# Sheet1.net
KiCad netlist of a schematic drawn in Altium Designer
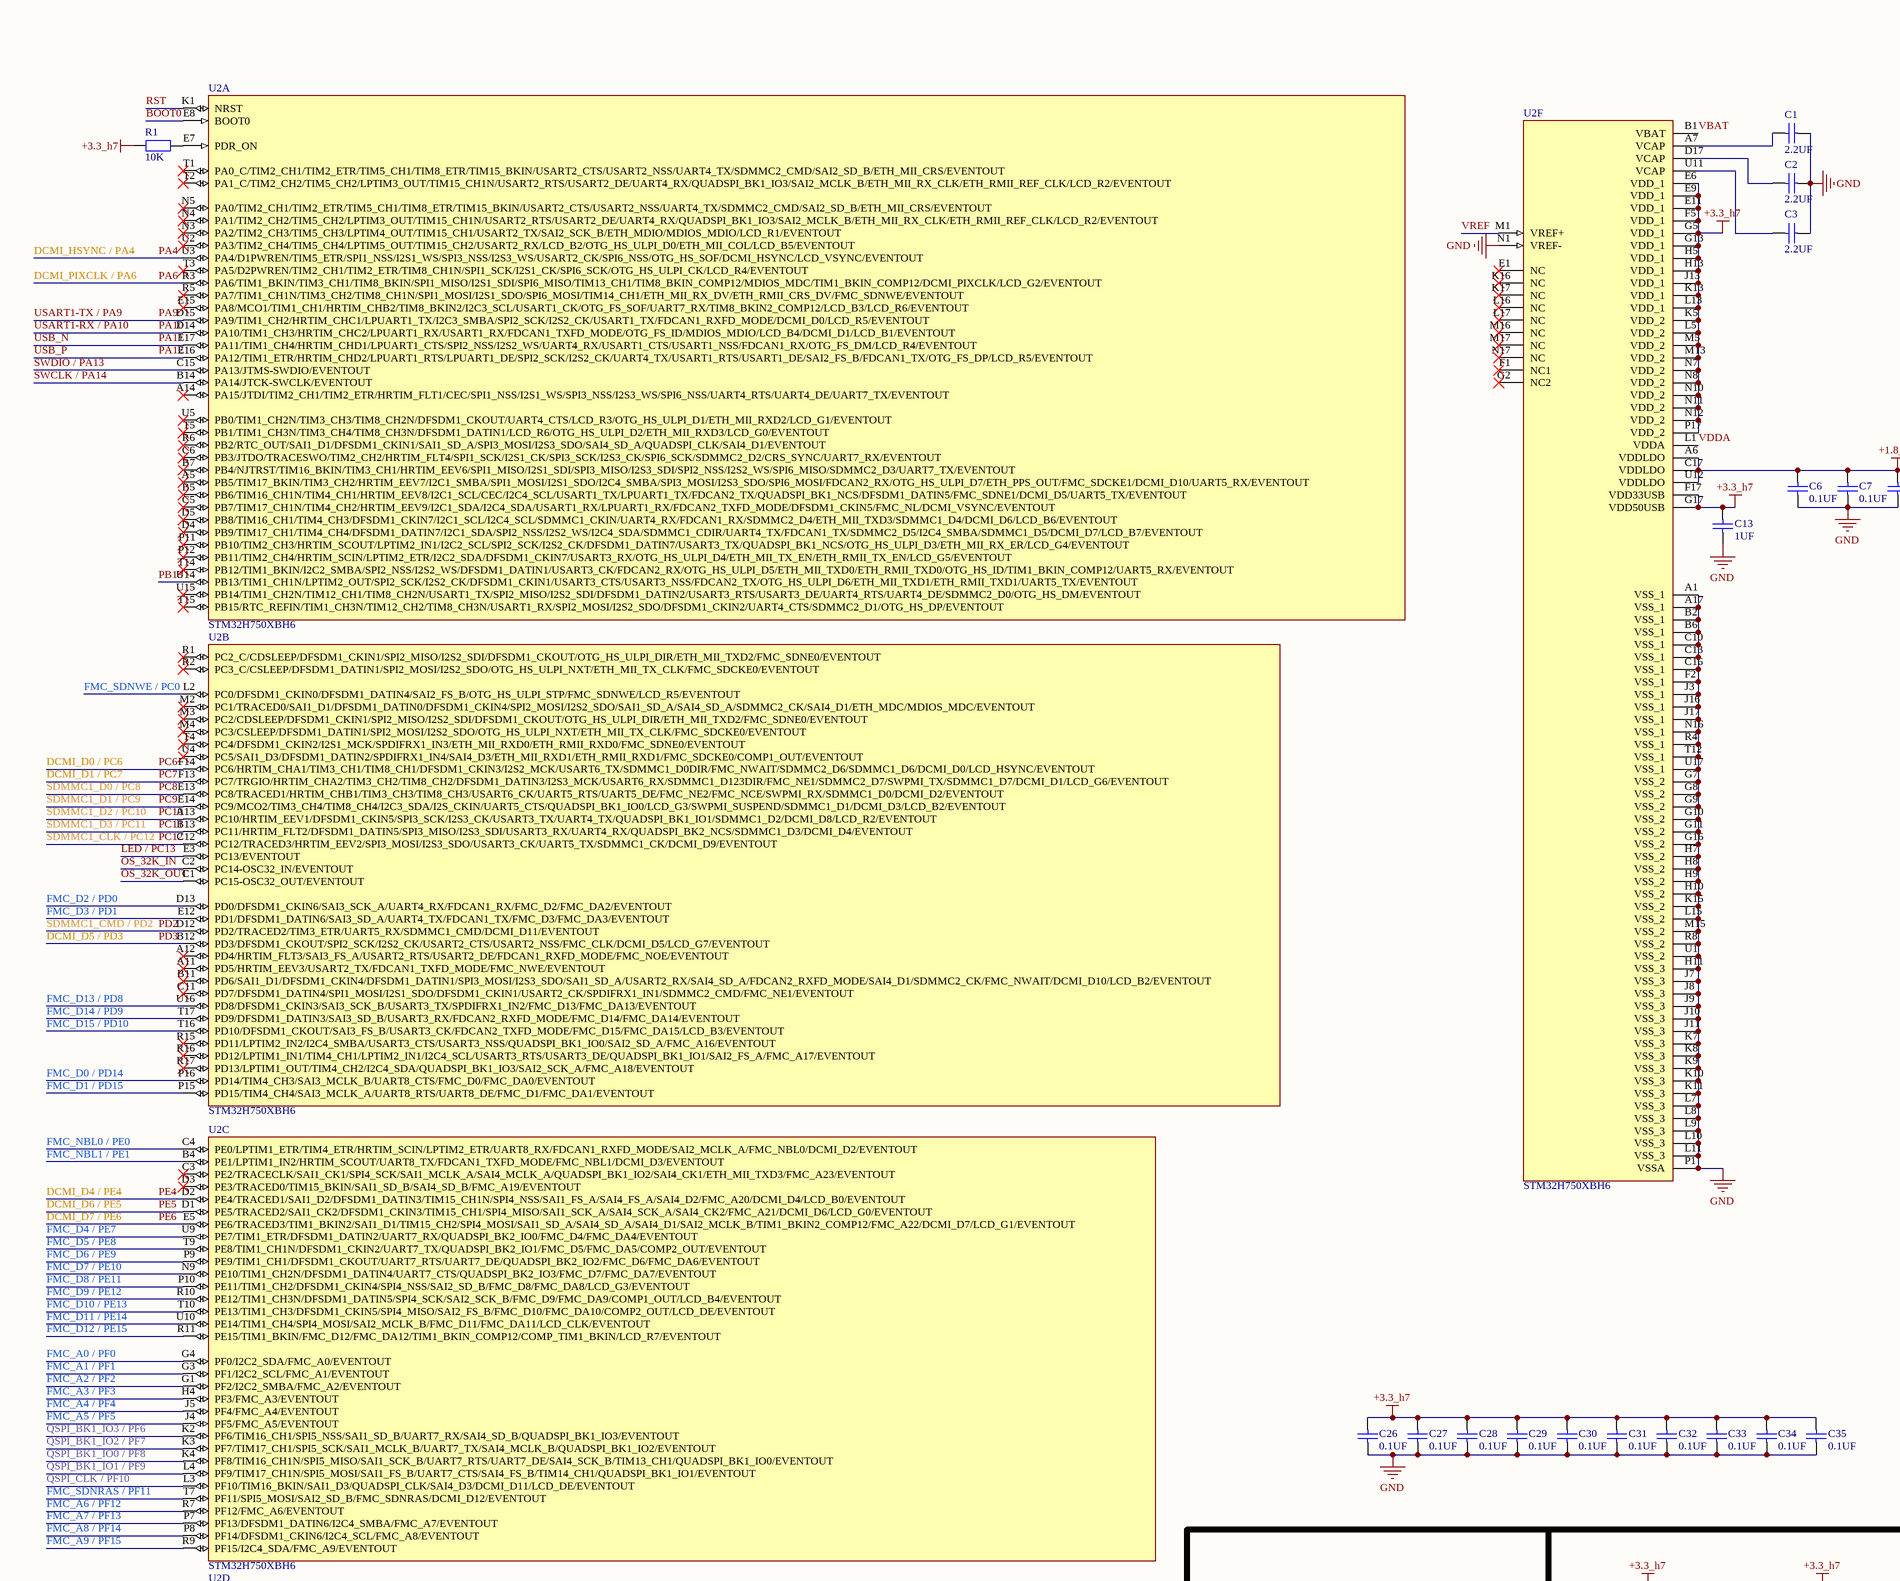
[diagram p0: Sheet1.SchDoc, top left]
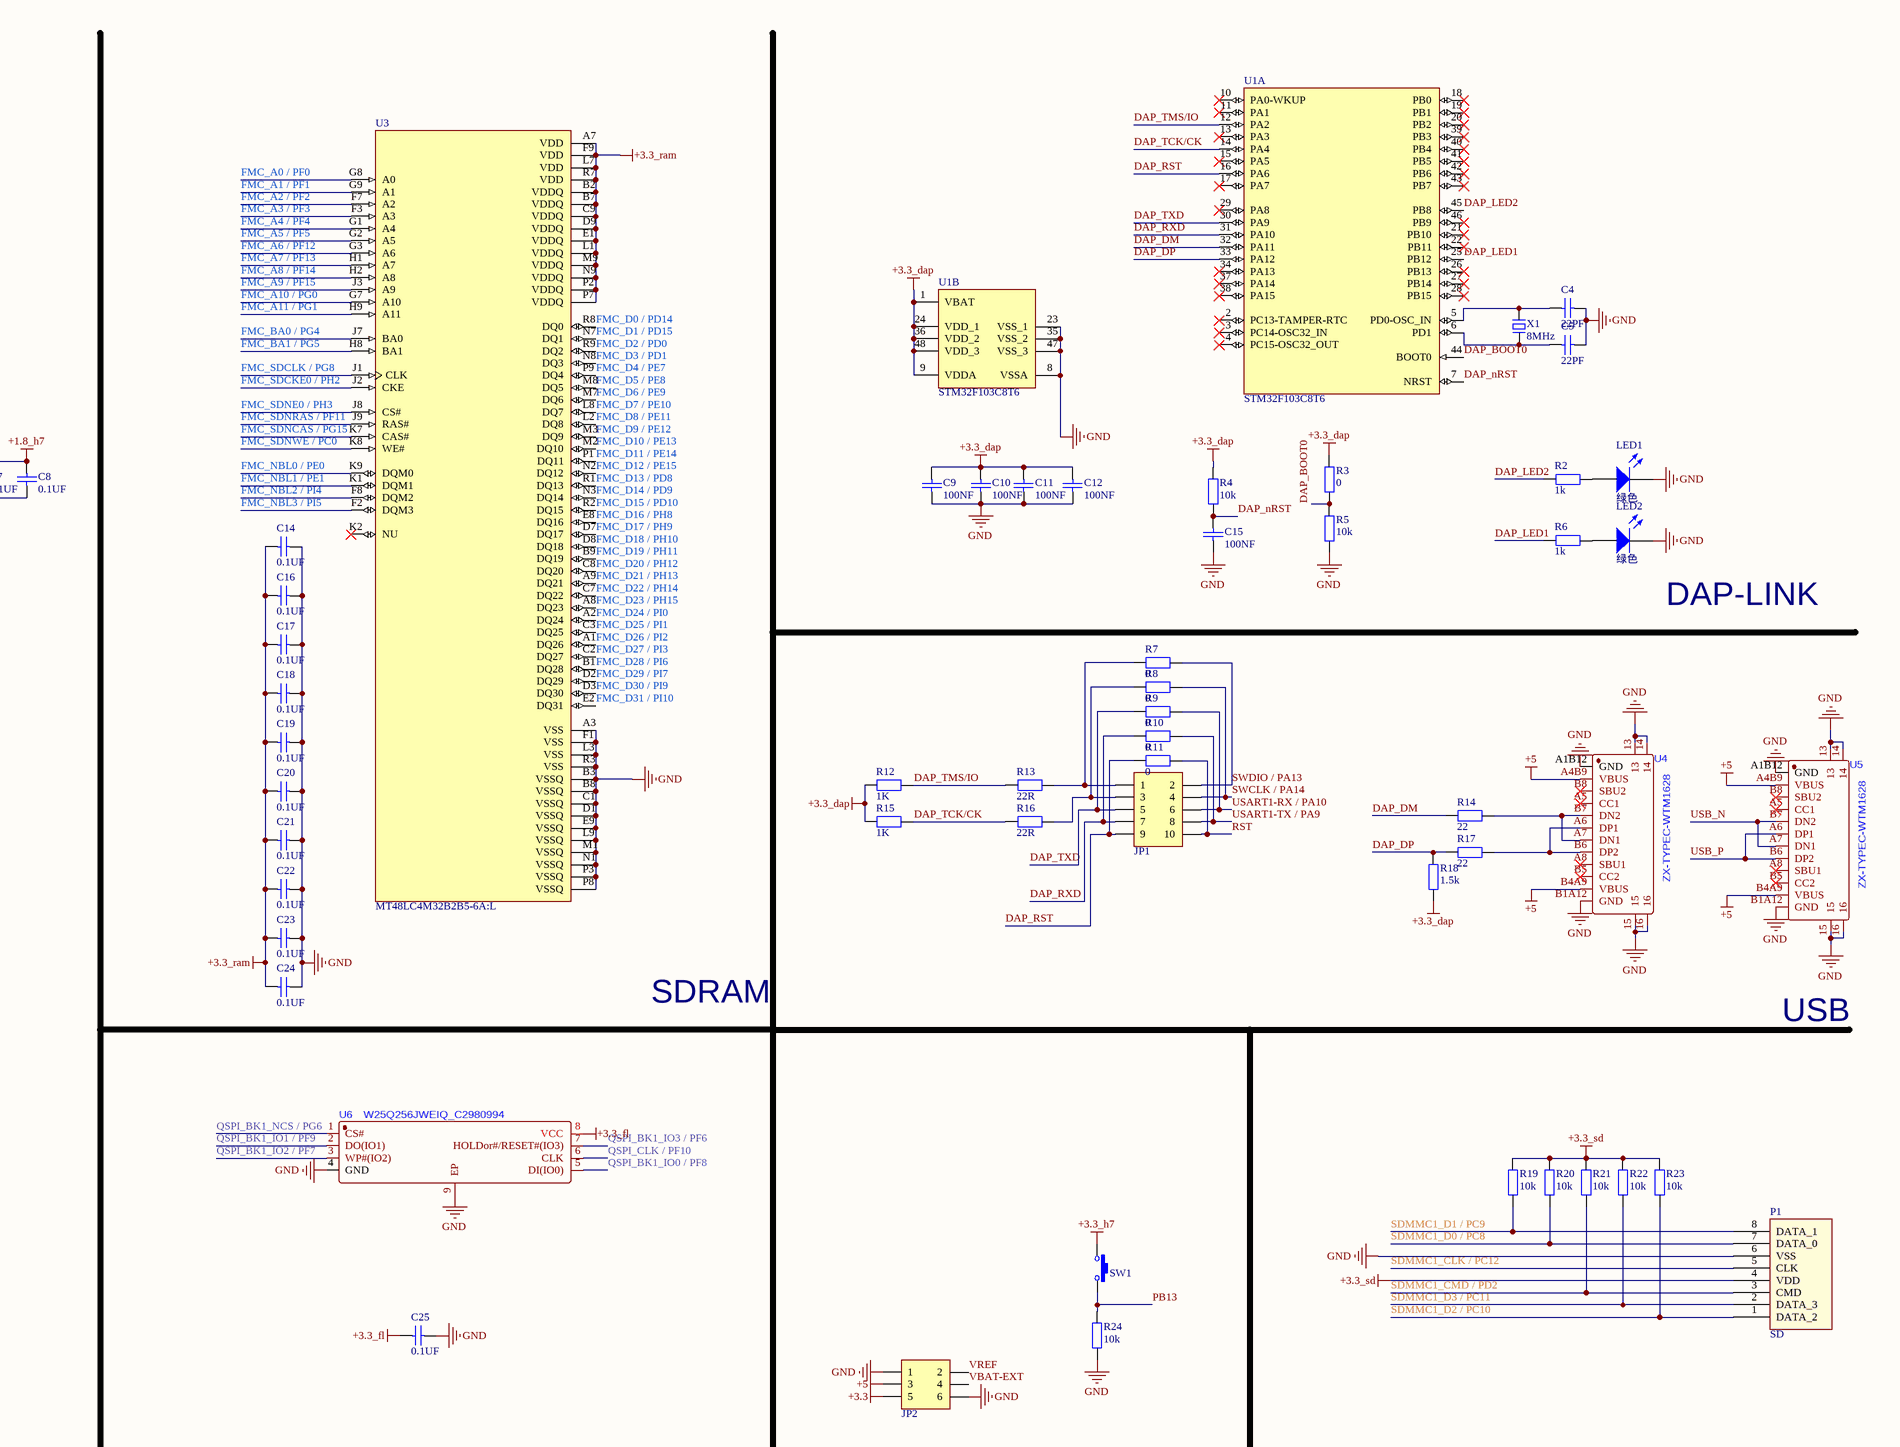
[diagram p1: Sheet1.SchDoc, top right]
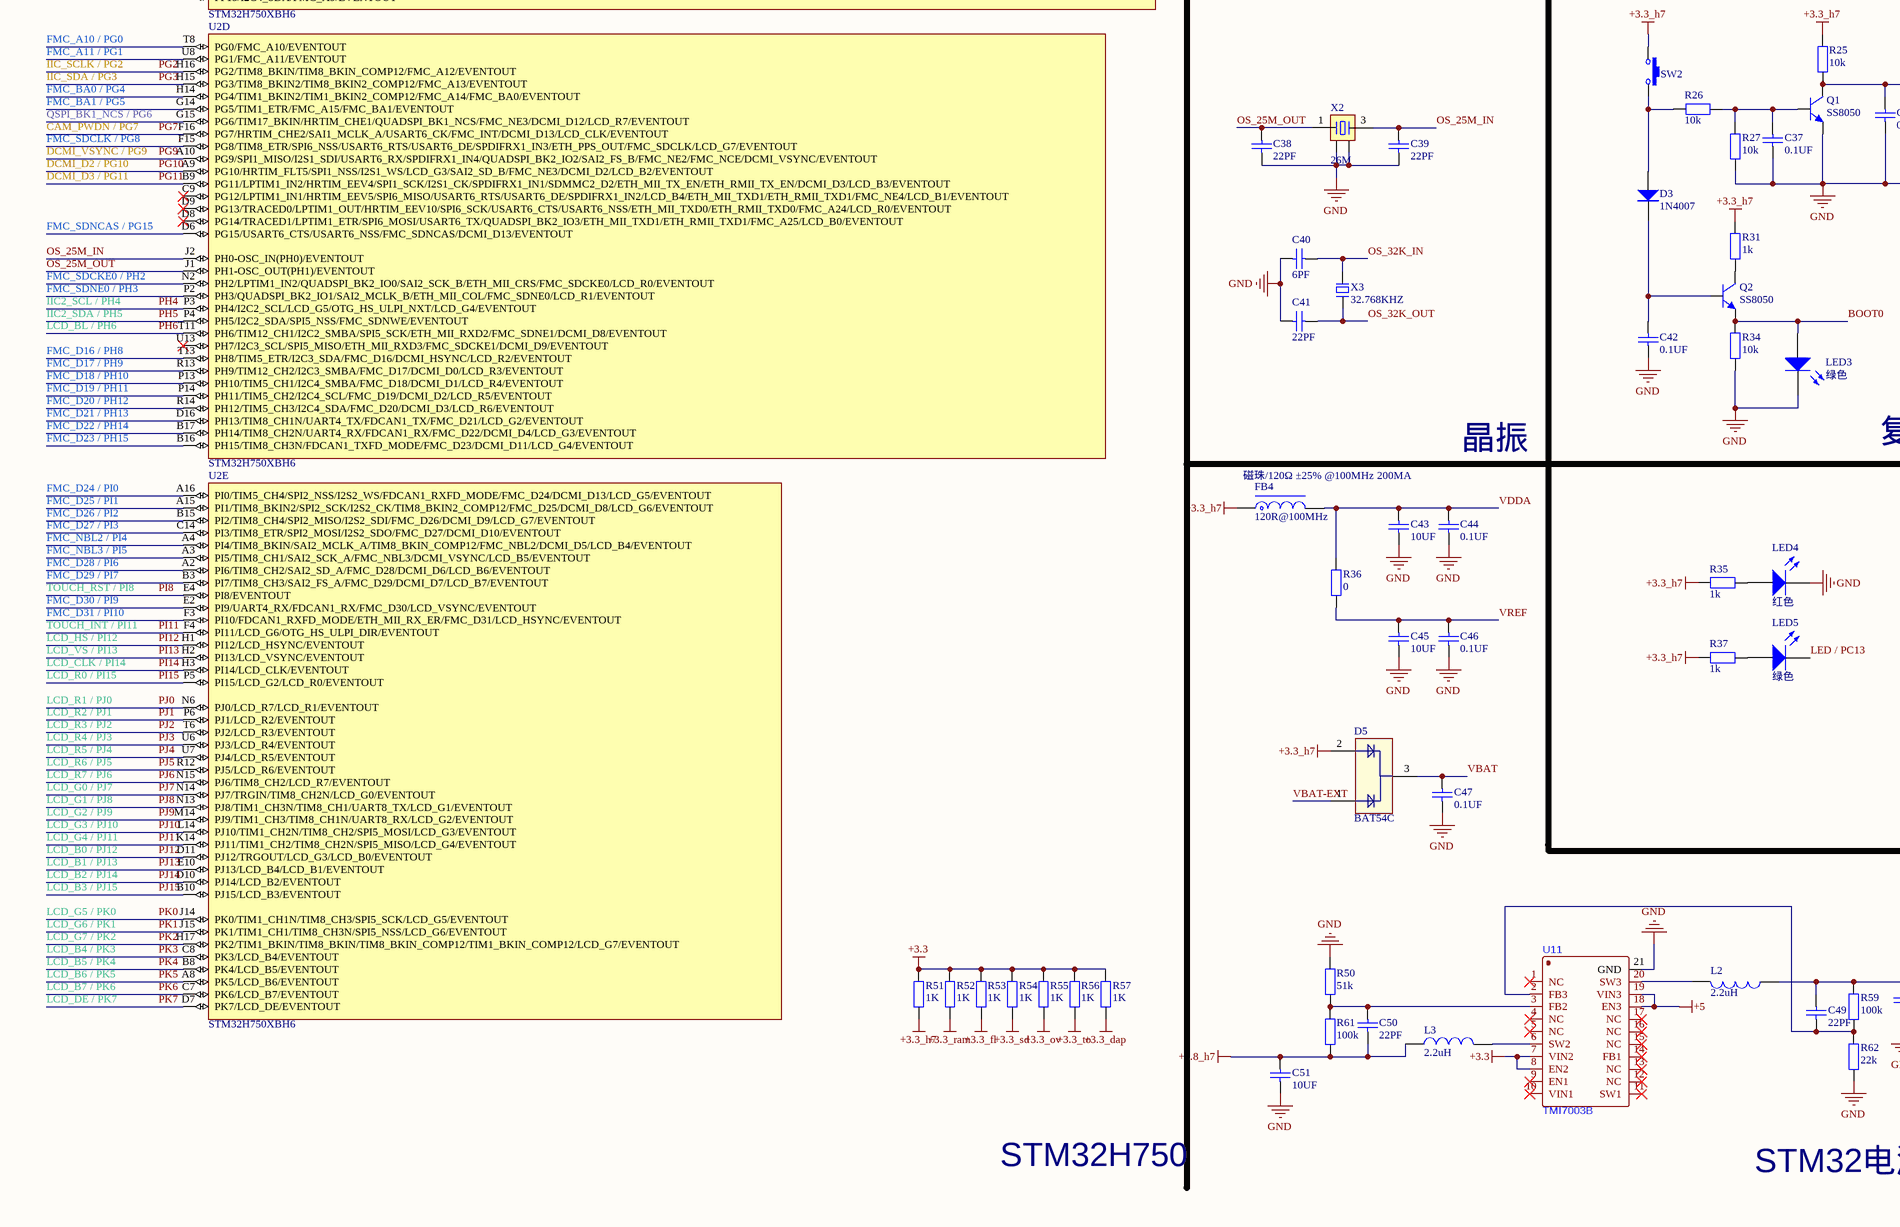
[diagram p2: Sheet1.SchDoc, bottom left]
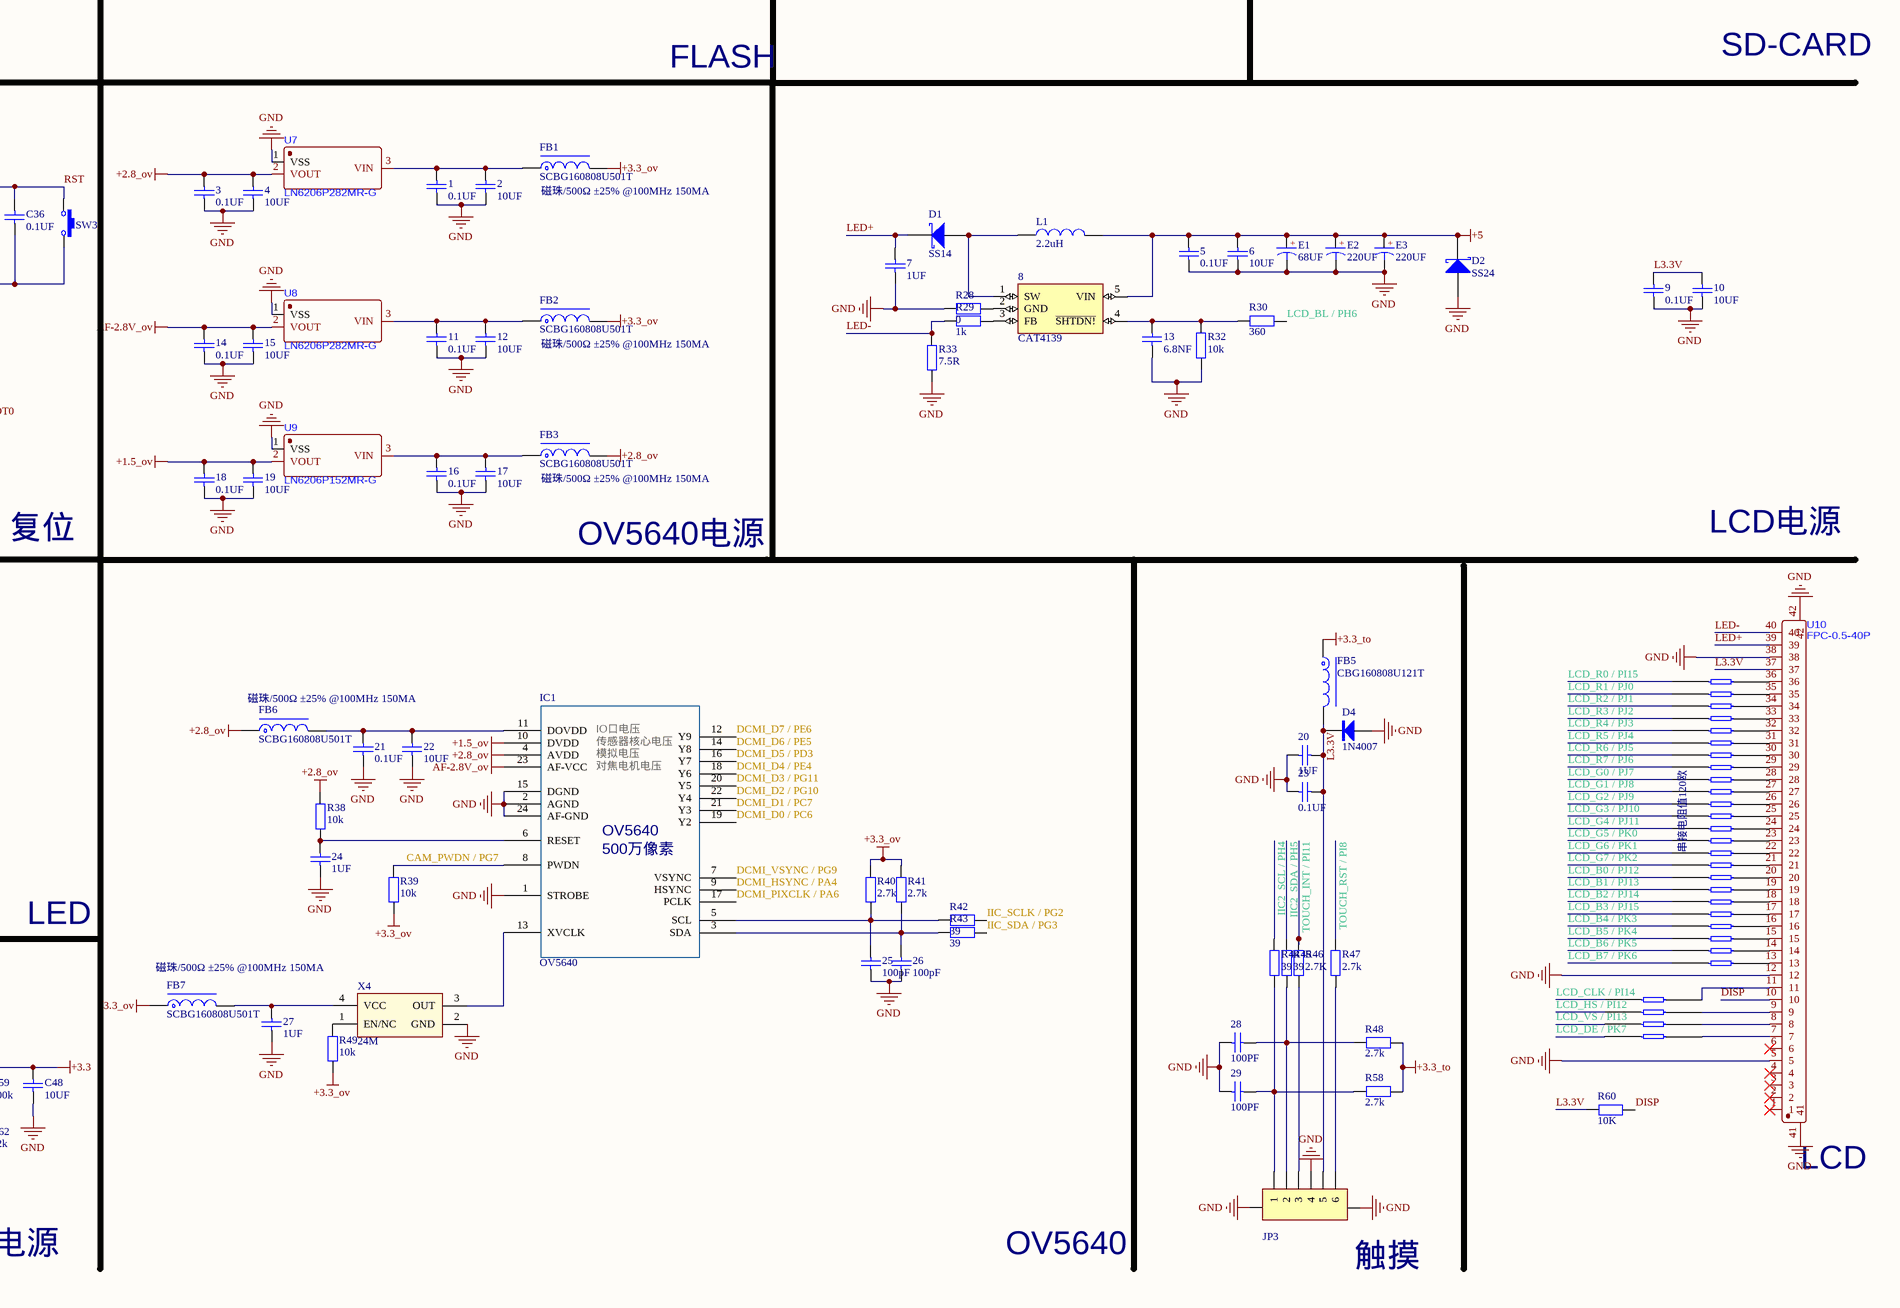
[diagram p3: Sheet1.SchDoc, bottom right]

(export (version "E")
  (design (tool "Eeschema 10.0.6"))
  (components
    (comp (ref "1")
      (value "0.1UF")
      (footprint "PCB1:C0603_L")
      (description "贴片电容/MLCC电容")
      (libsource (lib "屏幕一体板v3") (part "C"))
    )
    (comp (ref "2")
      (value "10UF")
      (footprint "PCB1:C0603_L")
      (description "贴片电容/MLCC电容")
      (libsource (lib "屏幕一体板v3") (part "C"))
    )
    (comp (ref "3")
      (value "0.1UF")
      (footprint "PCB1:C0603_L")
      (description "贴片电容/MLCC电容")
      (libsource (lib "屏幕一体板v3") (part "C"))
    )
    (comp (ref "4")
      (value "10UF")
      (footprint "PCB1:C0603_L")
      (description "贴片电容/MLCC电容")
      (libsource (lib "屏幕一体板v3") (part "C"))
    )
    (comp (ref "5")
      (value "0.1UF")
      (footprint "PCB1:C0603_L")
      (description "贴片电容/MLCC电容")
      (libsource (lib "屏幕一体板v3") (part "C"))
    )
    (comp (ref "6")
      (value "10UF")
      (footprint "PCB1:C0603_L")
      (description "贴片电容/MLCC电容")
      (libsource (lib "屏幕一体板v3") (part "C"))
    )
    (comp (ref "7")
      (value "1UF")
      (footprint "PCB1:C0603_L")
      (description "贴片电容/MLCC电容")
      (libsource (lib "屏幕一体板v3") (part "C"))
    )
    (comp (ref "8")
      (value "CAT4139")
      (footprint "PCB1:SOT-23(OT)5_LEAD")
      (libsource (lib "屏幕一体板v3") (part "CAT4139"))
    )
    (comp (ref "9")
      (value "0.1UF")
      (footprint "PCB1:C0603_L")
      (description "贴片电容/MLCC电容")
      (libsource (lib "屏幕一体板v3") (part "C"))
    )
    (comp (ref "10")
      (value "10UF")
      (footprint "PCB1:C0603_L")
      (description "贴片电容/MLCC电容")
      (libsource (lib "屏幕一体板v3") (part "C"))
    )
    (comp (ref "11")
      (value "0.1UF")
      (footprint "PCB1:C0603_L")
      (description "贴片电容/MLCC电容")
      (libsource (lib "屏幕一体板v3") (part "C"))
    )
    (comp (ref "12")
      (value "10UF")
      (footprint "PCB1:C0603_L")
      (description "贴片电容/MLCC电容")
      (libsource (lib "屏幕一体板v3") (part "C"))
    )
    (comp (ref "13")
      (value "6.8NF")
      (footprint "PCB1:C0603_L")
      (description "贴片电容/MLCC电容")
      (libsource (lib "屏幕一体板v3") (part "C"))
    )
    (comp (ref "14")
      (value "0.1UF")
      (footprint "PCB1:C0603_L")
      (description "贴片电容/MLCC电容")
      (libsource (lib "屏幕一体板v3") (part "C"))
    )
    (comp (ref "15")
      (value "10UF")
      (footprint "PCB1:C0603_L")
      (description "贴片电容/MLCC电容")
      (libsource (lib "屏幕一体板v3") (part "C"))
    )
    (comp (ref "16")
      (value "0.1UF")
      (footprint "PCB1:C0603_L")
      (description "贴片电容/MLCC电容")
      (libsource (lib "屏幕一体板v3") (part "C"))
    )
    (comp (ref "17")
      (value "10UF")
      (footprint "PCB1:C0603_L")
      (description "贴片电容/MLCC电容")
      (libsource (lib "屏幕一体板v3") (part "C"))
    )
    (comp (ref "18")
      (value "0.1UF")
      (footprint "PCB1:C0603_L")
      (description "贴片电容/MLCC电容")
      (libsource (lib "屏幕一体板v3") (part "C"))
    )
    (comp (ref "19")
      (value "10UF")
      (footprint "PCB1:C0603_L")
      (description "贴片电容/MLCC电容")
      (libsource (lib "屏幕一体板v3") (part "C"))
    )
    (comp (ref "20")
      (value "1UF")
      (footprint "PCB1:C0603_L")
      (description "贴片电容/MLCC电容")
      (libsource (lib "屏幕一体板v3") (part "C"))
    )
    (comp (ref "21")
      (value "0.1UF")
      (footprint "PCB1:C0603_L")
      (description "贴片电容/MLCC电容")
      (libsource (lib "屏幕一体板v3") (part "C"))
    )
    (comp (ref "22")
      (value "10UF")
      (footprint "PCB1:C0603_L")
      (description "贴片电容/MLCC电容")
      (libsource (lib "屏幕一体板v3") (part "C"))
    )
    (comp (ref "23")
      (value "0.1UF")
      (footprint "PCB1:C0603_L")
      (description "贴片电容/MLCC电容")
      (libsource (lib "屏幕一体板v3") (part "C"))
    )
    (comp (ref "24")
      (value "1UF")
      (footprint "PCB1:C0603_L")
      (description "贴片电容/MLCC电容")
      (libsource (lib "屏幕一体板v3") (part "C"))
    )
    (comp (ref "25")
      (value "100pF")
      (footprint "PCB1:C0603_L")
      (description "贴片电容/MLCC电容")
      (libsource (lib "屏幕一体板v3") (part "C"))
    )
    (comp (ref "26")
      (value "100pF")
      (footprint "PCB1:C0603_L")
      (description "贴片电容/MLCC电容")
      (libsource (lib "屏幕一体板v3") (part "C"))
    )
    (comp (ref "27")
      (value "1UF")
      (footprint "PCB1:C0603_L")
      (description "贴片电容/MLCC电容")
      (libsource (lib "屏幕一体板v3") (part "C"))
    )
    (comp (ref "28")
      (value "100PF")
      (footprint "PCB1:C0603_L")
      (description "贴片电容/MLCC电容")
      (libsource (lib "屏幕一体板v3") (part "C"))
    )
    (comp (ref "29")
      (value "100PF")
      (footprint "PCB1:C0603_L")
      (description "贴片电容/MLCC电容")
      (libsource (lib "屏幕一体板v3") (part "C"))
    )
    (comp (ref "C1")
      (value "2.2UF")
      (footprint "PCB1:C0603_L")
      (description "贴片电容/MLCC电容")
      (libsource (lib "屏幕一体板v3") (part "C"))
    )
    (comp (ref "C2")
      (value "2.2UF")
      (footprint "PCB1:C0603_L")
      (description "贴片电容/MLCC电容")
      (libsource (lib "屏幕一体板v3") (part "C"))
    )
    (comp (ref "C3")
      (value "2.2UF")
      (footprint "PCB1:C0603_L")
      (description "贴片电容/MLCC电容")
      (libsource (lib "屏幕一体板v3") (part "C"))
    )
    (comp (ref "C4")
      (value "22PF")
      (footprint "PCB1:C0603_L")
      (description "贴片电容/MLCC电容")
      (libsource (lib "屏幕一体板v3") (part "C"))
    )
    (comp (ref "C5")
      (value "22PF")
      (footprint "PCB1:C0603_L")
      (description "贴片电容/MLCC电容")
      (libsource (lib "屏幕一体板v3") (part "C"))
    )
    (comp (ref "C6")
      (value "0.1UF")
      (footprint "PCB1:C0603_L")
      (description "贴片电容/MLCC电容")
      (libsource (lib "屏幕一体板v3") (part "C"))
    )
    (comp (ref "C7")
      (value "0.1UF")
      (footprint "PCB1:C0603_L")
      (description "贴片电容/MLCC电容")
      (libsource (lib "屏幕一体板v3") (part "C"))
    )
    (comp (ref "C8")
      (value "0.1UF")
      (footprint "PCB1:C0603_L")
      (description "贴片电容/MLCC电容")
      (libsource (lib "屏幕一体板v3") (part "C"))
    )
    (comp (ref "C9")
      (value "100NF")
      (footprint "PCB1:C0603_L")
      (description "贴片电容/MLCC电容")
      (libsource (lib "屏幕一体板v3") (part "C"))
    )
    (comp (ref "C10")
      (value "100NF")
      (footprint "PCB1:C0603_L")
      (description "贴片电容/MLCC电容")
      (libsource (lib "屏幕一体板v3") (part "C"))
    )
    (comp (ref "C11")
      (value "100NF")
      (footprint "PCB1:C0603_L")
      (description "贴片电容/MLCC电容")
      (libsource (lib "屏幕一体板v3") (part "C"))
    )
    (comp (ref "C12")
      (value "100NF")
      (footprint "PCB1:C0603_L")
      (description "贴片电容/MLCC电容")
      (libsource (lib "屏幕一体板v3") (part "C"))
    )
    (comp (ref "C13")
      (value "1UF")
      (footprint "PCB1:C0603_L")
      (description "贴片电容/MLCC电容")
      (libsource (lib "屏幕一体板v3") (part "C"))
    )
    (comp (ref "C14")
      (value "0.1UF")
      (footprint "PCB1:C0402_M")
      (description "贴片电容/MLCC电容")
      (libsource (lib "屏幕一体板v3") (part "C"))
    )
    (comp (ref "C15")
      (value "100NF")
      (footprint "PCB1:C0603_L")
      (description "贴片电容/MLCC电容")
      (libsource (lib "屏幕一体板v3") (part "C"))
    )
    (comp (ref "C16")
      (value "0.1UF")
      (footprint "PCB1:C0402_M")
      (description "贴片电容/MLCC电容")
      (libsource (lib "屏幕一体板v3") (part "C"))
    )
    (comp (ref "C17")
      (value "0.1UF")
      (footprint "PCB1:C0402_M")
      (description "贴片电容/MLCC电容")
      (libsource (lib "屏幕一体板v3") (part "C"))
    )
    (comp (ref "C18")
      (value "0.1UF")
      (footprint "PCB1:C0402_M")
      (description "贴片电容/MLCC电容")
      (libsource (lib "屏幕一体板v3") (part "C"))
    )
    (comp (ref "C19")
      (value "0.1UF")
      (footprint "PCB1:C0402_M")
      (description "贴片电容/MLCC电容")
      (libsource (lib "屏幕一体板v3") (part "C"))
    )
    (comp (ref "C20")
      (value "0.1UF")
      (footprint "PCB1:C0402_M")
      (description "贴片电容/MLCC电容")
      (libsource (lib "屏幕一体板v3") (part "C"))
    )
    (comp (ref "C21")
      (value "0.1UF")
      (footprint "PCB1:C0402_M")
      (description "贴片电容/MLCC电容")
      (libsource (lib "屏幕一体板v3") (part "C"))
    )
    (comp (ref "C22")
      (value "0.1UF")
      (footprint "PCB1:C0402_M")
      (description "贴片电容/MLCC电容")
      (libsource (lib "屏幕一体板v3") (part "C"))
    )
    (comp (ref "C23")
      (value "0.1UF")
      (footprint "PCB1:C0402_M")
      (description "贴片电容/MLCC电容")
      (libsource (lib "屏幕一体板v3") (part "C"))
    )
    (comp (ref "C24")
      (value "0.1UF")
      (footprint "PCB1:C0402_M")
      (description "贴片电容/MLCC电容")
      (libsource (lib "屏幕一体板v3") (part "C"))
    )
    (comp (ref "C25")
      (value "0.1UF")
      (footprint "PCB1:C0603_L")
      (description "贴片电容/MLCC电容")
      (libsource (lib "屏幕一体板v3") (part "C"))
    )
    (comp (ref "C26")
      (value "0.1UF")
      (footprint "PCB1:C0402_M")
      (description "贴片电容/MLCC电容")
      (libsource (lib "屏幕一体板v3") (part "C"))
    )
    (comp (ref "C27")
      (value "0.1UF")
      (footprint "PCB1:C0402_M")
      (description "贴片电容/MLCC电容")
      (libsource (lib "屏幕一体板v3") (part "C"))
    )
    (comp (ref "C28")
      (value "0.1UF")
      (footprint "PCB1:C0603_L")
      (description "贴片电容/MLCC电容")
      (libsource (lib "屏幕一体板v3") (part "C"))
    )
    (comp (ref "C29")
      (value "0.1UF")
      (footprint "PCB1:C0402_M")
      (description "贴片电容/MLCC电容")
      (libsource (lib "屏幕一体板v3") (part "C"))
    )
    (comp (ref "C30")
      (value "0.1UF")
      (footprint "PCB1:C0402_M")
      (description "贴片电容/MLCC电容")
      (libsource (lib "屏幕一体板v3") (part "C"))
    )
    (comp (ref "C31")
      (value "0.1UF")
      (footprint "PCB1:C0402_M")
      (description "贴片电容/MLCC电容")
      (libsource (lib "屏幕一体板v3") (part "C"))
    )
    (comp (ref "C32")
      (value "0.1UF")
      (footprint "PCB1:C0402_M")
      (description "贴片电容/MLCC电容")
      (libsource (lib "屏幕一体板v3") (part "C"))
    )
    (comp (ref "C33")
      (value "0.1UF")
      (footprint "PCB1:C0402_M")
      (description "贴片电容/MLCC电容")
      (libsource (lib "屏幕一体板v3") (part "C"))
    )
    (comp (ref "C34")
      (value "0.1UF")
      (footprint "PCB1:C0402_M")
      (description "贴片电容/MLCC电容")
      (libsource (lib "屏幕一体板v3") (part "C"))
    )
    (comp (ref "C35")
      (value "0.1UF")
      (footprint "PCB1:C0402_M")
      (description "贴片电容/MLCC电容")
      (libsource (lib "屏幕一体板v3") (part "C"))
    )
    (comp (ref "C36")
      (value "0.1UF")
      (footprint "PCB1:C0603_L")
      (description "贴片电容/MLCC电容")
      (libsource (lib "屏幕一体板v3") (part "C"))
    )
    (comp (ref "C37")
      (value "0.1UF")
      (footprint "PCB1:C0603_L")
      (description "贴片电容/MLCC电容")
      (libsource (lib "屏幕一体板v3") (part "C"))
    )
    (comp (ref "C38")
      (value "22PF")
      (footprint "PCB1:C0603_L")
      (description "贴片电容/MLCC电容")
      (libsource (lib "屏幕一体板v3") (part "C"))
    )
    (comp (ref "C39")
      (value "22PF")
      (footprint "PCB1:C0603_L")
      (description "贴片电容/MLCC电容")
      (libsource (lib "屏幕一体板v3") (part "C"))
    )
    (comp (ref "C40")
      (value "6PF")
      (footprint "PCB1:C0603_L")
      (description "贴片电容/MLCC电容")
      (libsource (lib "屏幕一体板v3") (part "C"))
    )
    (comp (ref "C41")
      (value "22PF")
      (footprint "PCB1:C0603_L")
      (description "贴片电容/MLCC电容")
      (libsource (lib "屏幕一体板v3") (part "C"))
    )
    (comp (ref "C42")
      (value "0.1UF")
      (footprint "PCB1:C0603_L")
      (description "贴片电容/MLCC电容")
      (libsource (lib "屏幕一体板v3") (part "C"))
    )
    (comp (ref "C43")
      (value "10UF")
      (footprint "PCB1:C0603_L")
      (description "贴片电容/MLCC电容")
      (libsource (lib "屏幕一体板v3") (part "C"))
    )
    (comp (ref "C44")
      (value "0.1UF")
      (footprint "PCB1:C0603_L")
      (description "贴片电容/MLCC电容")
      (libsource (lib "屏幕一体板v3") (part "C"))
    )
    (comp (ref "C45")
      (value "10UF")
      (footprint "PCB1:C0603_L")
      (description "贴片电容/MLCC电容")
      (libsource (lib "屏幕一体板v3") (part "C"))
    )
    (comp (ref "C46")
      (value "0.1UF")
      (footprint "PCB1:C0603_L")
      (description "贴片电容/MLCC电容")
      (libsource (lib "屏幕一体板v3") (part "C"))
    )
    (comp (ref "C47")
      (value "0.1UF")
      (footprint "PCB1:C0603_L")
      (description "贴片电容/MLCC电容")
      (libsource (lib "屏幕一体板v3") (part "C"))
    )
    (comp (ref "C48")
      (value "10UF")
      (footprint "PCB1:C0603_L")
      (description "贴片电容/MLCC电容")
      (libsource (lib "屏幕一体板v3") (part "C"))
    )
    (comp (ref "C49")
      (value "22PF")
      (footprint "PCB1:C0603_L")
      (description "贴片电容/MLCC电容")
      (libsource (lib "屏幕一体板v3") (part "C"))
    )
    (comp (ref "C50")
      (value "22PF")
      (footprint "PCB1:C0603_L")
      (description "贴片电容/MLCC电容")
      (libsource (lib "屏幕一体板v3") (part "C"))
    )
    (comp (ref "C51")
      (value "10UF")
      (footprint "PCB1:C0603_L")
      (description "贴片电容/MLCC电容")
      (libsource (lib "屏幕一体板v3") (part "C"))
    )
    (comp (ref "D1")
      (value "SS14")
      (footprint "PCB1:SMA")
      (description "肖特基二极管")
      (libsource (lib "屏幕一体板v3") (part "SS14"))
    )
    (comp (ref "D2")
      (value "SS24")
      (footprint "PCB1:SMA")
      (description "肖特基二极管")
      (libsource (lib "屏幕一体板v3") (part "SS14"))
    )
    (comp (ref "D3")
      (value "1N4007")
      (footprint "PCB1:SMA")
      (description "整流二极管")
      (libsource (lib "屏幕一体板v3") (part "1N4007"))
    )
    (comp (ref "D4")
      (value "1N4007")
      (footprint "PCB1:SMA")
      (description "整流二极管")
      (libsource (lib "屏幕一体板v3") (part "1N4007"))
    )
    (comp (ref "D5")
      (value "BAT54C")
      (footprint "PCB1:SOT23-3N")
      (description "两路肖特基二极管")
      (libsource (lib "屏幕一体板v3") (part "BAT54C"))
    )
    (comp (ref "E1")
      (value "68UF")
      (footprint "PCB1:CE A(3*5.4)")
      (description "贴片电解电容")
      (libsource (lib "屏幕一体板v3") (part "CE_SMD"))
    )
    (comp (ref "E2")
      (value "220UF")
      (footprint "PCB1:CE A(3*5.4)")
      (description "贴片电解电容")
      (libsource (lib "屏幕一体板v3") (part "CE_SMD"))
    )
    (comp (ref "E3")
      (value "220UF")
      (footprint "PCB1:CE A(3*5.4)")
      (description "贴片电解电容")
      (libsource (lib "屏幕一体板v3") (part "CE_SMD"))
    )
    (comp (ref "FB1")
      (value "SCBG160808U501T")
      (footprint "PCB1:FB0603")
      (description "贴片磁珠")
      (libsource (lib "屏幕一体板v3") (part "FB"))
    )
    (comp (ref "FB2")
      (value "SCBG160808U501T")
      (footprint "PCB1:FB0603")
      (description "贴片磁珠")
      (libsource (lib "屏幕一体板v3") (part "FB"))
    )
    (comp (ref "FB3")
      (value "SCBG160808U501T")
      (footprint "PCB1:FB0603")
      (description "贴片磁珠")
      (libsource (lib "屏幕一体板v3") (part "FB"))
    )
    (comp (ref "FB4")
      (value "120R@100MHz")
      (footprint "PCB1:FB0603")
      (description "贴片磁珠")
      (libsource (lib "屏幕一体板v3") (part "FB"))
    )
    (comp (ref "FB5")
      (value "CBG160808U121T")
      (footprint "PCB1:FB0805")
      (description "贴片磁珠")
      (libsource (lib "") (part "FB_1"))
    )
    (comp (ref "FB6")
      (value "SCBG160808U501T")
      (footprint "PCB1:FB0603")
      (description "贴片磁珠")
      (libsource (lib "屏幕一体板v3") (part "FB"))
    )
    (comp (ref "FB7")
      (value "SCBG160808U501T")
      (footprint "PCB1:FB0603")
      (description "贴片磁珠")
      (libsource (lib "屏幕一体板v3") (part "FB"))
    )
    (comp (ref "IC1") (value "OV5640") (footprint "PCB1:OV2640") (libsource (lib "屏幕一体板v3") (part "OV5640")))
    (comp (ref "JP1")
      (value "Header 5X2")
      (footprint "PCB1:HDR2.54-M-LS-2x5P")
      (description "5*2P接插件")
      (libsource (lib "屏幕一体板v3") (part "Header 5X2"))
    )
    (comp (ref "JP2")
      (value "Header3X2")
      (footprint "PCB1:HDR2.54-M-LS-2x3P")
      (description "3*2P接插件")
      (libsource (lib "屏幕一体板v3") (part "Header 3X2"))
    )
    (comp (ref "JP3")
      (value "CON-6P")
      (footprint "PCB1:FPC0.5-WT-6P")
      (description "6P连接器")
      (libsource (lib "屏幕一体板v3") (part "Header 6"))
    )
    (comp (ref "L1")
      (value "2.2uH")
      (footprint "PCB1:L0805")
      (description "贴片小功率电感")
      (libsource (lib "屏幕一体板v3") (part "L"))
    )
    (comp (ref "L2")
      (value "2.2uH")
      (footprint "PCB1:L0805")
      (description "贴片小功率电感")
      (libsource (lib "屏幕一体板v3") (part "L"))
    )
    (comp (ref "L3")
      (value "2.2uH")
      (footprint "PCB1:L0805")
      (description "贴片小功率电感")
      (libsource (lib "屏幕一体板v3") (part "L"))
    )
    (comp (ref "LED1")
      (value "绿色")
      (footprint "PCB1:LED0805_G")
      (description "贴片LED")
      (libsource (lib "屏幕一体板v3") (part "LED"))
    )
    (comp (ref "LED2")
      (value "绿色")
      (footprint "PCB1:LED0805_G")
      (description "贴片LED")
      (libsource (lib "屏幕一体板v3") (part "LED"))
    )
    (comp (ref "LED3")
      (value "绿色")
      (footprint "PCB1:LED0805_G")
      (description "贴片LED")
      (libsource (lib "屏幕一体板v3") (part "LED"))
    )
    (comp (ref "LED4")
      (value "红色")
      (footprint "PCB1:LED0603_R")
      (description "贴片LED")
      (libsource (lib "屏幕一体板v3") (part "LED"))
    )
    (comp (ref "LED5")
      (value "绿色")
      (footprint "PCB1:LED0805_G")
      (description "贴片LED")
      (libsource (lib "屏幕一体板v3") (part "LED"))
    )
    (comp (ref "P1")
      (value "SD")
      (footprint "PCB1:MICRO SD")
      (description "自弹式TF卡座")
      (libsource (lib "屏幕一体板v3") (part "Micro SD_SD"))
    )
    (comp (ref "Q1")
      (value "SS8050")
      (footprint "PCB1:SOT23-3N")
      (description "高频放大-NPN型")
      (libsource (lib "屏幕一体板v3") (part "8050-SMD"))
    )
    (comp (ref "Q2")
      (value "SS8050")
      (footprint "PCB1:SOT23-3N")
      (description "高频放大-NPN型")
      (libsource (lib "屏幕一体板v3") (part "8050-SMD"))
    )
    (comp (ref "R1")
      (value "10K")
      (footprint "PCB1:R0603_L")
      (description "贴片电阻")
      (libsource (lib "屏幕一体板v3") (part "R"))
    )
    (comp (ref "R2")
      (value "1k")
      (footprint "PCB1:R0603_L")
      (description "贴片电阻")
      (libsource (lib "屏幕一体板v3") (part "R"))
    )
    (comp (ref "R3")
      (value "0")
      (footprint "PCB1:R0603_L")
      (description "贴片电阻")
      (libsource (lib "屏幕一体板v3") (part "R"))
    )
    (comp (ref "R4")
      (value "10k")
      (footprint "PCB1:R0603_L")
      (description "贴片电阻")
      (libsource (lib "屏幕一体板v3") (part "R"))
    )
    (comp (ref "R5")
      (value "10k")
      (footprint "PCB1:R0603_L")
      (description "贴片电阻")
      (libsource (lib "屏幕一体板v3") (part "R"))
    )
    (comp (ref "R6")
      (value "1k")
      (footprint "PCB1:R0603_L")
      (description "贴片电阻")
      (libsource (lib "屏幕一体板v3") (part "R"))
    )
    (comp (ref "R7")
      (value "0")
      (footprint "PCB1:R0603_L")
      (description "贴片电阻")
      (libsource (lib "屏幕一体板v3") (part "R"))
    )
    (comp (ref "R8")
      (value "0")
      (footprint "PCB1:R0603_L")
      (description "贴片电阻")
      (libsource (lib "屏幕一体板v3") (part "R"))
    )
    (comp (ref "R9")
      (value "0")
      (footprint "PCB1:R0603_L")
      (description "贴片电阻")
      (libsource (lib "屏幕一体板v3") (part "R"))
    )
    (comp (ref "R10")
      (value "0")
      (footprint "PCB1:R0603_L")
      (description "贴片电阻")
      (libsource (lib "屏幕一体板v3") (part "R"))
    )
    (comp (ref "R11")
      (value "0")
      (footprint "PCB1:R0603_L")
      (description "贴片电阻")
      (libsource (lib "屏幕一体板v3") (part "R"))
    )
    (comp (ref "R12")
      (value "1K")
      (footprint "PCB1:R0805_L")
      (description "贴片电阻")
      (libsource (lib "屏幕一体板v3") (part "R"))
    )
    (comp (ref "R13")
      (value "22R")
      (footprint "PCB1:R0805_L")
      (description "贴片电阻")
      (libsource (lib "屏幕一体板v3") (part "R"))
    )
    (comp (ref "R14")
      (value "22")
      (footprint "PCB1:R0603_L")
      (description "贴片电阻")
      (libsource (lib "屏幕一体板v3") (part "R"))
    )
    (comp (ref "R15")
      (value "1K")
      (footprint "PCB1:R0805_L")
      (description "贴片电阻")
      (libsource (lib "屏幕一体板v3") (part "R"))
    )
    (comp (ref "R16")
      (value "22R")
      (footprint "PCB1:R0805_L")
      (description "贴片电阻")
      (libsource (lib "屏幕一体板v3") (part "R"))
    )
    (comp (ref "R17")
      (value "22")
      (footprint "PCB1:R0603_L")
      (description "贴片电阻")
      (libsource (lib "屏幕一体板v3") (part "R"))
    )
    (comp (ref "R18")
      (value "1.5k")
      (footprint "PCB1:R0603_L")
      (description "贴片电阻")
      (libsource (lib "屏幕一体板v3") (part "R"))
    )
    (comp (ref "R19")
      (value "10k")
      (footprint "PCB1:R0603_L")
      (description "贴片电阻")
      (libsource (lib "屏幕一体板v3") (part "R"))
    )
    (comp (ref "R20")
      (value "10k")
      (footprint "PCB1:R0603_L")
      (description "贴片电阻")
      (libsource (lib "屏幕一体板v3") (part "R"))
    )
    (comp (ref "R21")
      (value "10k")
      (footprint "PCB1:R0603_L")
      (description "贴片电阻")
      (libsource (lib "屏幕一体板v3") (part "R"))
    )
    (comp (ref "R22")
      (value "10k")
      (footprint "PCB1:R0603_L")
      (description "贴片电阻")
      (libsource (lib "屏幕一体板v3") (part "R"))
    )
    (comp (ref "R23")
      (value "10k")
      (footprint "PCB1:R0603_L")
      (description "贴片电阻")
      (libsource (lib "屏幕一体板v3") (part "R"))
    )
    (comp (ref "R24")
      (value "10k")
      (footprint "PCB1:R0603_L")
      (description "贴片电阻")
      (libsource (lib "屏幕一体板v3") (part "R"))
    )
    (comp (ref "R25")
      (value "10k")
      (footprint "PCB1:R0603_L")
      (description "贴片电阻")
      (libsource (lib "屏幕一体板v3") (part "R"))
    )
    (comp (ref "R26")
      (value "10k")
      (footprint "PCB1:R0603_L")
      (description "贴片电阻")
      (libsource (lib "屏幕一体板v3") (part "R"))
    )
    (comp (ref "R27")
      (value "10k")
      (footprint "PCB1:R0603_L")
      (description "贴片电阻")
      (libsource (lib "屏幕一体板v3") (part "R"))
    )
    (comp (ref "R28")
      (value "0")
      (footprint "PCB1:R0603_L")
      (description "贴片电阻")
      (libsource (lib "屏幕一体板v3") (part "R"))
    )
    (comp (ref "R29")
      (value "1k")
      (footprint "PCB1:R0603_L")
      (description "贴片电阻")
      (libsource (lib "屏幕一体板v3") (part "R"))
    )
    (comp (ref "R30")
      (value "360")
      (footprint "PCB1:R0603_L")
      (description "贴片电阻")
      (libsource (lib "屏幕一体板v3") (part "R"))
    )
    (comp (ref "R31")
      (value "1k")
      (footprint "PCB1:R0603_L")
      (description "贴片电阻")
      (libsource (lib "屏幕一体板v3") (part "R"))
    )
    (comp (ref "R32")
      (value "10k")
      (footprint "PCB1:R0603_L")
      (description "贴片电阻")
      (libsource (lib "屏幕一体板v3") (part "R"))
    )
    (comp (ref "R33")
      (value "7.5R")
      (footprint "PCB1:R0603_L")
      (description "贴片电阻")
      (libsource (lib "屏幕一体板v3") (part "R"))
    )
    (comp (ref "R34")
      (value "10k")
      (footprint "PCB1:R0603_L")
      (description "贴片电阻")
      (libsource (lib "屏幕一体板v3") (part "R"))
    )
    (comp (ref "R35")
      (value "1k")
      (footprint "PCB1:R0603_L")
      (description "贴片电阻")
      (libsource (lib "屏幕一体板v3") (part "R"))
    )
    (comp (ref "R36")
      (value "0")
      (footprint "PCB1:R0603_L")
      (description "贴片电阻")
      (libsource (lib "屏幕一体板v3") (part "R"))
    )
    (comp (ref "R37")
      (value "1k")
      (footprint "PCB1:R0603_L")
      (description "贴片电阻")
      (libsource (lib "屏幕一体板v3") (part "R"))
    )
    (comp (ref "R38")
      (value "10k")
      (footprint "PCB1:R0603_L")
      (description "贴片电阻")
      (libsource (lib "屏幕一体板v3") (part "R"))
    )
    (comp (ref "R39")
      (value "10k")
      (footprint "PCB1:R0603_L")
      (description "贴片电阻")
      (libsource (lib "屏幕一体板v3") (part "R"))
    )
    (comp (ref "R40")
      (value "2.7k")
      (footprint "PCB1:R0603_L")
      (description "贴片电阻")
      (libsource (lib "屏幕一体板v3") (part "R"))
    )
    (comp (ref "R41")
      (value "2.7k")
      (footprint "PCB1:R0603_L")
      (description "贴片电阻")
      (libsource (lib "屏幕一体板v3") (part "R"))
    )
    (comp (ref "R42")
      (value "39")
      (footprint "PCB1:R0603_L")
      (description "贴片电阻")
      (libsource (lib "屏幕一体板v3") (part "R"))
    )
    (comp (ref "R43")
      (value "39")
      (footprint "PCB1:R0603_L")
      (description "贴片电阻")
      (libsource (lib "屏幕一体板v3") (part "R"))
    )
    (comp (ref "R44")
      (value "39")
      (footprint "PCB1:R0603_L")
      (description "贴片电阻")
      (libsource (lib "屏幕一体板v3") (part "R"))
    )
    (comp (ref "R45")
      (value "39")
      (footprint "PCB1:R0603_L")
      (description "贴片电阻")
      (libsource (lib "屏幕一体板v3") (part "R"))
    )
    (comp (ref "R46")
      (value "2.7K")
      (footprint "PCB1:R0603_L")
      (description "贴片电阻")
      (libsource (lib "屏幕一体板v3") (part "R"))
    )
    (comp (ref "R47")
      (value "2.7k")
      (footprint "PCB1:R0603_L")
      (description "贴片电阻")
      (libsource (lib "屏幕一体板v3") (part "R"))
    )
    (comp (ref "R48")
      (value "2.7k")
      (footprint "PCB1:R0603_L")
      (description "贴片电阻")
      (libsource (lib "屏幕一体板v3") (part "R"))
    )
    (comp (ref "R49")
      (value "10k")
      (footprint "PCB1:R0603_L")
      (description "贴片电阻")
      (libsource (lib "屏幕一体板v3") (part "R"))
    )
    (comp (ref "R50")
      (value "51k")
      (footprint "PCB1:R0603_L")
      (description "贴片电阻")
      (libsource (lib "屏幕一体板v3") (part "R"))
    )
    (comp (ref "R51")
      (value "1K")
      (footprint "PCB1:R0805_L")
      (description "贴片电阻")
      (libsource (lib "屏幕一体板v3") (part "R"))
    )
    (comp (ref "R52")
      (value "1K")
      (footprint "PCB1:R0805_L")
      (description "贴片电阻")
      (libsource (lib "屏幕一体板v3") (part "R"))
    )
    (comp (ref "R53")
      (value "1K")
      (footprint "PCB1:R0805_L")
      (description "贴片电阻")
      (libsource (lib "屏幕一体板v3") (part "R"))
    )
    (comp (ref "R54")
      (value "1K")
      (footprint "PCB1:R0805_L")
      (description "贴片电阻")
      (libsource (lib "屏幕一体板v3") (part "R"))
    )
    (comp (ref "R55")
      (value "1K")
      (footprint "PCB1:R0805_L")
      (description "贴片电阻")
      (libsource (lib "屏幕一体板v3") (part "R"))
    )
    (comp (ref "R56")
      (value "1K")
      (footprint "PCB1:R0805_L")
      (description "贴片电阻")
      (libsource (lib "屏幕一体板v3") (part "R"))
    )
    (comp (ref "R57")
      (value "1K")
      (footprint "PCB1:R0805_L")
      (description "贴片电阻")
      (libsource (lib "屏幕一体板v3") (part "R"))
    )
    (comp (ref "R58")
      (value "2.7k")
      (footprint "PCB1:R0603_L")
      (description "贴片电阻")
      (libsource (lib "屏幕一体板v3") (part "R"))
    )
    (comp (ref "R59")
      (value "100k")
      (footprint "PCB1:R0603_L")
      (description "贴片电阻")
      (libsource (lib "屏幕一体板v3") (part "R"))
    )
    (comp (ref "R60")
      (value "10K")
      (footprint "PCB1:R0603_L")
      (description "贴片电阻")
      (libsource (lib "屏幕一体板v3") (part "R"))
    )
    (comp (ref "R61")
      (value "100k")
      (footprint "PCB1:R0603_L")
      (description "贴片电阻")
      (libsource (lib "屏幕一体板v3") (part "R"))
    )
    (comp (ref "R62")
      (value "22k")
      (footprint "PCB1:R0603_L")
      (description "贴片电阻")
      (libsource (lib "屏幕一体板v3") (part "R"))
    )
    (comp (ref "RP1") (value "120R排阻") (footprint "PCB1:0603_4P") (libsource (lib "屏幕一体板v3") (part "RES_4P")))
    (comp (ref "RP2") (value "120R排阻") (footprint "PCB1:0603_4P") (libsource (lib "屏幕一体板v3") (part "RES_4P")))
    (comp (ref "RP3") (value "120R排阻") (footprint "PCB1:0603_4P") (libsource (lib "屏幕一体板v3") (part "RES_4P")))
    (comp (ref "RP4") (value "120R排阻") (footprint "PCB1:0603_4P") (libsource (lib "屏幕一体板v3") (part "RES_4P")))
    (comp (ref "RP5") (value "120R排阻") (footprint "PCB1:0603_4P") (libsource (lib "屏幕一体板v3") (part "RES_4P")))
    (comp (ref "RP6") (value "120R排阻") (footprint "PCB1:0603_4P") (libsource (lib "屏幕一体板v3") (part "RES_4P")))
    (comp (ref "RP7") (value "120R排阻") (footprint "PCB1:0603_4P") (libsource (lib "屏幕一体板v3") (part "RES_4P")))
    (comp (ref "SW1")
      (value "3x6x5")
      (footprint "PCB1:SW SMD-3*6*2.5")
      (description "3x6轻触开关")
      (libsource (lib "屏幕一体板v3") (part "SW 3x6"))
    )
    (comp (ref "SW2")
      (value "3x6x5")
      (footprint "PCB1:SW SMD-3*6*2.5")
      (description "3x6轻触开关")
      (libsource (lib "屏幕一体板v3") (part "SW 3x6"))
    )
    (comp (ref "SW3")
      (value "3x6x5")
      (footprint "PCB1:SW SMD-3*6*2.5")
      (description "3x6轻触开关")
      (libsource (lib "屏幕一体板v3") (part "SW 3x6"))
    )
    (comp (ref "U1")
      (value "STM32F103C8T6")
      (footprint "PCB1:LQFP48_N")
      (libsource (lib "屏幕一体板v3") (part "STM32F103C8T6"))
    )
    (comp (ref "U2")
      (value "STM32H750XBH6")
      (footprint "PCB1:IC_STM32H750XBH6")
      (libsource (lib "屏幕一体板v3") (part "STM32H750XBH6"))
    )
    (comp (ref "U3")
      (value "MT48LC4M32B2B5-6A:L")
      (footprint "PCB1:BGA90C80P9X15_800X1300X100N")
      (description "SDRAM Memory IC 128Mb _4M x 32_ Parallel 167MHz 5.4ns 90-VFBGA _8x13_")
      (libsource (lib "屏幕一体板v3") (part "MT48LC4M32B2B5-6A{colon}L"))
    )
    (comp (ref "U4")
      (value "ZX-TYPEC-WTM1628")
      (footprint "PCB1:USB-C-SMD_ZX-TYPEC-WTM1628")
      (libsource (lib "屏幕一体板v3") (part "ZX-TYPEC-WTM1628"))
    )
    (comp (ref "U5")
      (value "ZX-TYPEC-WTM1628")
      (footprint "PCB1:USB-C-SMD_ZX-TYPEC-WTM1628")
      (libsource (lib "屏幕一体板v3") (part "ZX-TYPEC-WTM1628"))
    )
    (comp (ref "U6")
      (value "W25Q256JWEIQ_C2980994")
      (footprint "PCB1:WSON-8_L8.0-W6.0-P1.27-TL-EP-1")
      (libsource (lib "屏幕一体板v3") (part "W25Q256JWEIQ_C2980994"))
    )
    (comp (ref "U7")
      (value "LN6206P282MR-G")
      (footprint "PCB1:SOT-23-3_L2.9-W1.3-P1.90-LS2.4-BR")
      (libsource (lib "屏幕一体板v3") (part "LN6206P282MR-G"))
    )
    (comp (ref "U8")
      (value "LN6206P282MR-G")
      (footprint "PCB1:SOT-23-3_L2.9-W1.3-P1.90-LS2.4-BR")
      (libsource (lib "屏幕一体板v3") (part "LN6206P282MR-G"))
    )
    (comp (ref "U9")
      (value "LN6206P152MR-G")
      (footprint "PCB1:SOT-23-3_L2.9-W1.3-P1.90-LS2.4-BR")
      (libsource (lib "屏幕一体板v3") (part "LN6206P282MR-G"))
    )
    (comp (ref "U10")
      (value "FPC-0.5-40P")
      (footprint "PCB1:CONN-SMD_FPC-0.5-40P")
      (libsource (lib "屏幕一体板v3") (part "FPC-0.5-40P"))
    )
    (comp (ref "U11")
      (value "TMI7003B")
      (footprint "PCB1:QFN-20_L3.0-W3.0-P0.40-BL-EP1.7")
      (libsource (lib "屏幕一体板v3") (part "TMI7003B"))
    )
    (comp (ref "X1")
      (value "8MHz")
      (footprint "PCB1:XTAL-3215-2P")
      (description "2脚无源晶振(谐振器）")
      (libsource (lib "屏幕一体板v3") (part "XTAL-2P"))
    )
    (comp (ref "X2")
      (value "26M")
      (footprint "PCB1:XTAL-3225-4P")
      (description "4脚无源晶振(谐振器）")
      (libsource (lib "屏幕一体板v3") (part "XTAL-4P"))
    )
    (comp (ref "X3")
      (value "32.768KHZ")
      (footprint "PCB1:XTAL-3215-2P")
      (description "2脚无源晶振(谐振器）")
      (libsource (lib "屏幕一体板v3") (part "XTAL-2P"))
    )
    (comp (ref "X4")
      (value "24M")
      (footprint "PCB1:OSC-3225-4P")
      (description "4脚有源晶振(振荡器)")
      (libsource (lib "屏幕一体板v3") (part "XTAL-ACT-4P"))
    )
  )
  (nets
    (net (code "1") (name "+1.5_ov") (class "Default")
      (node (ref "18") (pin "2") (pinfunction "2_2") (pintype "passive"))
      (node (ref "19") (pin "2") (pinfunction "2_2") (pintype "passive"))
      (node (ref "IC1") (pin "10") (pinfunction "DVDD_10") (pintype "passive"))
      (node (ref "U9") (pin "2") (pinfunction "VOUT_2") (pintype "passive"))
    )
    (net (code "2") (name "+1.8_h7") (class "Default")
      (node (ref "C50") (pin "2") (pinfunction "2_2") (pintype "passive"))
      (node (ref "C51") (pin "1") (pinfunction "1_1") (pintype "passive"))
      (node (ref "C6") (pin "1") (pinfunction "1_1") (pintype "passive"))
      (node (ref "C7") (pin "1") (pinfunction "1_1") (pintype "passive"))
      (node (ref "C8") (pin "1") (pinfunction "1_1") (pintype "passive"))
      (node (ref "L3") (pin "1") (pinfunction "1_1") (pintype "passive"))
      (node (ref "R61") (pin "1") (pinfunction "1_1") (pintype "passive"))
      (node (ref "U2") (pin "A6") (pinfunction "VDDLDO_A6") (pintype "power_in"))
      (node (ref "U2") (pin "C17") (pinfunction "VDDLDO_C17") (pintype "power_in"))
      (node (ref "U2") (pin "U12") (pinfunction "VDDLDO_U12") (pintype "power_in"))
    )
    (net (code "3") (name "+2.8_ov") (class "Default")
      (node (ref "3") (pin "2") (pinfunction "2_2") (pintype "passive"))
      (node (ref "4") (pin "2") (pinfunction "2_2") (pintype "passive"))
      (node (ref "FB3") (pin "2") (pinfunction "2_2") (pintype "passive"))
      (node (ref "FB6") (pin "1") (pinfunction "1_1") (pintype "passive"))
      (node (ref "IC1") (pin "4") (pinfunction "AVDD_4") (pintype "passive"))
      (node (ref "R38") (pin "1") (pinfunction "1_1") (pintype "passive"))
      (node (ref "U7") (pin "2") (pinfunction "VOUT_2") (pintype "passive"))
    )
    (net (code "4") (name "+3.3") (class "Default")
      (node (ref "C48") (pin "2") (pinfunction "2_2") (pintype "passive"))
      (node (ref "C49") (pin "2") (pinfunction "2_2") (pintype "passive"))
      (node (ref "JP2") (pin "5") (pinfunction "5_5") (pintype "passive"))
      (node (ref "L2") (pin "1") (pinfunction "1_1") (pintype "passive"))
      (node (ref "R51") (pin "2") (pinfunction "2_2") (pintype "passive"))
      (node (ref "R52") (pin "2") (pinfunction "2_2") (pintype "passive"))
      (node (ref "R53") (pin "2") (pinfunction "2_2") (pintype "passive"))
      (node (ref "R54") (pin "2") (pinfunction "2_2") (pintype "passive"))
      (node (ref "R55") (pin "2") (pinfunction "2_2") (pintype "passive"))
      (node (ref "R56") (pin "2") (pinfunction "2_2") (pintype "passive"))
      (node (ref "R57") (pin "2") (pinfunction "2_2") (pintype "passive"))
      (node (ref "R59") (pin "1") (pinfunction "1_1") (pintype "passive"))
      (node (ref "U11") (pin "7") (pinfunction "VIN2_7") (pintype "passive"))
      (node (ref "U11") (pin "8") (pinfunction "EN2_8") (pintype "passive"))
    )
    (net (code "5") (name "+3.3_dap") (class "Default")
      (node (ref "C10") (pin "2") (pinfunction "2_2") (pintype "passive"))
      (node (ref "C11") (pin "2") (pinfunction "2_2") (pintype "passive"))
      (node (ref "C12") (pin "2") (pinfunction "2_2") (pintype "passive"))
      (node (ref "C9") (pin "2") (pinfunction "2_2") (pintype "passive"))
      (node (ref "R12") (pin "1") (pinfunction "1_1") (pintype "passive"))
      (node (ref "R15") (pin "1") (pinfunction "1_1") (pintype "passive"))
      (node (ref "R18") (pin "1") (pinfunction "1_1") (pintype "passive"))
      (node (ref "R3") (pin "2") (pinfunction "2_2") (pintype "passive"))
      (node (ref "R4") (pin "2") (pinfunction "2_2") (pintype "passive"))
      (node (ref "R57") (pin "1") (pinfunction "1_1") (pintype "passive"))
      (node (ref "U1") (pin "1") (pinfunction "VBAT_1") (pintype "power_in"))
      (node (ref "U1") (pin "24") (pinfunction "VDD_1_24") (pintype "power_in"))
      (node (ref "U1") (pin "36") (pinfunction "VDD_2_36") (pintype "power_in"))
      (node (ref "U1") (pin "48") (pinfunction "VDD_3_48") (pintype "power_in"))
      (node (ref "U1") (pin "9") (pinfunction "VDDA_9") (pintype "power_in"))
    )
    (net (code "6") (name "+3.3_fl") (class "Default")
      (node (ref "C25") (pin "2") (pinfunction "2_2") (pintype "passive"))
      (node (ref "R53") (pin "1") (pinfunction "1_1") (pintype "passive"))
      (node (ref "U6") (pin "8") (pinfunction "VCC_8") (pintype "passive"))
    )
    (net (code "7") (name "+3.3_h7") (class "Default")
      (node (ref "C13") (pin "2") (pinfunction "2_2") (pintype "passive"))
      (node (ref "C26") (pin "2") (pinfunction "2_2") (pintype "passive"))
      (node (ref "C27") (pin "2") (pinfunction "2_2") (pintype "passive"))
      (node (ref "C28") (pin "2") (pinfunction "2_2") (pintype "passive"))
      (node (ref "C29") (pin "2") (pinfunction "2_2") (pintype "passive"))
      (node (ref "C30") (pin "2") (pinfunction "2_2") (pintype "passive"))
      (node (ref "C31") (pin "2") (pinfunction "2_2") (pintype "passive"))
      (node (ref "C32") (pin "2") (pinfunction "2_2") (pintype "passive"))
      (node (ref "C33") (pin "2") (pinfunction "2_2") (pintype "passive"))
      (node (ref "C34") (pin "2") (pinfunction "2_2") (pintype "passive"))
      (node (ref "C35") (pin "2") (pinfunction "2_2") (pintype "passive"))
      (node (ref "D5") (pin "2") (pinfunction "2_2") (pintype "passive"))
      (node (ref "FB4") (pin "1") (pinfunction "1_1") (pintype "passive"))
      (node (ref "R1") (pin "1") (pinfunction "1_1") (pintype "passive"))
      (node (ref "R25") (pin "2") (pinfunction "2_2") (pintype "passive"))
      (node (ref "R31") (pin "2") (pinfunction "2_2") (pintype "passive"))
      (node (ref "R35") (pin "1") (pinfunction "1_1") (pintype "passive"))
      (node (ref "R37") (pin "1") (pinfunction "1_1") (pintype "passive"))
      (node (ref "R51") (pin "1") (pinfunction "1_1") (pintype "passive"))
      (node (ref "SW1") (pin "1") (pinfunction "1_1") (pintype "passive"))
      (node (ref "SW2") (pin "1") (pinfunction "1_1") (pintype "passive"))
      (node (ref "U2") (pin "E11") (pinfunction "VDD_1_E11") (pintype "power_in"))
      (node (ref "U2") (pin "E6") (pinfunction "VDD_1_E6") (pintype "power_in"))
      (node (ref "U2") (pin "E9") (pinfunction "VDD_1_E9") (pintype "power_in"))
      (node (ref "U2") (pin "F17") (pinfunction "VDD33USB_F17") (pintype "power_in"))
      (node (ref "U2") (pin "F5") (pinfunction "VDD_1_F5") (pintype "power_in"))
      (node (ref "U2") (pin "G13") (pinfunction "VDD_1_G13") (pintype "power_in"))
      (node (ref "U2") (pin "G17") (pinfunction "VDD50USB_G17") (pintype "power_in"))
      (node (ref "U2") (pin "G5") (pinfunction "VDD_1_G5") (pintype "power_in"))
      (node (ref "U2") (pin "H13") (pinfunction "VDD_1_H13") (pintype "power_in"))
      (node (ref "U2") (pin "H5") (pinfunction "VDD_1_H5") (pintype "power_in"))
      (node (ref "U2") (pin "J13") (pinfunction "VDD_1_J13") (pintype "power_in"))
      (node (ref "U2") (pin "K13") (pinfunction "VDD_1_K13") (pintype "power_in"))
      (node (ref "U2") (pin "K5") (pinfunction "VDD_2_K5") (pintype "power_in"))
      (node (ref "U2") (pin "L13") (pinfunction "VDD_1_L13") (pintype "power_in"))
      (node (ref "U2") (pin "L5") (pinfunction "VDD_2_L5") (pintype "power_in"))
      (node (ref "U2") (pin "M13") (pinfunction "VDD_2_M13") (pintype "power_in"))
      (node (ref "U2") (pin "M5") (pinfunction "VDD_2_M5") (pintype "power_in"))
      (node (ref "U2") (pin "N10") (pinfunction "VDD_2_N10") (pintype "power_in"))
      (node (ref "U2") (pin "N11") (pinfunction "VDD_2_N11") (pintype "power_in"))
      (node (ref "U2") (pin "N12") (pinfunction "VDD_2_N12") (pintype "power_in"))
      (node (ref "U2") (pin "N7") (pinfunction "VDD_2_N7") (pintype "power_in"))
      (node (ref "U2") (pin "N8") (pinfunction "VDD_2_N8") (pintype "power_in"))
      (node (ref "U2") (pin "P17") (pinfunction "VDD_2_P17") (pintype "power_in"))
    )
    (net (code "8") (name "+3.3_ov") (class "Default")
      (node (ref "FB1") (pin "2") (pinfunction "2_2") (pintype "passive"))
      (node (ref "FB2") (pin "2") (pinfunction "2_2") (pintype "passive"))
      (node (ref "FB7") (pin "1") (pinfunction "1_1") (pintype "passive"))
      (node (ref "R39") (pin "2") (pinfunction "2_2") (pintype "passive"))
      (node (ref "R40") (pin "2") (pinfunction "2_2") (pintype "passive"))
      (node (ref "R41") (pin "2") (pinfunction "2_2") (pintype "passive"))
      (node (ref "R49") (pin "2") (pinfunction "2_2") (pintype "passive"))
      (node (ref "R55") (pin "1") (pinfunction "1_1") (pintype "passive"))
    )
    (net (code "9") (name "+3.3_ram") (class "Default")
      (node (ref "C14") (pin "2") (pinfunction "2_2") (pintype "passive"))
      (node (ref "C16") (pin "2") (pinfunction "2_2") (pintype "passive"))
      (node (ref "C17") (pin "2") (pinfunction "2_2") (pintype "passive"))
      (node (ref "C18") (pin "2") (pinfunction "2_2") (pintype "passive"))
      (node (ref "C19") (pin "2") (pinfunction "2_2") (pintype "passive"))
      (node (ref "C20") (pin "2") (pinfunction "2_2") (pintype "passive"))
      (node (ref "C21") (pin "2") (pinfunction "2_2") (pintype "passive"))
      (node (ref "C22") (pin "2") (pinfunction "2_2") (pintype "passive"))
      (node (ref "C23") (pin "2") (pinfunction "2_2") (pintype "passive"))
      (node (ref "C24") (pin "2") (pinfunction "2_2") (pintype "passive"))
      (node (ref "R52") (pin "1") (pinfunction "1_1") (pintype "passive"))
      (node (ref "U3") (pin "A7") (pinfunction "VDD_A7") (pintype "power_in"))
      (node (ref "U3") (pin "B2") (pinfunction "VDDQ_B2") (pintype "power_in"))
      (node (ref "U3") (pin "B7") (pinfunction "VDDQ_B7") (pintype "power_in"))
      (node (ref "U3") (pin "C9") (pinfunction "VDDQ_C9") (pintype "power_in"))
      (node (ref "U3") (pin "D9") (pinfunction "VDDQ_D9") (pintype "power_in"))
      (node (ref "U3") (pin "E1") (pinfunction "VDDQ_E1") (pintype "power_in"))
      (node (ref "U3") (pin "F9") (pinfunction "VDD_F9") (pintype "power_in"))
      (node (ref "U3") (pin "L1") (pinfunction "VDDQ_L1") (pintype "power_in"))
      (node (ref "U3") (pin "L7") (pinfunction "VDD_L7") (pintype "power_in"))
      (node (ref "U3") (pin "M9") (pinfunction "VDDQ_M9") (pintype "power_in"))
      (node (ref "U3") (pin "N9") (pinfunction "VDDQ_N9") (pintype "power_in"))
      (node (ref "U3") (pin "P2") (pinfunction "VDDQ_P2") (pintype "power_in"))
      (node (ref "U3") (pin "P7") (pinfunction "VDDQ_P7") (pintype "power_in"))
      (node (ref "U3") (pin "R7") (pinfunction "VDD_R7") (pintype "power_in"))
    )
    (net (code "10") (name "+3.3_sd") (class "Default")
      (node (ref "P1") (pin "4") (pinfunction "VDD_4") (pintype "passive"))
      (node (ref "R19") (pin "1") (pinfunction "1_1") (pintype "passive"))
      (node (ref "R20") (pin "1") (pinfunction "1_1") (pintype "passive"))
      (node (ref "R21") (pin "1") (pinfunction "1_1") (pintype "passive"))
      (node (ref "R22") (pin "1") (pinfunction "1_1") (pintype "passive"))
      (node (ref "R23") (pin "1") (pinfunction "1_1") (pintype "passive"))
      (node (ref "R54") (pin "1") (pinfunction "1_1") (pintype "passive"))
    )
    (net (code "11") (name "+3.3_to") (class "Default")
      (node (ref "FB5") (pin "1") (pinfunction "1_1") (pintype "passive"))
      (node (ref "R48") (pin "2") (pinfunction "2_2") (pintype "passive"))
      (node (ref "R56") (pin "1") (pinfunction "1_1") (pintype "passive"))
      (node (ref "R58") (pin "2") (pinfunction "2_2") (pintype "passive"))
    )
    (net (code "12") (name "+5") (class "Default")
      (node (ref "5") (pin "2") (pinfunction "2_2") (pintype "passive"))
      (node (ref "6") (pin "2") (pinfunction "2_2") (pintype "passive"))
      (node (ref "8") (pin "5") (pinfunction "VIN_5") (pintype "bidirectional"))
      (node (ref "D2") (pin "2") (pinfunction "K_2") (pintype "passive"))
      (node (ref "E1") (pin "1") (pinfunction "1_1") (pintype "passive"))
      (node (ref "E2") (pin "1") (pinfunction "1_1") (pintype "passive"))
      (node (ref "E3") (pin "1") (pinfunction "1_1") (pintype "passive"))
      (node (ref "JP2") (pin "3") (pinfunction "3_3") (pintype "passive"))
      (node (ref "L1") (pin "2") (pinfunction "2_2") (pintype "passive"))
      (node (ref "U11") (pin "18") (pinfunction "EN3_18") (pintype "passive"))
      (node (ref "U11") (pin "19") (pinfunction "VIN3_19") (pintype "passive"))
      (node (ref "U4") (pin "A4B9") (pinfunction "VBUS_A4B9") (pintype "passive"))
      (node (ref "U4") (pin "B4A9") (pinfunction "VBUS_B4A9") (pintype "passive"))
      (node (ref "U5") (pin "A4B9") (pinfunction "VBUS_A4B9") (pintype "passive"))
      (node (ref "U5") (pin "B4A9") (pinfunction "VBUS_B4A9") (pintype "passive"))
    )
    (net (code "13") (name "/BOOT0") (class "Default")
      (node (ref "LED3") (pin "1") (pinfunction "A_1") (pintype "passive"))
      (node (ref "Q2") (pin "2") (pinfunction "E_2") (pintype "passive"))
      (node (ref "R34") (pin "2") (pinfunction "2_2") (pintype "passive"))
      (node (ref "U2") (pin "E8") (pinfunction "BOOT0_E8") (pintype "input"))
    )
    (net (code "14") (name "/CAM_PWDN {slash} PG7") (class "Default")
      (node (ref "IC1") (pin "8") (pinfunction "PWDN_8") (pintype "passive"))
      (node (ref "R39") (pin "1") (pinfunction "1_1") (pintype "passive"))
      (node (ref "U2") (pin "F16") (pinfunction "PG7/HRTIM_CHE2/SAI1_MCLK_A/USART6_CK/FMC_INT/DCMI_D13/LCD_CLK/EVENTOUT_F16") (pintype "bidirectional"))
    )
    (net (code "15") (name "/DAP_BOOT0") (class "Default")
      (node (ref "R3") (pin "1") (pinfunction "1_1") (pintype "passive"))
      (node (ref "R5") (pin "2") (pinfunction "2_2") (pintype "passive"))
      (node (ref "U1") (pin "44") (pinfunction "BOOT0_44") (pintype "input"))
    )
    (net (code "16") (name "/DAP_DM") (class "Default")
      (node (ref "R14") (pin "1") (pinfunction "1_1") (pintype "passive"))
      (node (ref "U1") (pin "32") (pinfunction "PA11_32") (pintype "bidirectional"))
    )
    (net (code "17") (name "/DAP_DP") (class "Default")
      (node (ref "R17") (pin "1") (pinfunction "1_1") (pintype "passive"))
      (node (ref "R18") (pin "2") (pinfunction "2_2") (pintype "passive"))
      (node (ref "U1") (pin "33") (pinfunction "PA12_33") (pintype "bidirectional"))
    )
    (net (code "18") (name "/DAP_LED1") (class "Default")
      (node (ref "R6") (pin "1") (pinfunction "1_1") (pintype "passive"))
      (node (ref "U1") (pin "25") (pinfunction "PB12_25") (pintype "bidirectional"))
    )
    (net (code "19") (name "/DAP_LED2") (class "Default")
      (node (ref "R2") (pin "1") (pinfunction "1_1") (pintype "passive"))
      (node (ref "U1") (pin "45") (pinfunction "PB8_45") (pintype "bidirectional"))
    )
    (net (code "20") (name "/DAP_RST") (class "Default")
      (node (ref "JP1") (pin "9") (pinfunction "9_9") (pintype "passive"))
      (node (ref "R11") (pin "1") (pinfunction "1_1") (pintype "passive"))
      (node (ref "U1") (pin "16") (pinfunction "PA6_16") (pintype "bidirectional"))
    )
    (net (code "21") (name "/DAP_RXD") (class "Default")
      (node (ref "JP1") (pin "7") (pinfunction "7_7") (pintype "passive"))
      (node (ref "R10") (pin "1") (pinfunction "1_1") (pintype "passive"))
      (node (ref "U1") (pin "31") (pinfunction "PA10_31") (pintype "bidirectional"))
    )
    (net (code "22") (name "/DAP_TCK{slash}CK") (class "Default")
      (node (ref "R15") (pin "2") (pinfunction "2_2") (pintype "passive"))
      (node (ref "R16") (pin "1") (pinfunction "1_1") (pintype "passive"))
      (node (ref "U1") (pin "14") (pinfunction "PA4_14") (pintype "bidirectional"))
    )
    (net (code "23") (name "/DAP_TMS{slash}IO") (class "Default")
      (node (ref "R12") (pin "2") (pinfunction "2_2") (pintype "passive"))
      (node (ref "R13") (pin "1") (pinfunction "1_1") (pintype "passive"))
      (node (ref "U1") (pin "12") (pinfunction "PA2_12") (pintype "bidirectional"))
    )
    (net (code "24") (name "/DAP_TXD") (class "Default")
      (node (ref "JP1") (pin "5") (pinfunction "5_5") (pintype "passive"))
      (node (ref "R9") (pin "1") (pinfunction "1_1") (pintype "passive"))
      (node (ref "U1") (pin "30") (pinfunction "PA9_30") (pintype "bidirectional"))
    )
    (net (code "25") (name "/DAP_nRST") (class "Default")
      (node (ref "C15") (pin "2") (pinfunction "2_2") (pintype "passive"))
      (node (ref "R4") (pin "1") (pinfunction "1_1") (pintype "passive"))
      (node (ref "U1") (pin "7") (pinfunction "NRST_7") (pintype "bidirectional"))
    )
    (net (code "26") (name "/DCMI_D0 {slash} PC6") (class "Default")
      (node (ref "IC1") (pin "19") (pinfunction "Y2_19") (pintype "passive"))
      (node (ref "U2") (pin "F14") (pinfunction "PC6/HRTIM_CHA1/TIM3_CH1/TIM8_CH1/DFSDM1_CKIN3/I2S2_MCK/USART6_TX/SDMMC1_D0DIR/FMC_NWAIT/SDMMC2_D6/SDMMC1_D6/DCMI_D0/LCD_HSYNC/EVENTOUT_F14") (pintype "bidirectional"))
    )
    (net (code "27") (name "/DCMI_D1 {slash} PC7") (class "Default")
      (node (ref "IC1") (pin "21") (pinfunction "Y3_21") (pintype "passive"))
      (node (ref "U2") (pin "F13") (pinfunction "PC7/TRGIO/HRTIM_CHA2/TIM3_CH2/TIM8_CH2/DFSDM1_DATIN3/I2S3_MCK/USART6_RX/SDMMC1_D123DIR/FMC_NE1/SDMMC2_D7/SWPMI_TX/SDMMC1_D7/DCMI_D1/LCD_G6/EVENTOUT_F13") (pintype "bidirectional"))
    )
    (net (code "28") (name "/DCMI_D2 {slash} PG10") (class "Default")
      (node (ref "IC1") (pin "22") (pinfunction "Y4_22") (pintype "passive"))
      (node (ref "U2") (pin "A9") (pinfunction "PG10/HRTIM_FLT5/SPI1_NSS/I2S1_WS/LCD_G3/SAI2_SD_B/FMC_NE3/DCMI_D2/LCD_B2/EVENTOUT_A9") (pintype "bidirectional"))
    )
    (net (code "29") (name "/DCMI_D3 {slash} PG11") (class "Default")
      (node (ref "IC1") (pin "20") (pinfunction "Y5_20") (pintype "passive"))
      (node (ref "U2") (pin "B9") (pinfunction "PG11/LPTIM1_IN2/HRTIM_EEV4/SPI1_SCK/I2S1_CK/SPDIFRX1_IN1/SDMMC2_D2/ETH_MII_TX_EN/ETH_RMII_TX_EN/DCMI_D3/LCD_B3/EVENTOUT_B9") (pintype "bidirectional"))
    )
    (net (code "30") (name "/DCMI_D4 {slash} PE4") (class "Default")
      (node (ref "IC1") (pin "18") (pinfunction "Y6_18") (pintype "passive"))
      (node (ref "U2") (pin "D2") (pinfunction "PE4/TRACED1/SAI1_D2/DFSDM1_DATIN3/TIM15_CH1N/SPI4_NSS/SAI1_FS_A/SAI4_FS_A/SAI4_D2/FMC_A20/DCMI_D4/LCD_B0/EVENTOUT_D2") (pintype "bidirectional"))
    )
    (net (code "31") (name "/DCMI_D5 {slash} PD3") (class "Default")
      (node (ref "IC1") (pin "16") (pinfunction "Y7_16") (pintype "passive"))
      (node (ref "U2") (pin "B12") (pinfunction "PD3/DFSDM1_CKOUT/SPI2_SCK/I2S2_CK/USART2_CTS/USART2_NSS/FMC_CLK/DCMI_D5/LCD_G7/EVENTOUT_B12") (pintype "bidirectional"))
    )
    (net (code "32") (name "/DCMI_D6 {slash} PE5") (class "Default")
      (node (ref "IC1") (pin "14") (pinfunction "Y8_14") (pintype "passive"))
      (node (ref "U2") (pin "D1") (pinfunction "PE5/TRACED2/SAI1_CK2/DFSDM1_CKIN3/TIM15_CH1/SPI4_MISO/SAI1_SCK_A/SAI4_SCK_A/SAI4_CK2/FMC_A21/DCMI_D6/LCD_G0/EVENTOUT_D1") (pintype "bidirectional"))
    )
    (net (code "33") (name "/DCMI_D7 {slash} PE6") (class "Default")
      (node (ref "IC1") (pin "12") (pinfunction "Y9_12") (pintype "passive"))
      (node (ref "U2") (pin "E5") (pinfunction "PE6/TRACED3/TIM1_BKIN2/SAI1_D1/TIM15_CH2/SPI4_MOSI/SAI1_SD_A/SAI4_SD_A/SAI4_D1/SAI2_MCLK_B/TIM1_BKIN2_COMP12/FMC_A22/DCMI_D7/LCD_G1/EVENTOUT_E5") (pintype "bidirectional"))
    )
    (net (code "34") (name "/DCMI_HSYNC {slash} PA4") (class "Default")
      (node (ref "IC1") (pin "9") (pinfunction "HSYNC_9") (pintype "passive"))
      (node (ref "U2") (pin "U3") (pinfunction "PA4/D1PWREN/TIM5_ETR/SPI1_NSS/I2S1_WS/SPI3_NSS/I2S3_WS/USART2_CK/SPI6_NSS/OTG_HS_SOF/DCMI_HSYNC/LCD_VSYNC/EVENTOUT_U3") (pintype "bidirectional"))
    )
    (net (code "35") (name "/DCMI_PIXCLK {slash} PA6") (class "Default")
      (node (ref "IC1") (pin "17") (pinfunction "PCLK_17") (pintype "passive"))
      (node (ref "U2") (pin "R3") (pinfunction "PA6/TIM1_BKIN/TIM3_CH1/TIM8_BKIN/SPI1_MISO/I2S1_SDI/SPI6_MISO/TIM13_CH1/TIM8_BKIN_COMP12/MDIOS_MDC/TIM1_BKIN_COMP12/DCMI_PIXCLK/LCD_G2/EVENTOUT_R3") (pintype "bidirectional"))
    )
    (net (code "36") (name "/DCMI_VSYNC {slash} PG9") (class "Default")
      (node (ref "IC1") (pin "7") (pinfunction "VSYNC_7") (pintype "passive"))
      (node (ref "U2") (pin "A10") (pinfunction "PG9/SPI1_MISO/I2S1_SDI/USART6_RX/SPDIFRX1_IN4/QUADSPI_BK2_IO2/SAI2_FS_B/FMC_NE2/FMC_NCE/DCMI_VSYNC/EVENTOUT_A10") (pintype "bidirectional"))
    )
    (net (code "37") (name "/DISP") (class "Default")
      (node (ref "R60") (pin "2") (pinfunction "2_2") (pintype "passive"))
      (node (ref "U10") (pin "10") (pinfunction "10_10") (pintype "passive"))
    )
    (net (code "38") (name "/FMC_A0 {slash} PF0") (class "Default")
      (node (ref "U2") (pin "G4") (pinfunction "PF0/I2C2_SDA/FMC_A0/EVENTOUT_G4") (pintype "bidirectional"))
      (node (ref "U3") (pin "G8") (pinfunction "A0_G8") (pintype "input"))
    )
    (net (code "39") (name "/FMC_A1 {slash} PF1") (class "Default")
      (node (ref "U2") (pin "G3") (pinfunction "PF1/I2C2_SCL/FMC_A1/EVENTOUT_G3") (pintype "bidirectional"))
      (node (ref "U3") (pin "G9") (pinfunction "A1_G9") (pintype "input"))
    )
    (net (code "40") (name "/FMC_A2 {slash} PF2") (class "Default")
      (node (ref "U2") (pin "G1") (pinfunction "PF2/I2C2_SMBA/FMC_A2/EVENTOUT_G1") (pintype "bidirectional"))
      (node (ref "U3") (pin "F7") (pinfunction "A2_F7") (pintype "input"))
    )
    (net (code "41") (name "/FMC_A3 {slash} PF3") (class "Default")
      (node (ref "U2") (pin "H4") (pinfunction "PF3/FMC_A3/EVENTOUT_H4") (pintype "bidirectional"))
      (node (ref "U3") (pin "F3") (pinfunction "A3_F3") (pintype "input"))
    )
    (net (code "42") (name "/FMC_A4 {slash} PF4") (class "Default")
      (node (ref "U2") (pin "J5") (pinfunction "PF4/FMC_A4/EVENTOUT_J5") (pintype "bidirectional"))
      (node (ref "U3") (pin "G1") (pinfunction "A4_G1") (pintype "input"))
    )
    (net (code "43") (name "/FMC_A5 {slash} PF5") (class "Default")
      (node (ref "U2") (pin "J4") (pinfunction "PF5/FMC_A5/EVENTOUT_J4") (pintype "bidirectional"))
      (node (ref "U3") (pin "G2") (pinfunction "A5_G2") (pintype "input"))
    )
    (net (code "44") (name "/FMC_A6 {slash} PF12") (class "Default")
      (node (ref "U2") (pin "R7") (pinfunction "PF12/FMC_A6/EVENTOUT_R7") (pintype "bidirectional"))
      (node (ref "U3") (pin "G3") (pinfunction "A6_G3") (pintype "input"))
    )
    (net (code "45") (name "/FMC_A7 {slash} PF13") (class "Default")
      (node (ref "U2") (pin "P7") (pinfunction "PF13/DFSDM1_DATIN6/I2C4_SMBA/FMC_A7/EVENTOUT_P7") (pintype "bidirectional"))
      (node (ref "U3") (pin "H1") (pinfunction "A7_H1") (pintype "input"))
    )
    (net (code "46") (name "/FMC_A8 {slash} PF14") (class "Default")
      (node (ref "U2") (pin "P8") (pinfunction "PF14/DFSDM1_CKIN6/I2C4_SCL/FMC_A8/EVENTOUT_P8") (pintype "bidirectional"))
      (node (ref "U3") (pin "H2") (pinfunction "A8_H2") (pintype "input"))
    )
    (net (code "47") (name "/FMC_A9 {slash} PF15") (class "Default")
      (node (ref "U2") (pin "R9") (pinfunction "PF15/I2C4_SDA/FMC_A9/EVENTOUT_R9") (pintype "bidirectional"))
      (node (ref "U3") (pin "J3") (pinfunction "A9_J3") (pintype "input"))
    )
    (net (code "48") (name "/FMC_A10 {slash} PG0") (class "Default")
      (node (ref "U2") (pin "T8") (pinfunction "PG0/FMC_A10/EVENTOUT_T8") (pintype "bidirectional"))
      (node (ref "U3") (pin "G7") (pinfunction "A10_G7") (pintype "input"))
    )
    (net (code "49") (name "/FMC_A11 {slash} PG1") (class "Default")
      (node (ref "U2") (pin "U8") (pinfunction "PG1/FMC_A11/EVENTOUT_U8") (pintype "bidirectional"))
      (node (ref "U3") (pin "H9") (pinfunction "A11_H9") (pintype "input"))
    )
    (net (code "50") (name "/FMC_BA0 {slash} PG4") (class "Default")
      (node (ref "U2") (pin "H14") (pinfunction "PG4/TIM1_BKIN2/TIM1_BKIN2_COMP12/FMC_A14/FMC_BA0/EVENTOUT_H14") (pintype "bidirectional"))
      (node (ref "U3") (pin "J7") (pinfunction "BA0_J7") (pintype "input"))
    )
    (net (code "51") (name "/FMC_BA1 {slash} PG5") (class "Default")
      (node (ref "U2") (pin "G14") (pinfunction "PG5/TIM1_ETR/FMC_A15/FMC_BA1/EVENTOUT_G14") (pintype "bidirectional"))
      (node (ref "U3") (pin "H8") (pinfunction "BA1_H8") (pintype "input"))
    )
    (net (code "52") (name "/FMC_D0 {slash} PD14") (class "Default")
      (node (ref "U2") (pin "P16") (pinfunction "PD14/TIM4_CH3/SAI3_MCLK_B/UART8_CTS/FMC_D0/FMC_DA0/EVENTOUT_P16") (pintype "bidirectional"))
      (node (ref "U3") (pin "R8") (pinfunction "DQ0_R8") (pintype "bidirectional"))
    )
    (net (code "53") (name "/FMC_D1 {slash} PD15") (class "Default")
      (node (ref "U2") (pin "P15") (pinfunction "PD15/TIM4_CH4/SAI3_MCLK_A/UART8_RTS/UART8_DE/FMC_D1/FMC_DA1/EVENTOUT_P15") (pintype "bidirectional"))
      (node (ref "U3") (pin "N7") (pinfunction "DQ1_N7") (pintype "bidirectional"))
    )
    (net (code "54") (name "/FMC_D2 {slash} PD0") (class "Default")
      (node (ref "U2") (pin "D13") (pinfunction "PD0/DFSDM1_CKIN6/SAI3_SCK_A/UART4_RX/FDCAN1_RX/FMC_D2/FMC_DA2/EVENTOUT_D13") (pintype "bidirectional"))
      (node (ref "U3") (pin "R9") (pinfunction "DQ2_R9") (pintype "bidirectional"))
    )
    (net (code "55") (name "/FMC_D3 {slash} PD1") (class "Default")
      (node (ref "U2") (pin "E12") (pinfunction "PD1/DFSDM1_DATIN6/SAI3_SD_A/UART4_TX/FDCAN1_TX/FMC_D3/FMC_DA3/EVENTOUT_E12") (pintype "bidirectional"))
      (node (ref "U3") (pin "N8") (pinfunction "DQ3_N8") (pintype "bidirectional"))
    )
    (net (code "56") (name "/FMC_D4 {slash} PE7") (class "Default")
      (node (ref "U2") (pin "U9") (pinfunction "PE7/TIM1_ETR/DFSDM1_DATIN2/UART7_RX/QUADSPI_BK2_IO0/FMC_D4/FMC_DA4/EVENTOUT_U9") (pintype "bidirectional"))
      (node (ref "U3") (pin "P9") (pinfunction "DQ4_P9") (pintype "bidirectional"))
    )
    (net (code "57") (name "/FMC_D5 {slash} PE8") (class "Default")
      (node (ref "U2") (pin "T9") (pinfunction "PE8/TIM1_CH1N/DFSDM1_CKIN2/UART7_TX/QUADSPI_BK2_IO1/FMC_D5/FMC_DA5/COMP2_OUT/EVENTOUT_T9") (pintype "bidirectional"))
      (node (ref "U3") (pin "M8") (pinfunction "DQ5_M8") (pintype "bidirectional"))
    )
    (net (code "58") (name "/FMC_D6 {slash} PE9") (class "Default")
      (node (ref "U2") (pin "P9") (pinfunction "PE9/TIM1_CH1/DFSDM1_CKOUT/UART7_RTS/UART7_DE/QUADSPI_BK2_IO2/FMC_D6/FMC_DA6/EVENTOUT_P9") (pintype "bidirectional"))
      (node (ref "U3") (pin "M7") (pinfunction "DQ6_M7") (pintype "bidirectional"))
    )
    (net (code "59") (name "/FMC_D7 {slash} PE10") (class "Default")
      (node (ref "U2") (pin "N9") (pinfunction "PE10/TIM1_CH2N/DFSDM1_DATIN4/UART7_CTS/QUADSPI_BK2_IO3/FMC_D7/FMC_DA7/EVENTOUT_N9") (pintype "bidirectional"))
      (node (ref "U3") (pin "L8") (pinfunction "DQ7_L8") (pintype "bidirectional"))
    )
    (net (code "60") (name "/FMC_D8 {slash} PE11") (class "Default")
      (node (ref "U2") (pin "P10") (pinfunction "PE11/TIM1_CH2/DFSDM1_CKIN4/SPI4_NSS/SAI2_SD_B/FMC_D8/FMC_DA8/LCD_G3/EVENTOUT_P10") (pintype "bidirectional"))
      (node (ref "U3") (pin "L2") (pinfunction "DQ8_L2") (pintype "bidirectional"))
    )
    (net (code "61") (name "/FMC_D9 {slash} PE12") (class "Default")
      (node (ref "U2") (pin "R10") (pinfunction "PE12/TIM1_CH3N/DFSDM1_DATIN5/SPI4_SCK/SAI2_SCK_B/FMC_D9/FMC_DA9/COMP1_OUT/LCD_B4/EVENTOUT_R10") (pintype "bidirectional"))
      (node (ref "U3") (pin "M3") (pinfunction "DQ9_M3") (pintype "bidirectional"))
    )
    (net (code "62") (name "/FMC_D10 {slash} PE13") (class "Default")
      (node (ref "U2") (pin "T10") (pinfunction "PE13/TIM1_CH3/DFSDM1_CKIN5/SPI4_MISO/SAI2_FS_B/FMC_D10/FMC_DA10/COMP2_OUT/LCD_DE/EVENTOUT_T10") (pintype "bidirectional"))
      (node (ref "U3") (pin "M2") (pinfunction "DQ10_M2") (pintype "bidirectional"))
    )
    (net (code "63") (name "/FMC_D11 {slash} PE14") (class "Default")
      (node (ref "U2") (pin "U10") (pinfunction "PE14/TIM1_CH4/SPI4_MOSI/SAI2_MCLK_B/FMC_D11/FMC_DA11/LCD_CLK/EVENTOUT_U10") (pintype "bidirectional"))
      (node (ref "U3") (pin "P1") (pinfunction "DQ11_P1") (pintype "bidirectional"))
    )
    (net (code "64") (name "/FMC_D12 {slash} PE15") (class "Default")
      (node (ref "U2") (pin "R11") (pinfunction "PE15/TIM1_BKIN/FMC_D12/FMC_DA12/TIM1_BKIN_COMP12/COMP_TIM1_BKIN/LCD_R7/EVENTOUT_R11") (pintype "bidirectional"))
      (node (ref "U3") (pin "N2") (pinfunction "DQ12_N2") (pintype "bidirectional"))
    )
    (net (code "65") (name "/FMC_D13 {slash} PD8") (class "Default")
      (node (ref "U2") (pin "U16") (pinfunction "PD8/DFSDM1_CKIN3/SAI3_SCK_B/USART3_TX/SPDIFRX1_IN2/FMC_D13/FMC_DA13/EVENTOUT_U16") (pintype "bidirectional"))
      (node (ref "U3") (pin "R1") (pinfunction "DQ13_R1") (pintype "bidirectional"))
    )
    (net (code "66") (name "/FMC_D14 {slash} PD9") (class "Default")
      (node (ref "U2") (pin "T17") (pinfunction "PD9/DFSDM1_DATIN3/SAI3_SD_B/USART3_RX/FDCAN2_RXFD_MODE/FMC_D14/FMC_DA14/EVENTOUT_T17") (pintype "bidirectional"))
      (node (ref "U3") (pin "N3") (pinfunction "DQ14_N3") (pintype "bidirectional"))
    )
    (net (code "67") (name "/FMC_D15 {slash} PD10") (class "Default")
      (node (ref "U2") (pin "T16") (pinfunction "PD10/DFSDM1_CKOUT/SAI3_FS_B/USART3_CK/FDCAN2_TXFD_MODE/FMC_D15/FMC_DA15/LCD_B3/EVENTOUT_T16") (pintype "bidirectional"))
      (node (ref "U3") (pin "R2") (pinfunction "DQ15_R2") (pintype "bidirectional"))
    )
    (net (code "68") (name "/FMC_D16 {slash} PH8") (class "Default")
      (node (ref "U2") (pin "T13") (pinfunction "PH8/TIM5_ETR/I2C3_SDA/FMC_D16/DCMI_HSYNC/LCD_R2/EVENTOUT_T13") (pintype "bidirectional"))
      (node (ref "U3") (pin "E8") (pinfunction "DQ16_E8") (pintype "bidirectional"))
    )
    (net (code "69") (name "/FMC_D17 {slash} PH9") (class "Default")
      (node (ref "U2") (pin "R13") (pinfunction "PH9/TIM12_CH2/I2C3_SMBA/FMC_D17/DCMI_D0/LCD_R3/EVENTOUT_R13") (pintype "bidirectional"))
      (node (ref "U3") (pin "D7") (pinfunction "DQ17_D7") (pintype "bidirectional"))
    )
    (net (code "70") (name "/FMC_D18 {slash} PH10") (class "Default")
      (node (ref "U2") (pin "P13") (pinfunction "PH10/TIM5_CH1/I2C4_SMBA/FMC_D18/DCMI_D1/LCD_R4/EVENTOUT_P13") (pintype "bidirectional"))
      (node (ref "U3") (pin "D8") (pinfunction "DQ18_D8") (pintype "bidirectional"))
    )
    (net (code "71") (name "/FMC_D19 {slash} PH11") (class "Default")
      (node (ref "U2") (pin "P14") (pinfunction "PH11/TIM5_CH2/I2C4_SCL/FMC_D19/DCMI_D2/LCD_R5/EVENTOUT_P14") (pintype "bidirectional"))
      (node (ref "U3") (pin "B9") (pinfunction "DQ19_B9") (pintype "bidirectional"))
    )
    (net (code "72") (name "/FMC_D20 {slash} PH12") (class "Default")
      (node (ref "U2") (pin "R14") (pinfunction "PH12/TIM5_CH3/I2C4_SDA/FMC_D20/DCMI_D3/LCD_R6/EVENTOUT_R14") (pintype "bidirectional"))
      (node (ref "U3") (pin "C8") (pinfunction "DQ20_C8") (pintype "bidirectional"))
    )
    (net (code "73") (name "/FMC_D21 {slash} PH13") (class "Default")
      (node (ref "U2") (pin "D16") (pinfunction "PH13/TIM8_CH1N/UART4_TX/FDCAN1_TX/FMC_D21/LCD_G2/EVENTOUT_D16") (pintype "bidirectional"))
      (node (ref "U3") (pin "A9") (pinfunction "DQ21_A9") (pintype "bidirectional"))
    )
    (net (code "74") (name "/FMC_D22 {slash} PH14") (class "Default")
      (node (ref "U2") (pin "B17") (pinfunction "PH14/TIM8_CH2N/UART4_RX/FDCAN1_RX/FMC_D22/DCMI_D4/LCD_G3/EVENTOUT_B17") (pintype "bidirectional"))
      (node (ref "U3") (pin "C7") (pinfunction "DQ22_C7") (pintype "bidirectional"))
    )
    (net (code "75") (name "/FMC_D23 {slash} PH15") (class "Default")
      (node (ref "U2") (pin "B16") (pinfunction "PH15/TIM8_CH3N/FDCAN1_TXFD_MODE/FMC_D23/DCMI_D11/LCD_G4/EVENTOUT_B16") (pintype "bidirectional"))
      (node (ref "U3") (pin "A8") (pinfunction "DQ23_A8") (pintype "bidirectional"))
    )
    (net (code "76") (name "/FMC_D24 {slash} PI0") (class "Default")
      (node (ref "U2") (pin "A16") (pinfunction "PI0/TIM5_CH4/SPI2_NSS/I2S2_WS/FDCAN1_RXFD_MODE/FMC_D24/DCMI_D13/LCD_G5/EVENTOUT_A16") (pintype "bidirectional"))
      (node (ref "U3") (pin "A2") (pinfunction "DQ24_A2") (pintype "bidirectional"))
    )
    (net (code "77") (name "/FMC_D25 {slash} PI1") (class "Default")
      (node (ref "U2") (pin "A15") (pinfunction "PI1/TIM8_BKIN2/SPI2_SCK/I2S2_CK/TIM8_BKIN2_COMP12/FMC_D25/DCMI_D8/LCD_G6/EVENTOUT_A15") (pintype "bidirectional"))
      (node (ref "U3") (pin "C3") (pinfunction "DQ25_C3") (pintype "bidirectional"))
    )
    (net (code "78") (name "/FMC_D26 {slash} PI2") (class "Default")
      (node (ref "U2") (pin "B15") (pinfunction "PI2/TIM8_CH4/SPI2_MISO/I2S2_SDI/FMC_D26/DCMI_D9/LCD_G7/EVENTOUT_B15") (pintype "bidirectional"))
      (node (ref "U3") (pin "A1") (pinfunction "DQ26_A1") (pintype "bidirectional"))
    )
    (net (code "79") (name "/FMC_D27 {slash} PI3") (class "Default")
      (node (ref "U2") (pin "C14") (pinfunction "PI3/TIM8_ETR/SPI2_MOSI/I2S2_SDO/FMC_D27/DCMI_D10/EVENTOUT_C14") (pintype "bidirectional"))
      (node (ref "U3") (pin "C2") (pinfunction "DQ27_C2") (pintype "bidirectional"))
    )
    (net (code "80") (name "/FMC_D28 {slash} PI6") (class "Default")
      (node (ref "U2") (pin "A2") (pinfunction "PI6/TIM8_CH2/SAI2_SD_A/FMC_D28/DCMI_D6/LCD_B6/EVENTOUT_A2") (pintype "bidirectional"))
      (node (ref "U3") (pin "B1") (pinfunction "DQ28_B1") (pintype "bidirectional"))
    )
    (net (code "81") (name "/FMC_D29 {slash} PI7") (class "Default")
      (node (ref "U2") (pin "B3") (pinfunction "PI7/TIM8_CH3/SAI2_FS_A/FMC_D29/DCMI_D7/LCD_B7/EVENTOUT_B3") (pintype "bidirectional"))
      (node (ref "U3") (pin "D2") (pinfunction "DQ29_D2") (pintype "bidirectional"))
    )
    (net (code "82") (name "/FMC_D30 {slash} PI9") (class "Default")
      (node (ref "U2") (pin "E2") (pinfunction "PI9/UART4_RX/FDCAN1_RX/FMC_D30/LCD_VSYNC/EVENTOUT_E2") (pintype "bidirectional"))
      (node (ref "U3") (pin "D3") (pinfunction "DQ30_D3") (pintype "bidirectional"))
    )
    (net (code "83") (name "/FMC_D31 {slash} PI10") (class "Default")
      (node (ref "U2") (pin "F3") (pinfunction "PI10/FDCAN1_RXFD_MODE/ETH_MII_RX_ER/FMC_D31/LCD_HSYNC/EVENTOUT_F3") (pintype "bidirectional"))
      (node (ref "U3") (pin "E2") (pinfunction "DQ31_E2") (pintype "bidirectional"))
    )
    (net (code "84") (name "/FMC_NBL0 {slash} PE0") (class "Default")
      (node (ref "U2") (pin "C4") (pinfunction "PE0/LPTIM1_ETR/TIM4_ETR/HRTIM_SCIN/LPTIM2_ETR/UART8_RX/FDCAN1_RXFD_MODE/SAI2_MCLK_A/FMC_NBL0/DCMI_D2/EVENTOUT_C4") (pintype "bidirectional"))
      (node (ref "U3") (pin "K9") (pinfunction "DQM0_K9") (pintype "bidirectional"))
    )
    (net (code "85") (name "/FMC_NBL1 {slash} PE1") (class "Default")
      (node (ref "U2") (pin "B4") (pinfunction "PE1/LPTIM1_IN2/HRTIM_SCOUT/UART8_TX/FDCAN1_TXFD_MODE/FMC_NBL1/DCMI_D3/EVENTOUT_B4") (pintype "bidirectional"))
      (node (ref "U3") (pin "K1") (pinfunction "DQM1_K1") (pintype "bidirectional"))
    )
    (net (code "86") (name "/FMC_NBL2 {slash} PI4") (class "Default")
      (node (ref "U2") (pin "A4") (pinfunction "PI4/TIM8_BKIN/SAI2_MCLK_A/TIM8_BKIN_COMP12/FMC_NBL2/DCMI_D5/LCD_B4/EVENTOUT_A4") (pintype "bidirectional"))
      (node (ref "U3") (pin "F8") (pinfunction "DQM2_F8") (pintype "bidirectional"))
    )
    (net (code "87") (name "/FMC_NBL3 {slash} PI5") (class "Default")
      (node (ref "U2") (pin "A3") (pinfunction "PI5/TIM8_CH1/SAI2_SCK_A/FMC_NBL3/DCMI_VSYNC/LCD_B5/EVENTOUT_A3") (pintype "bidirectional"))
      (node (ref "U3") (pin "F2") (pinfunction "DQM3_F2") (pintype "bidirectional"))
    )
    (net (code "88") (name "/FMC_SDCKE0 {slash} PH2") (class "Default")
      (node (ref "U2") (pin "N2") (pinfunction "PH2/LPTIM1_IN2/QUADSPI_BK2_IO0/SAI2_SCK_B/ETH_MII_CRS/FMC_SDCKE0/LCD_R0/EVENTOUT_N2") (pintype "bidirectional"))
      (node (ref "U3") (pin "J2") (pinfunction "CKE_J2") (pintype "input"))
    )
    (net (code "89") (name "/FMC_SDCLK {slash} PG8") (class "Default")
      (node (ref "U2") (pin "F15") (pinfunction "PG8/TIM8_ETR/SPI6_NSS/USART6_RTS/USART6_DE/SPDIFRX1_IN3/ETH_PPS_OUT/FMC_SDCLK/LCD_G7/EVENTOUT_F15") (pintype "bidirectional"))
      (node (ref "U3") (pin "J1") (pinfunction "CLK_J1") (pintype "input"))
    )
    (net (code "90") (name "/FMC_SDNCAS {slash} PG15") (class "Default")
      (node (ref "U2") (pin "D6") (pinfunction "PG15/USART6_CTS/USART6_NSS/FMC_SDNCAS/DCMI_D13/EVENTOUT_D6") (pintype "bidirectional"))
      (node (ref "U3") (pin "K7") (pinfunction "CAS#_K7") (pintype "input"))
    )
    (net (code "91") (name "/FMC_SDNE0 {slash} PH3") (class "Default")
      (node (ref "U2") (pin "P2") (pinfunction "PH3/QUADSPI_BK2_IO1/SAI2_MCLK_B/ETH_MII_COL/FMC_SDNE0/LCD_R1/EVENTOUT_P2") (pintype "bidirectional"))
      (node (ref "U3") (pin "J8") (pinfunction "CS#_J8") (pintype "input"))
    )
    (net (code "92") (name "/FMC_SDNRAS {slash} PF11") (class "Default")
      (node (ref "U2") (pin "T7") (pinfunction "PF11/SPI5_MOSI/SAI2_SD_B/FMC_SDNRAS/DCMI_D12/EVENTOUT_T7") (pintype "bidirectional"))
      (node (ref "U3") (pin "J9") (pinfunction "RAS#_J9") (pintype "input"))
    )
    (net (code "93") (name "/FMC_SDNWE {slash} PC0") (class "Default")
      (node (ref "U2") (pin "L2") (pinfunction "PC0/DFSDM1_CKIN0/DFSDM1_DATIN4/SAI2_FS_B/OTG_HS_ULPI_STP/FMC_SDNWE/LCD_R5/EVENTOUT_L2") (pintype "bidirectional"))
      (node (ref "U3") (pin "K8") (pinfunction "WE#_K8") (pintype "input"))
    )
    (net (code "94") (name "/IIC2_SCL {slash} PH4") (class "Default")
      (node (ref "R44") (pin "1") (pinfunction "1_1") (pintype "passive"))
      (node (ref "U2") (pin "P3") (pinfunction "PH4/I2C2_SCL/LCD_G5/OTG_HS_ULPI_NXT/LCD_G4/EVENTOUT_P3") (pintype "bidirectional"))
    )
    (net (code "95") (name "/IIC2_SDA {slash} PH5") (class "Default")
      (node (ref "R45") (pin "1") (pinfunction "1_1") (pintype "passive"))
      (node (ref "U2") (pin "P4") (pinfunction "PH5/I2C2_SDA/SPI5_NSS/FMC_SDNWE/EVENTOUT_P4") (pintype "bidirectional"))
    )
    (net (code "96") (name "/IIC_SCLK {slash} PG2") (class "Default")
      (node (ref "R42") (pin "2") (pinfunction "2_2") (pintype "passive"))
      (node (ref "U2") (pin "H16") (pinfunction "PG2/TIM8_BKIN/TIM8_BKIN_COMP12/FMC_A12/EVENTOUT_H16") (pintype "bidirectional"))
    )
    (net (code "97") (name "/IIC_SDA {slash} PG3") (class "Default")
      (node (ref "R43") (pin "2") (pinfunction "2_2") (pintype "passive"))
      (node (ref "U2") (pin "H15") (pinfunction "PG3/TIM8_BKIN2/TIM8_BKIN2_COMP12/FMC_A13/EVENTOUT_H15") (pintype "bidirectional"))
    )
    (net (code "98") (name "/L3.3V") (class "Default")
      (node (ref "10") (pin "2") (pinfunction "2_2") (pintype "passive"))
      (node (ref "20") (pin "2") (pinfunction "2_2") (pintype "passive"))
      (node (ref "23") (pin "2") (pinfunction "2_2") (pintype "passive"))
      (node (ref "9") (pin "2") (pinfunction "2_2") (pintype "passive"))
      (node (ref "D4") (pin "2") (pinfunction "K_2") (pintype "passive"))
      (node (ref "FB5") (pin "2") (pinfunction "2_2") (pintype "passive"))
      (node (ref "JP3") (pin "5") (pinfunction "5_5") (pintype "passive"))
      (node (ref "R60") (pin "1") (pinfunction "1_1") (pintype "passive"))
      (node (ref "U10") (pin "37") (pinfunction "37_37") (pintype "passive"))
    )
    (net (code "99") (name "/LCD_B0 {slash} PJ12") (class "Default")
      (node (ref "RP5") (pin "1") (pintype "passive"))
      (node (ref "U2") (pin "D11") (pinfunction "PJ12/TRGOUT/LCD_G3/LCD_B0/EVENTOUT_D11") (pintype "bidirectional"))
    )
    (net (code "100") (name "/LCD_B1 {slash} PJ13") (class "Default")
      (node (ref "RP5") (pin "2") (pintype "passive"))
      (node (ref "U2") (pin "E10") (pinfunction "PJ13/LCD_B4/LCD_B1/EVENTOUT_E10") (pintype "bidirectional"))
    )
    (net (code "101") (name "/LCD_B2 {slash} PJ14") (class "Default")
      (node (ref "RP5") (pin "3") (pintype "passive"))
      (node (ref "U2") (pin "D10") (pinfunction "PJ14/LCD_B2/EVENTOUT_D10") (pintype "bidirectional"))
    )
    (net (code "102") (name "/LCD_B3 {slash} PJ15") (class "Default")
      (node (ref "RP5") (pin "4") (pintype "passive"))
      (node (ref "U2") (pin "B10") (pinfunction "PJ15/LCD_B3/EVENTOUT_B10") (pintype "bidirectional"))
    )
    (net (code "103") (name "/LCD_B4 {slash} PK3") (class "Default")
      (node (ref "RP6") (pin "1") (pintype "passive"))
      (node (ref "U2") (pin "C8") (pinfunction "PK3/LCD_B4/EVENTOUT_C8") (pintype "bidirectional"))
    )
    (net (code "104") (name "/LCD_B5 {slash} PK4") (class "Default")
      (node (ref "RP6") (pin "2") (pintype "passive"))
      (node (ref "U2") (pin "B8") (pinfunction "PK4/LCD_B5/EVENTOUT_B8") (pintype "bidirectional"))
    )
    (net (code "105") (name "/LCD_B6 {slash} PK5") (class "Default")
      (node (ref "RP6") (pin "3") (pintype "passive"))
      (node (ref "U2") (pin "A8") (pinfunction "PK5/LCD_B6/EVENTOUT_A8") (pintype "bidirectional"))
    )
    (net (code "106") (name "/LCD_B7 {slash} PK6") (class "Default")
      (node (ref "RP6") (pin "4") (pintype "passive"))
      (node (ref "U2") (pin "C7") (pinfunction "PK6/LCD_B7/EVENTOUT_C7") (pintype "bidirectional"))
    )
    (net (code "107") (name "/LCD_BL {slash} PH6") (class "Default")
      (node (ref "R30") (pin "2") (pinfunction "2_2") (pintype "passive"))
      (node (ref "U2") (pin "T11") (pinfunction "PH6/TIM12_CH1/I2C2_SMBA/SPI5_SCK/ETH_MII_RXD2/FMC_SDNE1/DCMI_D8/EVENTOUT_T11") (pintype "bidirectional"))
    )
    (net (code "108") (name "/LCD_CLK {slash} PI14") (class "Default")
      (node (ref "RP7") (pin "1") (pintype "passive"))
      (node (ref "U2") (pin "H3") (pinfunction "PI14/LCD_CLK/EVENTOUT_H3") (pintype "bidirectional"))
    )
    (net (code "109") (name "/LCD_DE {slash} PK7") (class "Default")
      (node (ref "RP7") (pin "4") (pintype "passive"))
      (node (ref "U2") (pin "D7") (pinfunction "PK7/LCD_DE/EVENTOUT_D7") (pintype "bidirectional"))
    )
    (net (code "110") (name "/LCD_G0 {slash} PJ7") (class "Default")
      (node (ref "RP3") (pin "1") (pintype "passive"))
      (node (ref "U2") (pin "N14") (pinfunction "PJ7/TRGIN/TIM8_CH2N/LCD_G0/EVENTOUT_N14") (pintype "bidirectional"))
    )
    (net (code "111") (name "/LCD_G1 {slash} PJ8") (class "Default")
      (node (ref "RP3") (pin "2") (pintype "passive"))
      (node (ref "U2") (pin "N13") (pinfunction "PJ8/TIM1_CH3N/TIM8_CH1/UART8_TX/LCD_G1/EVENTOUT_N13") (pintype "bidirectional"))
    )
    (net (code "112") (name "/LCD_G2 {slash} PJ9") (class "Default")
      (node (ref "RP3") (pin "3") (pintype "passive"))
      (node (ref "U2") (pin "M14") (pinfunction "PJ9/TIM1_CH3/TIM8_CH1N/UART8_RX/LCD_G2/EVENTOUT_M14") (pintype "bidirectional"))
    )
    (net (code "113") (name "/LCD_G3 {slash} PJ10") (class "Default")
      (node (ref "RP3") (pin "4") (pintype "passive"))
      (node (ref "U2") (pin "L14") (pinfunction "PJ10/TIM1_CH2N/TIM8_CH2/SPI5_MOSI/LCD_G3/EVENTOUT_L14") (pintype "bidirectional"))
    )
    (net (code "114") (name "/LCD_G4 {slash} PJ11") (class "Default")
      (node (ref "RP4") (pin "1") (pintype "passive"))
      (node (ref "U2") (pin "K14") (pinfunction "PJ11/TIM1_CH2/TIM8_CH2N/SPI5_MISO/LCD_G4/EVENTOUT_K14") (pintype "bidirectional"))
    )
    (net (code "115") (name "/LCD_G5 {slash} PK0") (class "Default")
      (node (ref "RP4") (pin "2") (pintype "passive"))
      (node (ref "U2") (pin "J14") (pinfunction "PK0/TIM1_CH1N/TIM8_CH3/SPI5_SCK/LCD_G5/EVENTOUT_J14") (pintype "bidirectional"))
    )
    (net (code "116") (name "/LCD_G6 {slash} PK1") (class "Default")
      (node (ref "RP4") (pin "3") (pintype "passive"))
      (node (ref "U2") (pin "J15") (pinfunction "PK1/TIM1_CH1/TIM8_CH3N/SPI5_NSS/LCD_G6/EVENTOUT_J15") (pintype "bidirectional"))
    )
    (net (code "117") (name "/LCD_G7 {slash} PK2") (class "Default")
      (node (ref "RP4") (pin "4") (pintype "passive"))
      (node (ref "U2") (pin "H17") (pinfunction "PK2/TIM1_BKIN/TIM8_BKIN/TIM8_BKIN_COMP12/TIM1_BKIN_COMP12/LCD_G7/EVENTOUT_H17") (pintype "bidirectional"))
    )
    (net (code "118") (name "/LCD_HS {slash} PI12") (class "Default")
      (node (ref "RP7") (pin "2") (pintype "passive"))
      (node (ref "U2") (pin "H1") (pinfunction "PI12/LCD_HSYNC/EVENTOUT_H1") (pintype "bidirectional"))
    )
    (net (code "119") (name "/LCD_R0 {slash} PI15") (class "Default")
      (node (ref "RP1") (pin "1") (pintype "passive"))
      (node (ref "U2") (pin "P5") (pinfunction "PI15/LCD_G2/LCD_R0/EVENTOUT_P5") (pintype "bidirectional"))
    )
    (net (code "120") (name "/LCD_R1 {slash} PJ0") (class "Default")
      (node (ref "RP1") (pin "2") (pintype "passive"))
      (node (ref "U2") (pin "N6") (pinfunction "PJ0/LCD_R7/LCD_R1/EVENTOUT_N6") (pintype "bidirectional"))
    )
    (net (code "121") (name "/LCD_R2 {slash} PJ1") (class "Default")
      (node (ref "RP1") (pin "3") (pintype "passive"))
      (node (ref "U2") (pin "P6") (pinfunction "PJ1/LCD_R2/EVENTOUT_P6") (pintype "bidirectional"))
    )
    (net (code "122") (name "/LCD_R3 {slash} PJ2") (class "Default")
      (node (ref "RP1") (pin "4") (pintype "passive"))
      (node (ref "U2") (pin "T6") (pinfunction "PJ2/LCD_R3/EVENTOUT_T6") (pintype "bidirectional"))
    )
    (net (code "123") (name "/LCD_R4 {slash} PJ3") (class "Default")
      (node (ref "RP2") (pin "1") (pintype "passive"))
      (node (ref "U2") (pin "U6") (pinfunction "PJ3/LCD_R4/EVENTOUT_U6") (pintype "bidirectional"))
    )
    (net (code "124") (name "/LCD_R5 {slash} PJ4") (class "Default")
      (node (ref "RP2") (pin "2") (pintype "passive"))
      (node (ref "U2") (pin "U7") (pinfunction "PJ4/LCD_R5/EVENTOUT_U7") (pintype "bidirectional"))
    )
    (net (code "125") (name "/LCD_R6 {slash} PJ5") (class "Default")
      (node (ref "RP2") (pin "3") (pintype "passive"))
      (node (ref "U2") (pin "R12") (pinfunction "PJ5/LCD_R6/EVENTOUT_R12") (pintype "bidirectional"))
    )
    (net (code "126") (name "/LCD_R7 {slash} PJ6") (class "Default")
      (node (ref "RP2") (pin "4") (pintype "passive"))
      (node (ref "U2") (pin "N15") (pinfunction "PJ6/TIM8_CH2/LCD_R7/EVENTOUT_N15") (pintype "bidirectional"))
    )
    (net (code "127") (name "/LCD_VS {slash} PI13") (class "Default")
      (node (ref "RP7") (pin "3") (pintype "passive"))
      (node (ref "U2") (pin "H2") (pinfunction "PI13/LCD_VSYNC/EVENTOUT_H2") (pintype "bidirectional"))
    )
    (net (code "128") (name "/LED {slash} PC13") (class "Default")
      (node (ref "LED5") (pin "2") (pinfunction "K_2") (pintype "passive"))
      (node (ref "U2") (pin "E3") (pinfunction "PC13/EVENTOUT_E3") (pintype "bidirectional"))
    )
    (net (code "129") (name "/LED+") (class "Default")
      (node (ref "7") (pin "2") (pinfunction "2_2") (pintype "passive"))
      (node (ref "D1") (pin "2") (pinfunction "K_2") (pintype "passive"))
      (node (ref "U10") (pin "39") (pinfunction "39_39") (pintype "passive"))
    )
    (net (code "130") (name "/LED-") (class "Default")
      (node (ref "R29") (pin "1") (pinfunction "1_1") (pintype "passive"))
      (node (ref "R33") (pin "1") (pinfunction "1_1") (pintype "passive"))
      (node (ref "U10") (pin "40") (pinfunction "40_40") (pintype "passive"))
    )
    (net (code "131") (name "/OS_25M_IN") (class "Default")
      (node (ref "C39") (pin "2") (pinfunction "2_2") (pintype "passive"))
      (node (ref "U2") (pin "J2") (pinfunction "PH0-OSC_IN(PH0)/EVENTOUT_J2") (pintype "bidirectional"))
      (node (ref "X2") (pin "3") (pinfunction "3_3") (pintype "passive"))
    )
    (net (code "132") (name "/OS_25M_OUT") (class "Default")
      (node (ref "C38") (pin "2") (pinfunction "2_2") (pintype "passive"))
      (node (ref "U2") (pin "J1") (pinfunction "PH1-OSC_OUT(PH1)/EVENTOUT_J1") (pintype "bidirectional"))
      (node (ref "X2") (pin "1") (pinfunction "1_1") (pintype "passive"))
    )
    (net (code "133") (name "/OS_32K_IN") (class "Default")
      (node (ref "C40") (pin "1") (pinfunction "1_1") (pintype "passive"))
      (node (ref "U2") (pin "C2") (pinfunction "PC14-OSC32_IN/EVENTOUT_C2") (pintype "bidirectional"))
      (node (ref "X3") (pin "2") (pinfunction "2_2") (pintype "passive"))
    )
    (net (code "134") (name "/OS_32K_OUT") (class "Default")
      (node (ref "C41") (pin "1") (pinfunction "1_1") (pintype "passive"))
      (node (ref "U2") (pin "C1") (pinfunction "PC15-OSC32_OUT/EVENTOUT_C1") (pintype "bidirectional"))
      (node (ref "X3") (pin "1") (pinfunction "1_1") (pintype "passive"))
    )
    (net (code "135") (name "/PA9") (class "Default")
      (node (ref "JP1") (pin "8") (pinfunction "8_8") (pintype "passive"))
      (node (ref "R10") (pin "2") (pinfunction "2_2") (pintype "passive"))
      (node (ref "U2") (pin "D15") (pinfunction "PA9/TIM1_CH2/HRTIM_CHC1/LPUART1_TX/I2C3_SMBA/SPI2_SCK/I2S2_CK/USART1_TX/FDCAN1_RXFD_MODE/DCMI_D0/LCD_R5/EVENTOUT_D15") (pintype "bidirectional"))
    )
    (net (code "136") (name "/PA10") (class "Default")
      (node (ref "JP1") (pin "6") (pinfunction "6_6") (pintype "passive"))
      (node (ref "R9") (pin "2") (pinfunction "2_2") (pintype "passive"))
      (node (ref "U2") (pin "D14") (pinfunction "PA10/TIM1_CH3/HRTIM_CHC2/LPUART1_RX/USART1_RX/FDCAN1_TXFD_MODE/OTG_FS_ID/MDIOS_MDIO/LCD_B4/DCMI_D1/LCD_B1/EVENTOUT_D14") (pintype "bidirectional"))
    )
    (net (code "137") (name "/PA11") (class "Default")
      (node (ref "U2") (pin "E17") (pinfunction "PA11/TIM1_CH4/HRTIM_CHD1/LPUART1_CTS/SPI2_NSS/I2S2_WS/UART4_RX/USART1_CTS/USART1_NSS/FDCAN1_RX/OTG_FS_DM/LCD_R4/EVENTOUT_E17") (pintype "bidirectional"))
      (node (ref "U5") (pin "A7") (pinfunction "DN1_A7") (pintype "passive"))
      (node (ref "U5") (pin "B7") (pinfunction "DN2_B7") (pintype "passive"))
    )
    (net (code "138") (name "/PA12") (class "Default")
      (node (ref "U2") (pin "E16") (pinfunction "PA12/TIM1_ETR/HRTIM_CHD2/LPUART1_RTS/LPUART1_DE/SPI2_SCK/I2S2_CK/UART4_TX/USART1_RTS/USART1_DE/SAI2_FS_B/FDCAN1_TX/OTG_FS_DP/LCD_R5/EVENTOUT_E16") (pintype "bidirectional"))
      (node (ref "U5") (pin "A6") (pinfunction "DP1_A6") (pintype "passive"))
      (node (ref "U5") (pin "B6") (pinfunction "DP2_B6") (pintype "passive"))
    )
    (net (code "139") (name "/PB13") (class "Default")
      (node (ref "R24") (pin "2") (pinfunction "2_2") (pintype "passive"))
      (node (ref "SW1") (pin "2") (pinfunction "2_2") (pintype "passive"))
      (node (ref "U2") (pin "U14") (pinfunction "PB13/TIM1_CH1N/LPTIM2_OUT/SPI2_SCK/I2S2_CK/DFSDM1_CKIN1/USART3_CTS/USART3_NSS/FDCAN2_TX/OTG_HS_ULPI_D6/ETH_MII_TXD1/ETH_RMII_TXD1/UART5_TX/EVENTOUT_U14") (pintype "bidirectional"))
    )
    (net (code "140") (name "/PC8") (class "Default")
      (node (ref "P1") (pin "7") (pinfunction "DATA_0_7") (pintype "passive"))
      (node (ref "R20") (pin "2") (pinfunction "2_2") (pintype "passive"))
      (node (ref "U2") (pin "E13") (pinfunction "PC8/TRACED1/HRTIM_CHB1/TIM3_CH3/TIM8_CH3/USART6_CK/UART5_RTS/UART5_DE/FMC_NE2/FMC_NCE/SWPMI_RX/SDMMC1_D0/DCMI_D2/EVENTOUT_E13") (pintype "bidirectional"))
    )
    (net (code "141") (name "/PC9") (class "Default")
      (node (ref "P1") (pin "8") (pinfunction "DATA_1_8") (pintype "passive"))
      (node (ref "R19") (pin "2") (pinfunction "2_2") (pintype "passive"))
      (node (ref "U2") (pin "E14") (pinfunction "PC9/MCO2/TIM3_CH4/TIM8_CH4/I2C3_SDA/I2S_CKIN/UART5_CTS/QUADSPI_BK1_IO0/LCD_G3/SWPMI_SUSPEND/SDMMC1_D1/DCMI_D3/LCD_B2/EVENTOUT_E14") (pintype "bidirectional"))
    )
    (net (code "142") (name "/PC10") (class "Default")
      (node (ref "P1") (pin "1") (pinfunction "DATA_2_1") (pintype "passive"))
      (node (ref "R23") (pin "2") (pinfunction "2_2") (pintype "passive"))
      (node (ref "U2") (pin "A13") (pinfunction "PC10/HRTIM_EEV1/DFSDM1_CKIN5/SPI3_SCK/I2S3_CK/USART3_TX/UART4_TX/QUADSPI_BK1_IO1/SDMMC1_D2/DCMI_D8/LCD_R2/EVENTOUT_A13") (pintype "bidirectional"))
    )
    (net (code "143") (name "/PC11") (class "Default")
      (node (ref "P1") (pin "2") (pinfunction "DATA_3_2") (pintype "passive"))
      (node (ref "R22") (pin "2") (pinfunction "2_2") (pintype "passive"))
      (node (ref "U2") (pin "B13") (pinfunction "PC11/HRTIM_FLT2/DFSDM1_DATIN5/SPI3_MISO/I2S3_SDI/USART3_RX/UART4_RX/QUADSPI_BK2_NCS/SDMMC1_D3/DCMI_D4/EVENTOUT_B13") (pintype "bidirectional"))
    )
    (net (code "144") (name "/PC12") (class "Default")
      (node (ref "P1") (pin "5") (pinfunction "CLK_5") (pintype "passive"))
      (node (ref "U2") (pin "C12") (pinfunction "PC12/TRACED3/HRTIM_EEV2/SPI3_MOSI/I2S3_SDO/USART3_CK/UART5_TX/SDMMC1_CK/DCMI_D9/EVENTOUT_C12") (pintype "bidirectional"))
    )
    (net (code "145") (name "/PD2") (class "Default")
      (node (ref "P1") (pin "3") (pinfunction "CMD_3") (pintype "passive"))
      (node (ref "R21") (pin "2") (pinfunction "2_2") (pintype "passive"))
      (node (ref "U2") (pin "D12") (pinfunction "PD2/TRACED2/TIM3_ETR/UART5_RX/SDMMC1_CMD/DCMI_D11/EVENTOUT_D12") (pintype "bidirectional"))
    )
    (net (code "146") (name "/PI8") (class "Default")
      (node (ref "R47") (pin "1") (pinfunction "1_1") (pintype "passive"))
      (node (ref "U2") (pin "E4") (pinfunction "PI8/EVENTOUT_E4") (pintype "bidirectional"))
    )
    (net (code "147") (name "/PI11") (class "Default")
      (node (ref "R46") (pin "1") (pinfunction "1_1") (pintype "passive"))
      (node (ref "U2") (pin "F4") (pinfunction "PI11/LCD_G6/OTG_HS_ULPI_DIR/EVENTOUT_F4") (pintype "bidirectional"))
    )
    (net (code "148") (name "/QSPI_BK1_IO0 {slash} PF8") (class "Default")
      (node (ref "U2") (pin "K4") (pinfunction "PF8/TIM16_CH1N/SPI5_MISO/SAI1_SCK_B/UART7_RTS/UART7_DE/SAI4_SCK_B/TIM13_CH1/QUADSPI_BK1_IO0/EVENTOUT_K4") (pintype "bidirectional"))
      (node (ref "U6") (pin "5") (pinfunction "DI(IO0)_5") (pintype "passive"))
    )
    (net (code "149") (name "/QSPI_BK1_IO1 {slash} PF9") (class "Default")
      (node (ref "U2") (pin "L4") (pinfunction "PF9/TIM17_CH1N/SPI5_MOSI/SAI1_FS_B/UART7_CTS/SAI4_FS_B/TIM14_CH1/QUADSPI_BK1_IO1/EVENTOUT_L4") (pintype "bidirectional"))
      (node (ref "U6") (pin "2") (pinfunction "DO(IO1)_2") (pintype "passive"))
    )
    (net (code "150") (name "/QSPI_BK1_IO2 {slash} PF7") (class "Default")
      (node (ref "U2") (pin "K3") (pinfunction "PF7/TIM17_CH1/SPI5_SCK/SAI1_MCLK_B/UART7_TX/SAI4_MCLK_B/QUADSPI_BK1_IO2/EVENTOUT_K3") (pintype "bidirectional"))
      (node (ref "U6") (pin "3") (pinfunction "WP#(IO2)_3") (pintype "passive"))
    )
    (net (code "151") (name "/QSPI_BK1_IO3 {slash} PF6") (class "Default")
      (node (ref "U2") (pin "K2") (pinfunction "PF6/TIM16_CH1/SPI5_NSS/SAI1_SD_B/UART7_RX/SAI4_SD_B/QUADSPI_BK1_IO3/EVENTOUT_K2") (pintype "bidirectional"))
      (node (ref "U6") (pin "7") (pinfunction "HOLDor#/RESET#(IO3)_7") (pintype "passive"))
    )
    (net (code "152") (name "/QSPI_BK1_NCS {slash} PG6") (class "Default")
      (node (ref "U2") (pin "G15") (pinfunction "PG6/TIM17_BKIN/HRTIM_CHE1/QUADSPI_BK1_NCS/FMC_NE3/DCMI_D12/LCD_R7/EVENTOUT_G15") (pintype "bidirectional"))
      (node (ref "U6") (pin "1") (pinfunction "CS#_1") (pintype "passive"))
    )
    (net (code "153") (name "/QSPI_CLK {slash} PF10") (class "Default")
      (node (ref "U2") (pin "L3") (pinfunction "PF10/TIM16_BKIN/SAI1_D3/QUADSPI_CLK/SAI4_D3/DCMI_D11/LCD_DE/EVENTOUT_L3") (pintype "bidirectional"))
      (node (ref "U6") (pin "6") (pinfunction "CLK_6") (pintype "passive"))
    )
    (net (code "154") (name "/RST") (class "Default")
      (node (ref "C36") (pin "1") (pinfunction "1_1") (pintype "passive"))
      (node (ref "JP1") (pin "10") (pinfunction "10_10") (pintype "passive"))
      (node (ref "Q1") (pin "3") (pinfunction "C_3") (pintype "passive"))
      (node (ref "R11") (pin "2") (pinfunction "2_2") (pintype "passive"))
      (node (ref "R25") (pin "1") (pinfunction "1_1") (pintype "passive"))
      (node (ref "SW3") (pin "1") (pinfunction "1_1") (pintype "passive"))
      (node (ref "U2") (pin "K1") (pinfunction "NRST_K1") (pintype "bidirectional"))
    )
    (net (code "155") (name "/SWCLK {slash} PA14") (class "Default")
      (node (ref "JP1") (pin "4") (pinfunction "4_4") (pintype "passive"))
      (node (ref "R8") (pin "2") (pinfunction "2_2") (pintype "passive"))
      (node (ref "U2") (pin "B14") (pinfunction "PA14/JTCK-SWCLK/EVENTOUT_B14") (pintype "bidirectional"))
    )
    (net (code "156") (name "/SWDIO {slash} PA13") (class "Default")
      (node (ref "JP1") (pin "2") (pinfunction "2_2") (pintype "passive"))
      (node (ref "R7") (pin "2") (pinfunction "2_2") (pintype "passive"))
      (node (ref "U2") (pin "C15") (pinfunction "PA13/JTMS-SWDIO/EVENTOUT_C15") (pintype "bidirectional"))
    )
    (net (code "157") (name "/VBAT") (class "Default")
      (node (ref "C47") (pin "1") (pinfunction "1_1") (pintype "passive"))
      (node (ref "D5") (pin "3") (pinfunction "3_3") (pintype "passive"))
      (node (ref "U2") (pin "B1") (pinfunction "VBAT_B1") (pintype "power_in"))
    )
    (net (code "158") (name "/VBAT-EXT") (class "Default")
      (node (ref "D5") (pin "1") (pinfunction "1_1") (pintype "passive"))
      (node (ref "JP2") (pin "4") (pinfunction "4_4") (pintype "passive"))
    )
    (net (code "159") (name "/VDDA") (class "Default")
      (node (ref "C43") (pin "2") (pinfunction "2_2") (pintype "passive"))
      (node (ref "C44") (pin "2") (pinfunction "2_2") (pintype "passive"))
      (node (ref "FB4") (pin "2") (pinfunction "2_2") (pintype "passive"))
      (node (ref "R36") (pin "1") (pinfunction "1_1") (pintype "passive"))
      (node (ref "U2") (pin "L1") (pinfunction "VDDA_L1") (pintype "power_in"))
    )
    (net (code "160") (name "/VREF") (class "Default")
      (node (ref "C45") (pin "2") (pinfunction "2_2") (pintype "passive"))
      (node (ref "C46") (pin "2") (pinfunction "2_2") (pintype "passive"))
      (node (ref "JP2") (pin "2") (pinfunction "2_2") (pintype "passive"))
      (node (ref "R36") (pin "2") (pinfunction "2_2") (pintype "passive"))
      (node (ref "U2") (pin "M1") (pinfunction "VREF+_M1") (pintype "input"))
    )
    (net (code "161") (name "AF-2.8V_ov") (class "Default")
      (node (ref "14") (pin "2") (pinfunction "2_2") (pintype "passive"))
      (node (ref "15") (pin "2") (pinfunction "2_2") (pintype "passive"))
      (node (ref "IC1") (pin "23") (pinfunction "AF-VCC_23") (pintype "passive"))
      (node (ref "U8") (pin "2") (pinfunction "VOUT_2") (pintype "passive"))
    )
    (net (code "162") (name "GND") (class "Default")
      (node (ref "1") (pin "1") (pinfunction "1_1") (pintype "passive"))
      (node (ref "10") (pin "1") (pinfunction "1_1") (pintype "passive"))
      (node (ref "11") (pin "1") (pinfunction "1_1") (pintype "passive"))
      (node (ref "12") (pin "1") (pinfunction "1_1") (pintype "passive"))
      (node (ref "13") (pin "1") (pinfunction "1_1") (pintype "passive"))
      (node (ref "14") (pin "1") (pinfunction "1_1") (pintype "passive"))
      (node (ref "15") (pin "1") (pinfunction "1_1") (pintype "passive"))
      (node (ref "16") (pin "1") (pinfunction "1_1") (pintype "passive"))
      (node (ref "17") (pin "1") (pinfunction "1_1") (pintype "passive"))
      (node (ref "18") (pin "1") (pinfunction "1_1") (pintype "passive"))
      (node (ref "19") (pin "1") (pinfunction "1_1") (pintype "passive"))
      (node (ref "2") (pin "1") (pinfunction "1_1") (pintype "passive"))
      (node (ref "20") (pin "1") (pinfunction "1_1") (pintype "passive"))
      (node (ref "21") (pin "1") (pinfunction "1_1") (pintype "passive"))
      (node (ref "22") (pin "1") (pinfunction "1_1") (pintype "passive"))
      (node (ref "23") (pin "1") (pinfunction "1_1") (pintype "passive"))
      (node (ref "24") (pin "1") (pinfunction "1_1") (pintype "passive"))
      (node (ref "25") (pin "1") (pinfunction "1_1") (pintype "passive"))
      (node (ref "26") (pin "1") (pinfunction "1_1") (pintype "passive"))
      (node (ref "27") (pin "1") (pinfunction "1_1") (pintype "passive"))
      (node (ref "28") (pin "1") (pinfunction "1_1") (pintype "passive"))
      (node (ref "29") (pin "1") (pinfunction "1_1") (pintype "passive"))
      (node (ref "3") (pin "1") (pinfunction "1_1") (pintype "passive"))
      (node (ref "4") (pin "1") (pinfunction "1_1") (pintype "passive"))
      (node (ref "5") (pin "1") (pinfunction "1_1") (pintype "passive"))
      (node (ref "6") (pin "1") (pinfunction "1_1") (pintype "passive"))
      (node (ref "7") (pin "1") (pinfunction "1_1") (pintype "passive"))
      (node (ref "9") (pin "1") (pinfunction "1_1") (pintype "passive"))
      (node (ref "C1") (pin "1") (pinfunction "1_1") (pintype "passive"))
      (node (ref "C10") (pin "1") (pinfunction "1_1") (pintype "passive"))
      (node (ref "C11") (pin "1") (pinfunction "1_1") (pintype "passive"))
      (node (ref "C12") (pin "1") (pinfunction "1_1") (pintype "passive"))
      (node (ref "C13") (pin "1") (pinfunction "1_1") (pintype "passive"))
      (node (ref "C14") (pin "1") (pinfunction "1_1") (pintype "passive"))
      (node (ref "C15") (pin "1") (pinfunction "1_1") (pintype "passive"))
      (node (ref "C16") (pin "1") (pinfunction "1_1") (pintype "passive"))
      (node (ref "C17") (pin "1") (pinfunction "1_1") (pintype "passive"))
      (node (ref "C18") (pin "1") (pinfunction "1_1") (pintype "passive"))
      (node (ref "C19") (pin "1") (pinfunction "1_1") (pintype "passive"))
      (node (ref "C2") (pin "1") (pinfunction "1_1") (pintype "passive"))
      (node (ref "C20") (pin "1") (pinfunction "1_1") (pintype "passive"))
      (node (ref "C21") (pin "1") (pinfunction "1_1") (pintype "passive"))
      (node (ref "C22") (pin "1") (pinfunction "1_1") (pintype "passive"))
      (node (ref "C23") (pin "1") (pinfunction "1_1") (pintype "passive"))
      (node (ref "C24") (pin "1") (pinfunction "1_1") (pintype "passive"))
      (node (ref "C25") (pin "1") (pinfunction "1_1") (pintype "passive"))
      (node (ref "C26") (pin "1") (pinfunction "1_1") (pintype "passive"))
      (node (ref "C27") (pin "1") (pinfunction "1_1") (pintype "passive"))
      (node (ref "C28") (pin "1") (pinfunction "1_1") (pintype "passive"))
      (node (ref "C29") (pin "1") (pinfunction "1_1") (pintype "passive"))
      (node (ref "C3") (pin "1") (pinfunction "1_1") (pintype "passive"))
      (node (ref "C30") (pin "1") (pinfunction "1_1") (pintype "passive"))
      (node (ref "C31") (pin "1") (pinfunction "1_1") (pintype "passive"))
      (node (ref "C32") (pin "1") (pinfunction "1_1") (pintype "passive"))
      (node (ref "C33") (pin "1") (pinfunction "1_1") (pintype "passive"))
      (node (ref "C34") (pin "1") (pinfunction "1_1") (pintype "passive"))
      (node (ref "C35") (pin "1") (pinfunction "1_1") (pintype "passive"))
      (node (ref "C36") (pin "2") (pinfunction "2_2") (pintype "passive"))
      (node (ref "C37") (pin "2") (pinfunction "2_2") (pintype "passive"))
      (node (ref "C38") (pin "1") (pinfunction "1_1") (pintype "passive"))
      (node (ref "C39") (pin "1") (pinfunction "1_1") (pintype "passive"))
      (node (ref "C4") (pin "2") (pinfunction "2_2") (pintype "passive"))
      (node (ref "C40") (pin "2") (pinfunction "2_2") (pintype "passive"))
      (node (ref "C41") (pin "2") (pinfunction "2_2") (pintype "passive"))
      (node (ref "C42") (pin "2") (pinfunction "2_2") (pintype "passive"))
      (node (ref "C43") (pin "1") (pinfunction "1_1") (pintype "passive"))
      (node (ref "C44") (pin "1") (pinfunction "1_1") (pintype "passive"))
      (node (ref "C45") (pin "1") (pinfunction "1_1") (pintype "passive"))
      (node (ref "C46") (pin "1") (pinfunction "1_1") (pintype "passive"))
      (node (ref "C47") (pin "2") (pinfunction "2_2") (pintype "passive"))
      (node (ref "C48") (pin "1") (pinfunction "1_1") (pintype "passive"))
      (node (ref "C5") (pin "2") (pinfunction "2_2") (pintype "passive"))
      (node (ref "C51") (pin "2") (pinfunction "2_2") (pintype "passive"))
      (node (ref "C6") (pin "2") (pinfunction "2_2") (pintype "passive"))
      (node (ref "C7") (pin "2") (pinfunction "2_2") (pintype "passive"))
      (node (ref "C8") (pin "2") (pinfunction "2_2") (pintype "passive"))
      (node (ref "C9") (pin "1") (pinfunction "1_1") (pintype "passive"))
      (node (ref "D2") (pin "1") (pinfunction "A_1") (pintype "passive"))
      (node (ref "D4") (pin "1") (pinfunction "A_1") (pintype "passive"))
      (node (ref "E1") (pin "2") (pinfunction "2_2") (pintype "passive"))
      (node (ref "E2") (pin "2") (pinfunction "2_2") (pintype "passive"))
      (node (ref "E3") (pin "2") (pinfunction "2_2") (pintype "passive"))
      (node (ref "IC1") (pin "1") (pinfunction "STROBE_1") (pintype "passive"))
      (node (ref "IC1") (pin "15") (pinfunction "DGND_15") (pintype "passive"))
      (node (ref "IC1") (pin "2") (pinfunction "AGND_2") (pintype "passive"))
      (node (ref "IC1") (pin "24") (pinfunction "AF-GND_24") (pintype "passive"))
      (node (ref "JP2") (pin "1") (pinfunction "1_1") (pintype "passive"))
      (node (ref "JP2") (pin "6") (pinfunction "6_6") (pintype "passive"))
      (node (ref "JP3") (pin "0") (pinfunction "0_0") (pintype "passive"))
      (node (ref "JP3") (pin "4") (pinfunction "4_4") (pintype "passive"))
      (node (ref "LED1") (pin "2") (pinfunction "K_2") (pintype "passive"))
      (node (ref "LED2") (pin "2") (pinfunction "K_2") (pintype "passive"))
      (node (ref "LED3") (pin "2") (pinfunction "K_2") (pintype "passive"))
      (node (ref "LED4") (pin "2") (pinfunction "K_2") (pintype "passive"))
      (node (ref "P1") (pin "6") (pinfunction "VSS_6") (pintype "passive"))
      (node (ref "Q1") (pin "2") (pinfunction "E_2") (pintype "passive"))
      (node (ref "R24") (pin "1") (pinfunction "1_1") (pintype "passive"))
      (node (ref "R27") (pin "1") (pinfunction "1_1") (pintype "passive"))
      (node (ref "R28") (pin "1") (pinfunction "1_1") (pintype "passive"))
      (node (ref "R32") (pin "2") (pinfunction "2_2") (pintype "passive"))
      (node (ref "R33") (pin "2") (pinfunction "2_2") (pintype "passive"))
      (node (ref "R34") (pin "1") (pinfunction "1_1") (pintype "passive"))
      (node (ref "R5") (pin "1") (pinfunction "1_1") (pintype "passive"))
      (node (ref "R50") (pin "2") (pinfunction "2_2") (pintype "passive"))
      (node (ref "R62") (pin "2") (pinfunction "2_2") (pintype "passive"))
      (node (ref "SW3") (pin "2") (pinfunction "2_2") (pintype "passive"))
      (node (ref "U1") (pin "23") (pinfunction "VSS_1_23") (pintype "power_in"))
      (node (ref "U1") (pin "35") (pinfunction "VSS_2_35") (pintype "power_in"))
      (node (ref "U1") (pin "47") (pinfunction "VSS_3_47") (pintype "power_in"))
      (node (ref "U1") (pin "8") (pinfunction "VSSA_8") (pintype "power_in"))
      (node (ref "U10") (pin "12") (pinfunction "12_12") (pintype "passive"))
      (node (ref "U10") (pin "38") (pinfunction "38_38") (pintype "passive"))
      (node (ref "U10") (pin "41") (pinfunction "41_41") (pintype "passive"))
      (node (ref "U10") (pin "42") (pinfunction "42_42") (pintype "passive"))
      (node (ref "U10") (pin "5") (pinfunction "5_5") (pintype "passive"))
      (node (ref "U11") (pin "21") (pinfunction "GND_21") (pintype "passive"))
      (node (ref "U2") (pin "A1") (pinfunction "VSS_1_A1") (pintype "power_in"))
      (node (ref "U2") (pin "A17") (pinfunction "VSS_1_A17") (pintype "power_in"))
      (node (ref "U2") (pin "B2") (pinfunction "VSS_1_B2") (pintype "power_in"))
      (node (ref "U2") (pin "B6") (pinfunction "VSS_1_B6") (pintype "power_in"))
      (node (ref "U2") (pin "C10") (pinfunction "VSS_1_C10") (pintype "power_in"))
      (node (ref "U2") (pin "C13") (pinfunction "VSS_1_C13") (pintype "power_in"))
      (node (ref "U2") (pin "C16") (pinfunction "VSS_1_C16") (pintype "power_in"))
      (node (ref "U2") (pin "F2") (pinfunction "VSS_1_F2") (pintype "power_in"))
      (node (ref "U2") (pin "G10") (pinfunction "VSS_2_G10") (pintype "power_in"))
      (node (ref "U2") (pin "G11") (pinfunction "VSS_2_G11") (pintype "power_in"))
      (node (ref "U2") (pin "G16") (pinfunction "VSS_2_G16") (pintype "power_in"))
      (node (ref "U2") (pin "G7") (pinfunction "VSS_2_G7") (pintype "power_in"))
      (node (ref "U2") (pin "G8") (pinfunction "VSS_2_G8") (pintype "power_in"))
      (node (ref "U2") (pin "G9") (pinfunction "VSS_2_G9") (pintype "power_in"))
      (node (ref "U2") (pin "H10") (pinfunction "VSS_2_H10") (pintype "power_in"))
      (node (ref "U2") (pin "H11") (pinfunction "VSS_3_H11") (pintype "power_in"))
      (node (ref "U2") (pin "H7") (pinfunction "VSS_2_H7") (pintype "power_in"))
      (node (ref "U2") (pin "H8") (pinfunction "VSS_2_H8") (pintype "power_in"))
      (node (ref "U2") (pin "H9") (pinfunction "VSS_2_H9") (pintype "power_in"))
      (node (ref "U2") (pin "J10") (pinfunction "VSS_3_J10") (pintype "power_in"))
      (node (ref "U2") (pin "J11") (pinfunction "VSS_3_J11") (pintype "power_in"))
      (node (ref "U2") (pin "J16") (pinfunction "VSS_1_J16") (pintype "power_in"))
      (node (ref "U2") (pin "J17") (pinfunction "VSS_1_J17") (pintype "power_in"))
      (node (ref "U2") (pin "J3") (pinfunction "VSS_1_J3") (pintype "power_in"))
      (node (ref "U2") (pin "J7") (pinfunction "VSS_3_J7") (pintype "power_in"))
      (node (ref "U2") (pin "J8") (pinfunction "VSS_3_J8") (pintype "power_in"))
      (node (ref "U2") (pin "J9") (pinfunction "VSS_3_J9") (pintype "power_in"))
      (node (ref "U2") (pin "K10") (pinfunction "VSS_3_K10") (pintype "power_in"))
      (node (ref "U2") (pin "K11") (pinfunction "VSS_3_K11") (pintype "power_in"))
      (node (ref "U2") (pin "K15") (pinfunction "VSS_2_K15") (pintype "power_in"))
      (node (ref "U2") (pin "K7") (pinfunction "VSS_3_K7") (pintype "power_in"))
      (node (ref "U2") (pin "K8") (pinfunction "VSS_3_K8") (pintype "power_in"))
      (node (ref "U2") (pin "K9") (pinfunction "VSS_3_K9") (pintype "power_in"))
      (node (ref "U2") (pin "L10") (pinfunction "VSS_3_L10") (pintype "power_in"))
      (node (ref "U2") (pin "L11") (pinfunction "VSS_3_L11") (pintype "power_in"))
      (node (ref "U2") (pin "L15") (pinfunction "VSS_2_L15") (pintype "power_in"))
      (node (ref "U2") (pin "L7") (pinfunction "VSS_3_L7") (pintype "power_in"))
      (node (ref "U2") (pin "L8") (pinfunction "VSS_3_L8") (pintype "power_in"))
      (node (ref "U2") (pin "L9") (pinfunction "VSS_3_L9") (pintype "power_in"))
      (node (ref "U2") (pin "M15") (pinfunction "VSS_2_M15") (pintype "power_in"))
      (node (ref "U2") (pin "N1") (pinfunction "VREF-_N1") (pintype "input"))
      (node (ref "U2") (pin "N16") (pinfunction "VSS_1_N16") (pintype "power_in"))
      (node (ref "U2") (pin "P1") (pinfunction "VSSA_P1") (pintype "power_in"))
      (node (ref "U2") (pin "R4") (pinfunction "VSS_1_R4") (pintype "power_in"))
      (node (ref "U2") (pin "R8") (pinfunction "VSS_2_R8") (pintype "power_in"))
      (node (ref "U2") (pin "T12") (pinfunction "VSS_1_T12") (pintype "power_in"))
      (node (ref "U2") (pin "U1") (pinfunction "VSS_2_U1") (pintype "power_in"))
      (node (ref "U2") (pin "U17") (pinfunction "VSS_1_U17") (pintype "power_in"))
      (node (ref "U3") (pin "A3") (pinfunction "VSS_A3") (pintype "power_in"))
      (node (ref "U3") (pin "B3") (pinfunction "VSSQ_B3") (pintype "power_in"))
      (node (ref "U3") (pin "B8") (pinfunction "VSSQ_B8") (pintype "power_in"))
      (node (ref "U3") (pin "C1") (pinfunction "VSSQ_C1") (pintype "power_in"))
      (node (ref "U3") (pin "D1") (pinfunction "VSSQ_D1") (pintype "power_in"))
      (node (ref "U3") (pin "E9") (pinfunction "VSSQ_E9") (pintype "power_in"))
      (node (ref "U3") (pin "F1") (pinfunction "VSS_F1") (pintype "power_in"))
      (node (ref "U3") (pin "L3") (pinfunction "VSS_L3") (pintype "power_in"))
      (node (ref "U3") (pin "L9") (pinfunction "VSSQ_L9") (pintype "power_in"))
      (node (ref "U3") (pin "M1") (pinfunction "VSSQ_M1") (pintype "power_in"))
      (node (ref "U3") (pin "N1") (pinfunction "VSSQ_N1") (pintype "power_in"))
      (node (ref "U3") (pin "P3") (pinfunction "VSSQ_P3") (pintype "power_in"))
      (node (ref "U3") (pin "P8") (pinfunction "VSSQ_P8") (pintype "power_in"))
      (node (ref "U3") (pin "R3") (pinfunction "VSS_R3") (pintype "power_in"))
      (node (ref "U4") (pin "13") (pinfunction "13_13") (pintype "passive"))
      (node (ref "U4") (pin "14") (pinfunction "14_14") (pintype "passive"))
      (node (ref "U4") (pin "15") (pinfunction "15_15") (pintype "passive"))
      (node (ref "U4") (pin "16") (pinfunction "16_16") (pintype "passive"))
      (node (ref "U4") (pin "A1B12") (pinfunction "GND_A1B12") (pintype "passive"))
      (node (ref "U4") (pin "B1A12") (pinfunction "GND_B1A12") (pintype "passive"))
      (node (ref "U5") (pin "13") (pinfunction "13_13") (pintype "passive"))
      (node (ref "U5") (pin "14") (pinfunction "14_14") (pintype "passive"))
      (node (ref "U5") (pin "15") (pinfunction "15_15") (pintype "passive"))
      (node (ref "U5") (pin "16") (pinfunction "16_16") (pintype "passive"))
      (node (ref "U5") (pin "A1B12") (pinfunction "GND_A1B12") (pintype "passive"))
      (node (ref "U5") (pin "B1A12") (pinfunction "GND_B1A12") (pintype "passive"))
      (node (ref "U6") (pin "4") (pinfunction "GND_4") (pintype "passive"))
      (node (ref "U6") (pin "9") (pinfunction "EP_9") (pintype "passive"))
      (node (ref "U7") (pin "1") (pinfunction "VSS_1") (pintype "passive"))
      (node (ref "U8") (pin "1") (pinfunction "VSS_1") (pintype "passive"))
      (node (ref "U9") (pin "1") (pinfunction "VSS_1") (pintype "passive"))
      (node (ref "X2") (pin "2") (pinfunction "2_2") (pintype "passive"))
      (node (ref "X2") (pin "4") (pinfunction "4_4") (pintype "passive"))
      (node (ref "X4") (pin "2") (pinfunction "GND_2") (pintype "passive"))
    )
    (net (code "163") (name "Net-(8-FB)") (class "Default")
      (node (ref "8") (pin "3") (pinfunction "FB_3") (pintype "bidirectional"))
      (node (ref "R29") (pin "2") (pinfunction "2_2") (pintype "passive"))
    )
    (net (code "164") (name "Net-(8-GND)") (class "Default")
      (node (ref "8") (pin "2") (pinfunction "GND_2") (pintype "bidirectional"))
      (node (ref "R28") (pin "2") (pinfunction "2_2") (pintype "passive"))
    )
    (net (code "165") (name "Net-(8-SW)") (class "Default")
      (node (ref "8") (pin "1") (pinfunction "SW_1") (pintype "bidirectional"))
      (node (ref "D1") (pin "1") (pinfunction "A_1") (pintype "passive"))
      (node (ref "L1") (pin "1") (pinfunction "1_1") (pintype "passive"))
    )
    (net (code "166") (name "Net-(8-~{SHTDN!})") (class "Default")
      (node (ref "13") (pin "2") (pinfunction "2_2") (pintype "passive"))
      (node (ref "8") (pin "4") (pinfunction "~{SHTDN!}_4") (pintype "bidirectional"))
      (node (ref "R30") (pin "1") (pinfunction "1_1") (pintype "passive"))
      (node (ref "R32") (pin "1") (pinfunction "1_1") (pintype "passive"))
    )
    (net (code "167") (name "Net-(28-Pad2)") (class "Default")
      (node (ref "28") (pin "2") (pinfunction "2_2") (pintype "passive"))
      (node (ref "JP3") (pin "2") (pinfunction "2_2") (pintype "passive"))
      (node (ref "R45") (pin "2") (pinfunction "2_2") (pintype "passive"))
      (node (ref "R48") (pin "1") (pinfunction "1_1") (pintype "passive"))
    )
    (net (code "168") (name "Net-(29-Pad2)") (class "Default")
      (node (ref "29") (pin "2") (pinfunction "2_2") (pintype "passive"))
      (node (ref "JP3") (pin "1") (pinfunction "1_1") (pintype "passive"))
      (node (ref "R44") (pin "2") (pinfunction "2_2") (pintype "passive"))
      (node (ref "R58") (pin "1") (pinfunction "1_1") (pintype "passive"))
    )
    (net (code "169") (name "Net-(C1-Pad2)") (class "Default")
      (node (ref "C1") (pin "2") (pinfunction "2_2") (pintype "passive"))
      (node (ref "U2") (pin "A7") (pinfunction "VCAP_A7") (pintype "power_in"))
    )
    (net (code "170") (name "Net-(C2-Pad2)") (class "Default")
      (node (ref "C2") (pin "2") (pinfunction "2_2") (pintype "passive"))
      (node (ref "U2") (pin "D17") (pinfunction "VCAP_D17") (pintype "power_in"))
    )
    (net (code "171") (name "Net-(C3-Pad2)") (class "Default")
      (node (ref "C3") (pin "2") (pinfunction "2_2") (pintype "passive"))
      (node (ref "U2") (pin "U11") (pinfunction "VCAP_U11") (pintype "power_in"))
    )
    (net (code "172") (name "Net-(D3-A)") (class "Default")
      (node (ref "D3") (pin "1") (pinfunction "A_1") (pintype "passive"))
      (node (ref "R26") (pin "1") (pinfunction "1_1") (pintype "passive"))
      (node (ref "SW2") (pin "2") (pinfunction "2_2") (pintype "passive"))
    )
    (net (code "173") (name "Net-(D3-K)") (class "Default")
      (node (ref "C42") (pin "1") (pinfunction "1_1") (pintype "passive"))
      (node (ref "D3") (pin "2") (pinfunction "K_2") (pintype "passive"))
      (node (ref "Q2") (pin "1") (pinfunction "B_1") (pintype "passive"))
    )
    (net (code "174") (name "Net-(IC1-DOVDD)") (class "Default")
      (node (ref "21") (pin "2") (pinfunction "2_2") (pintype "passive"))
      (node (ref "22") (pin "2") (pinfunction "2_2") (pintype "passive"))
      (node (ref "FB6") (pin "2") (pinfunction "2_2") (pintype "passive"))
      (node (ref "IC1") (pin "11") (pinfunction "DOVDD_11") (pintype "passive"))
    )
    (net (code "175") (name "Net-(IC1-RESET)") (class "Default")
      (node (ref "24") (pin "2") (pinfunction "2_2") (pintype "passive"))
      (node (ref "IC1") (pin "6") (pinfunction "RESET_6") (pintype "passive"))
      (node (ref "R38") (pin "2") (pinfunction "2_2") (pintype "passive"))
    )
    (net (code "176") (name "Net-(IC1-SCL)") (class "Default")
      (node (ref "25") (pin "2") (pinfunction "2_2") (pintype "passive"))
      (node (ref "IC1") (pin "5") (pinfunction "SCL_5") (pintype "passive"))
      (node (ref "R40") (pin "1") (pinfunction "1_1") (pintype "passive"))
      (node (ref "R42") (pin "1") (pinfunction "1_1") (pintype "passive"))
    )
    (net (code "177") (name "Net-(IC1-SDA)") (class "Default")
      (node (ref "26") (pin "2") (pinfunction "2_2") (pintype "passive"))
      (node (ref "IC1") (pin "3") (pinfunction "SDA_3") (pintype "passive"))
      (node (ref "R41") (pin "1") (pinfunction "1_1") (pintype "passive"))
      (node (ref "R43") (pin "1") (pinfunction "1_1") (pintype "passive"))
    )
    (net (code "178") (name "Net-(IC1-XVCLK)") (class "Default")
      (node (ref "IC1") (pin "13") (pinfunction "XVCLK_13") (pintype "passive"))
      (node (ref "X4") (pin "3") (pinfunction "OUT_3") (pintype "passive"))
    )
    (net (code "179") (name "Net-(JP1-Pad1)") (class "Default")
      (node (ref "JP1") (pin "1") (pinfunction "1_1") (pintype "passive"))
      (node (ref "R13") (pin "2") (pinfunction "2_2") (pintype "passive"))
      (node (ref "R7") (pin "1") (pinfunction "1_1") (pintype "passive"))
    )
    (net (code "180") (name "Net-(JP1-Pad3)") (class "Default")
      (node (ref "JP1") (pin "3") (pinfunction "3_3") (pintype "passive"))
      (node (ref "R16") (pin "2") (pinfunction "2_2") (pintype "passive"))
      (node (ref "R8") (pin "1") (pinfunction "1_1") (pintype "passive"))
    )
    (net (code "181") (name "Net-(JP3-Pad3)") (class "Default")
      (node (ref "JP3") (pin "3") (pinfunction "3_3") (pintype "passive"))
      (node (ref "R46") (pin "2") (pinfunction "2_2") (pintype "passive"))
    )
    (net (code "182") (name "Net-(JP3-Pad6)") (class "Default")
      (node (ref "JP3") (pin "6") (pinfunction "6_6") (pintype "passive"))
      (node (ref "R47") (pin "2") (pinfunction "2_2") (pintype "passive"))
    )
    (net (code "183") (name "Net-(LED1-A)") (class "Default")
      (node (ref "LED1") (pin "1") (pinfunction "A_1") (pintype "passive"))
      (node (ref "R2") (pin "2") (pinfunction "2_2") (pintype "passive"))
    )
    (net (code "184") (name "Net-(LED2-A)") (class "Default")
      (node (ref "LED2") (pin "1") (pinfunction "A_1") (pintype "passive"))
      (node (ref "R6") (pin "2") (pinfunction "2_2") (pintype "passive"))
    )
    (net (code "185") (name "Net-(LED4-A)") (class "Default")
      (node (ref "LED4") (pin "1") (pinfunction "A_1") (pintype "passive"))
      (node (ref "R35") (pin "2") (pinfunction "2_2") (pintype "passive"))
    )
    (net (code "186") (name "Net-(LED5-A)") (class "Default")
      (node (ref "LED5") (pin "1") (pinfunction "A_1") (pintype "passive"))
      (node (ref "R37") (pin "2") (pinfunction "2_2") (pintype "passive"))
    )
    (net (code "187") (name "Net-(Q1-B)") (class "Default")
      (node (ref "C37") (pin "1") (pinfunction "1_1") (pintype "passive"))
      (node (ref "Q1") (pin "1") (pinfunction "B_1") (pintype "passive"))
      (node (ref "R26") (pin "2") (pinfunction "2_2") (pintype "passive"))
      (node (ref "R27") (pin "2") (pinfunction "2_2") (pintype "passive"))
    )
    (net (code "188") (name "Net-(Q2-C)") (class "Default")
      (node (ref "Q2") (pin "3") (pinfunction "C_3") (pintype "passive"))
      (node (ref "R31") (pin "1") (pinfunction "1_1") (pintype "passive"))
    )
    (net (code "189") (name "Net-(RP1-Pad5)") (class "Default")
      (node (ref "RP1") (pin "5") (pintype "passive"))
      (node (ref "U10") (pin "33") (pinfunction "33_33") (pintype "passive"))
    )
    (net (code "190") (name "Net-(RP1-Pad6)") (class "Default")
      (node (ref "RP1") (pin "6") (pintype "passive"))
      (node (ref "U10") (pin "34") (pinfunction "34_34") (pintype "passive"))
    )
    (net (code "191") (name "Net-(RP1-Pad7)") (class "Default")
      (node (ref "RP1") (pin "7") (pintype "passive"))
      (node (ref "U10") (pin "35") (pinfunction "35_35") (pintype "passive"))
    )
    (net (code "192") (name "Net-(RP1-Pad8)") (class "Default")
      (node (ref "RP1") (pin "8") (pintype "passive"))
      (node (ref "U10") (pin "36") (pinfunction "36_36") (pintype "passive"))
    )
    (net (code "193") (name "Net-(RP2-Pad5)") (class "Default")
      (node (ref "RP2") (pin "5") (pintype "passive"))
      (node (ref "U10") (pin "29") (pinfunction "29_29") (pintype "passive"))
    )
    (net (code "194") (name "Net-(RP2-Pad6)") (class "Default")
      (node (ref "RP2") (pin "6") (pintype "passive"))
      (node (ref "U10") (pin "30") (pinfunction "30_30") (pintype "passive"))
    )
    (net (code "195") (name "Net-(RP2-Pad7)") (class "Default")
      (node (ref "RP2") (pin "7") (pintype "passive"))
      (node (ref "U10") (pin "31") (pinfunction "31_31") (pintype "passive"))
    )
    (net (code "196") (name "Net-(RP2-Pad8)") (class "Default")
      (node (ref "RP2") (pin "8") (pintype "passive"))
      (node (ref "U10") (pin "32") (pinfunction "32_32") (pintype "passive"))
    )
    (net (code "197") (name "Net-(RP3-Pad5)") (class "Default")
      (node (ref "RP3") (pin "5") (pintype "passive"))
      (node (ref "U10") (pin "25") (pinfunction "25_25") (pintype "passive"))
    )
    (net (code "198") (name "Net-(RP3-Pad6)") (class "Default")
      (node (ref "RP3") (pin "6") (pintype "passive"))
      (node (ref "U10") (pin "26") (pinfunction "26_26") (pintype "passive"))
    )
    (net (code "199") (name "Net-(RP3-Pad7)") (class "Default")
      (node (ref "RP3") (pin "7") (pintype "passive"))
      (node (ref "U10") (pin "27") (pinfunction "27_27") (pintype "passive"))
    )
    (net (code "200") (name "Net-(RP3-Pad8)") (class "Default")
      (node (ref "RP3") (pin "8") (pintype "passive"))
      (node (ref "U10") (pin "28") (pinfunction "28_28") (pintype "passive"))
    )
    (net (code "201") (name "Net-(RP4-Pad5)") (class "Default")
      (node (ref "RP4") (pin "5") (pintype "passive"))
      (node (ref "U10") (pin "21") (pinfunction "21_21") (pintype "passive"))
    )
    (net (code "202") (name "Net-(RP4-Pad6)") (class "Default")
      (node (ref "RP4") (pin "6") (pintype "passive"))
      (node (ref "U10") (pin "22") (pinfunction "22_22") (pintype "passive"))
    )
    (net (code "203") (name "Net-(RP4-Pad7)") (class "Default")
      (node (ref "RP4") (pin "7") (pintype "passive"))
      (node (ref "U10") (pin "23") (pinfunction "23_23") (pintype "passive"))
    )
    (net (code "204") (name "Net-(RP4-Pad8)") (class "Default")
      (node (ref "RP4") (pin "8") (pintype "passive"))
      (node (ref "U10") (pin "24") (pinfunction "24_24") (pintype "passive"))
    )
    (net (code "205") (name "Net-(RP5-Pad5)") (class "Default")
      (node (ref "RP5") (pin "5") (pintype "passive"))
      (node (ref "U10") (pin "17") (pinfunction "17_17") (pintype "passive"))
    )
    (net (code "206") (name "Net-(RP5-Pad6)") (class "Default")
      (node (ref "RP5") (pin "6") (pintype "passive"))
      (node (ref "U10") (pin "18") (pinfunction "18_18") (pintype "passive"))
    )
    (net (code "207") (name "Net-(RP5-Pad7)") (class "Default")
      (node (ref "RP5") (pin "7") (pintype "passive"))
      (node (ref "U10") (pin "19") (pinfunction "19_19") (pintype "passive"))
    )
    (net (code "208") (name "Net-(RP5-Pad8)") (class "Default")
      (node (ref "RP5") (pin "8") (pintype "passive"))
      (node (ref "U10") (pin "20") (pinfunction "20_20") (pintype "passive"))
    )
    (net (code "209") (name "Net-(RP6-Pad5)") (class "Default")
      (node (ref "RP6") (pin "5") (pintype "passive"))
      (node (ref "U10") (pin "13") (pinfunction "13_13") (pintype "passive"))
    )
    (net (code "210") (name "Net-(RP6-Pad6)") (class "Default")
      (node (ref "RP6") (pin "6") (pintype "passive"))
      (node (ref "U10") (pin "14") (pinfunction "14_14") (pintype "passive"))
    )
    (net (code "211") (name "Net-(RP6-Pad7)") (class "Default")
      (node (ref "RP6") (pin "7") (pintype "passive"))
      (node (ref "U10") (pin "15") (pinfunction "15_15") (pintype "passive"))
    )
    (net (code "212") (name "Net-(RP6-Pad8)") (class "Default")
      (node (ref "RP6") (pin "8") (pintype "passive"))
      (node (ref "U10") (pin "16") (pinfunction "16_16") (pintype "passive"))
    )
    (net (code "213") (name "Net-(RP7-Pad5)") (class "Default")
      (node (ref "RP7") (pin "5") (pintype "passive"))
      (node (ref "U10") (pin "7") (pinfunction "7_7") (pintype "passive"))
    )
    (net (code "214") (name "Net-(RP7-Pad6)") (class "Default")
      (node (ref "RP7") (pin "6") (pintype "passive"))
      (node (ref "U10") (pin "8") (pinfunction "8_8") (pintype "passive"))
    )
    (net (code "215") (name "Net-(RP7-Pad7)") (class "Default")
      (node (ref "RP7") (pin "7") (pintype "passive"))
      (node (ref "U10") (pin "9") (pinfunction "9_9") (pintype "passive"))
    )
    (net (code "216") (name "Net-(RP7-Pad8)") (class "Default")
      (node (ref "RP7") (pin "8") (pintype "passive"))
      (node (ref "U10") (pin "11") (pinfunction "11_11") (pintype "passive"))
    )
    (net (code "217") (name "Net-(U1A-PD0-OSC_IN)") (class "Default")
      (node (ref "C4") (pin "1") (pinfunction "1_1") (pintype "passive"))
      (node (ref "U1") (pin "5") (pinfunction "PD0-OSC_IN_5") (pintype "bidirectional"))
      (node (ref "X1") (pin "1") (pinfunction "1_1") (pintype "passive"))
    )
    (net (code "218") (name "Net-(U1A-PD1)") (class "Default")
      (node (ref "C5") (pin "1") (pinfunction "1_1") (pintype "passive"))
      (node (ref "U1") (pin "6") (pinfunction "PD1_6") (pintype "bidirectional"))
      (node (ref "X1") (pin "2") (pinfunction "2_2") (pintype "passive"))
    )
    (net (code "219") (name "Net-(U2A-PDR_ON)") (class "Default")
      (node (ref "R1") (pin "2") (pinfunction "2_2") (pintype "passive"))
      (node (ref "U2") (pin "E7") (pinfunction "PDR_ON_E7") (pintype "input"))
    )
    (net (code "220") (name "Net-(U4-DN1)") (class "Default")
      (node (ref "R14") (pin "2") (pinfunction "2_2") (pintype "passive"))
      (node (ref "U4") (pin "A7") (pinfunction "DN1_A7") (pintype "passive"))
      (node (ref "U4") (pin "B7") (pinfunction "DN2_B7") (pintype "passive"))
    )
    (net (code "221") (name "Net-(U4-DP1)") (class "Default")
      (node (ref "R17") (pin "2") (pinfunction "2_2") (pintype "passive"))
      (node (ref "U4") (pin "A6") (pinfunction "DP1_A6") (pintype "passive"))
      (node (ref "U4") (pin "B6") (pinfunction "DP2_B6") (pintype "passive"))
    )
    (net (code "222") (name "Net-(U7-VIN)") (class "Default")
      (node (ref "1") (pin "2") (pinfunction "2_2") (pintype "passive"))
      (node (ref "2") (pin "2") (pinfunction "2_2") (pintype "passive"))
      (node (ref "FB1") (pin "1") (pinfunction "1_1") (pintype "passive"))
      (node (ref "U7") (pin "3") (pinfunction "VIN_3") (pintype "passive"))
    )
    (net (code "223") (name "Net-(U8-VIN)") (class "Default")
      (node (ref "11") (pin "2") (pinfunction "2_2") (pintype "passive"))
      (node (ref "12") (pin "2") (pinfunction "2_2") (pintype "passive"))
      (node (ref "FB2") (pin "1") (pinfunction "1_1") (pintype "passive"))
      (node (ref "U8") (pin "3") (pinfunction "VIN_3") (pintype "passive"))
    )
    (net (code "224") (name "Net-(U9-VIN)") (class "Default")
      (node (ref "16") (pin "2") (pinfunction "2_2") (pintype "passive"))
      (node (ref "17") (pin "2") (pinfunction "2_2") (pintype "passive"))
      (node (ref "FB3") (pin "1") (pinfunction "1_1") (pintype "passive"))
      (node (ref "U9") (pin "3") (pinfunction "VIN_3") (pintype "passive"))
    )
    (net (code "225") (name "Net-(U11-FB2)") (class "Default")
      (node (ref "C50") (pin "1") (pinfunction "1_1") (pintype "passive"))
      (node (ref "R50") (pin "1") (pinfunction "1_1") (pintype "passive"))
      (node (ref "R61") (pin "2") (pinfunction "2_2") (pintype "passive"))
      (node (ref "U11") (pin "3") (pinfunction "FB2_3") (pintype "passive"))
    )
    (net (code "226") (name "Net-(U11-FB3)") (class "Default")
      (node (ref "C49") (pin "1") (pinfunction "1_1") (pintype "passive"))
      (node (ref "R59") (pin "2") (pinfunction "2_2") (pintype "passive"))
      (node (ref "R62") (pin "1") (pinfunction "1_1") (pintype "passive"))
      (node (ref "U11") (pin "2") (pinfunction "FB3_2") (pintype "passive"))
    )
    (net (code "227") (name "Net-(U11-SW2)") (class "Default")
      (node (ref "L3") (pin "2") (pinfunction "2_2") (pintype "passive"))
      (node (ref "U11") (pin "6") (pinfunction "SW2_6") (pintype "passive"))
    )
    (net (code "228") (name "Net-(U11-SW3)") (class "Default")
      (node (ref "L2") (pin "2") (pinfunction "2_2") (pintype "passive"))
      (node (ref "U11") (pin "20") (pinfunction "SW3_20") (pintype "passive"))
    )
    (net (code "229") (name "Net-(X4-EN{slash}NC)") (class "Default")
      (node (ref "R49") (pin "1") (pinfunction "1_1") (pintype "passive"))
      (node (ref "X4") (pin "1") (pinfunction "EN/NC_1") (pintype "passive"))
    )
    (net (code "230") (name "Net-(X4-VCC)") (class "Default")
      (node (ref "27") (pin "2") (pinfunction "2_2") (pintype "passive"))
      (node (ref "FB7") (pin "2") (pinfunction "2_2") (pintype "passive"))
      (node (ref "X4") (pin "4") (pinfunction "VCC_4") (pintype "passive"))
    )
    (net (code "231") (name "unconnected-(U1A-PA0-WKUP-Pad10)") (class "Default")
      (node (ref "U1") (pin "10") (pinfunction "PA0-WKUP_10") (pintype "bidirectional+no_connect"))
    )
    (net (code "232") (name "unconnected-(U1A-PA1-Pad11)") (class "Default")
      (node (ref "U1") (pin "11") (pinfunction "PA1_11") (pintype "bidirectional+no_connect"))
    )
    (net (code "233") (name "unconnected-(U1A-PA3-Pad13)") (class "Default")
      (node (ref "U1") (pin "13") (pinfunction "PA3_13") (pintype "bidirectional+no_connect"))
    )
    (net (code "234") (name "unconnected-(U1A-PA5-Pad15)") (class "Default")
      (node (ref "U1") (pin "15") (pinfunction "PA5_15") (pintype "bidirectional+no_connect"))
    )
    (net (code "235") (name "unconnected-(U1A-PA7-Pad17)") (class "Default")
      (node (ref "U1") (pin "17") (pinfunction "PA7_17") (pintype "bidirectional+no_connect"))
    )
    (net (code "236") (name "unconnected-(U1A-PA8-Pad29)") (class "Default")
      (node (ref "U1") (pin "29") (pinfunction "PA8_29") (pintype "bidirectional+no_connect"))
    )
    (net (code "237") (name "unconnected-(U1A-PA13-Pad34)") (class "Default")
      (node (ref "U1") (pin "34") (pinfunction "PA13_34") (pintype "bidirectional+no_connect"))
    )
    (net (code "238") (name "unconnected-(U1A-PA14-Pad37)") (class "Default")
      (node (ref "U1") (pin "37") (pinfunction "PA14_37") (pintype "bidirectional+no_connect"))
    )
    (net (code "239") (name "unconnected-(U1A-PA15-Pad38)") (class "Default")
      (node (ref "U1") (pin "38") (pinfunction "PA15_38") (pintype "bidirectional+no_connect"))
    )
    (net (code "240") (name "unconnected-(U1A-PB0-Pad18)") (class "Default")
      (node (ref "U1") (pin "18") (pinfunction "PB0_18") (pintype "bidirectional+no_connect"))
    )
    (net (code "241") (name "unconnected-(U1A-PB1-Pad19)") (class "Default")
      (node (ref "U1") (pin "19") (pinfunction "PB1_19") (pintype "bidirectional+no_connect"))
    )
    (net (code "242") (name "unconnected-(U1A-PB2-Pad20)") (class "Default")
      (node (ref "U1") (pin "20") (pinfunction "PB2_20") (pintype "bidirectional+no_connect"))
    )
    (net (code "243") (name "unconnected-(U1A-PB3-Pad39)") (class "Default")
      (node (ref "U1") (pin "39") (pinfunction "PB3_39") (pintype "bidirectional+no_connect"))
    )
    (net (code "244") (name "unconnected-(U1A-PB4-Pad40)") (class "Default")
      (node (ref "U1") (pin "40") (pinfunction "PB4_40") (pintype "bidirectional+no_connect"))
    )
    (net (code "245") (name "unconnected-(U1A-PB5-Pad41)") (class "Default")
      (node (ref "U1") (pin "41") (pinfunction "PB5_41") (pintype "bidirectional+no_connect"))
    )
    (net (code "246") (name "unconnected-(U1A-PB6-Pad42)") (class "Default")
      (node (ref "U1") (pin "42") (pinfunction "PB6_42") (pintype "bidirectional+no_connect"))
    )
    (net (code "247") (name "unconnected-(U1A-PB7-Pad43)") (class "Default")
      (node (ref "U1") (pin "43") (pinfunction "PB7_43") (pintype "bidirectional+no_connect"))
    )
    (net (code "248") (name "unconnected-(U1A-PB9-Pad46)") (class "Default")
      (node (ref "U1") (pin "46") (pinfunction "PB9_46") (pintype "bidirectional+no_connect"))
    )
    (net (code "249") (name "unconnected-(U1A-PB10-Pad21)") (class "Default")
      (node (ref "U1") (pin "21") (pinfunction "PB10_21") (pintype "bidirectional+no_connect"))
    )
    (net (code "250") (name "unconnected-(U1A-PB11-Pad22)") (class "Default")
      (node (ref "U1") (pin "22") (pinfunction "PB11_22") (pintype "bidirectional+no_connect"))
    )
    (net (code "251") (name "unconnected-(U1A-PB13-Pad26)") (class "Default")
      (node (ref "U1") (pin "26") (pinfunction "PB13_26") (pintype "bidirectional+no_connect"))
    )
    (net (code "252") (name "unconnected-(U1A-PB14-Pad27)") (class "Default")
      (node (ref "U1") (pin "27") (pinfunction "PB14_27") (pintype "bidirectional+no_connect"))
    )
    (net (code "253") (name "unconnected-(U1A-PB15-Pad28)") (class "Default")
      (node (ref "U1") (pin "28") (pinfunction "PB15_28") (pintype "bidirectional+no_connect"))
    )
    (net (code "254") (name "unconnected-(U1A-PC13-TAMPER-RTC-Pad2)") (class "Default")
      (node (ref "U1") (pin "2") (pinfunction "PC13-TAMPER-RTC_2") (pintype "bidirectional+no_connect"))
    )
    (net (code "255") (name "unconnected-(U1A-PC14-OSC32_IN-Pad3)") (class "Default")
      (node (ref "U1") (pin "3") (pinfunction "PC14-OSC32_IN_3") (pintype "bidirectional+no_connect"))
    )
    (net (code "256") (name "unconnected-(U1A-PC15-OSC32_OUT-Pad4)") (class "Default")
      (node (ref "U1") (pin "4") (pinfunction "PC15-OSC32_OUT_4") (pintype "bidirectional+no_connect"))
    )
    (net (code "257") (name "unconnected-(U2A-PA0_C{slash}TIM2_CH1{slash}TIM2_ETR{slash}TIM5_CH1{slash}TIM8_ETR{slash}TIM15_BKIN{slash}USART2_CTS{slash}USART2_NSS{slash}UART4_TX{slash}SDMMC2_CMD{slash}SAI2_SD_B{slash}ETH_MII_CRS{slash}EVENTOUT-PadT1)") (class "Default")
      (node (ref "U2") (pin "T1") (pinfunction "PA0_C/TIM2_CH1/TIM2_ETR/TIM5_CH1/TIM8_ETR/TIM15_BKIN/USART2_CTS/USART2_NSS/UART4_TX/SDMMC2_CMD/SAI2_SD_B/ETH_MII_CRS/EVENTOUT_T1") (pintype "bidirectional+no_connect"))
    )
    (net (code "258") (name "unconnected-(U2A-PA0{slash}TIM2_CH1{slash}TIM2_ETR{slash}TIM5_CH1{slash}TIM8_ETR{slash}TIM15_BKIN{slash}USART2_CTS{slash}USART2_NSS{slash}UART4_TX{slash}SDMMC2_CMD{slash}SAI2_SD_B{slash}ETH_MII_CRS{slash}EVENTOUT-PadN5)") (class "Default")
      (node (ref "U2") (pin "N5") (pinfunction "PA0/TIM2_CH1/TIM2_ETR/TIM5_CH1/TIM8_ETR/TIM15_BKIN/USART2_CTS/USART2_NSS/UART4_TX/SDMMC2_CMD/SAI2_SD_B/ETH_MII_CRS/EVENTOUT_N5") (pintype "bidirectional+no_connect"))
    )
    (net (code "259") (name "unconnected-(U2A-PA1_C{slash}TIM2_CH2{slash}TIM5_CH2{slash}LPTIM3_OUT{slash}TIM15_CH1N{slash}USART2_RTS{slash}USART2_DE{slash}UART4_RX{slash}QUADSPI_BK1_IO3{slash}SAI2_MCLK_B{slash}ETH_MII_RX_CLK{slash}ETH_RMII_REF_CLK{slash}LCD_R2{slash}EVENTOUT-PadT2)") (class "Default")
      (node (ref "U2") (pin "T2") (pinfunction "PA1_C/TIM2_CH2/TIM5_CH2/LPTIM3_OUT/TIM15_CH1N/USART2_RTS/USART2_DE/UART4_RX/QUADSPI_BK1_IO3/SAI2_MCLK_B/ETH_MII_RX_CLK/ETH_RMII_REF_CLK/LCD_R2/EVENTOUT_T2") (pintype "bidirectional+no_connect"))
    )
    (net (code "260") (name "unconnected-(U2A-PA1{slash}TIM2_CH2{slash}TIM5_CH2{slash}LPTIM3_OUT{slash}TIM15_CH1N{slash}USART2_RTS{slash}USART2_DE{slash}UART4_RX{slash}QUADSPI_BK1_IO3{slash}SAI2_MCLK_B{slash}ETH_MII_RX_CLK{slash}ETH_RMII_REF_CLK{slash}LCD_R2{slash}EVENTOUT-PadN4)") (class "Default")
      (node (ref "U2") (pin "N4") (pinfunction "PA1/TIM2_CH2/TIM5_CH2/LPTIM3_OUT/TIM15_CH1N/USART2_RTS/USART2_DE/UART4_RX/QUADSPI_BK1_IO3/SAI2_MCLK_B/ETH_MII_RX_CLK/ETH_RMII_REF_CLK/LCD_R2/EVENTOUT_N4") (pintype "bidirectional+no_connect"))
    )
    (net (code "261") (name "unconnected-(U2A-PA2{slash}TIM2_CH3{slash}TIM5_CH3{slash}LPTIM4_OUT{slash}TIM15_CH1{slash}USART2_TX{slash}SAI2_SCK_B{slash}ETH_MDIO{slash}MDIOS_MDIO{slash}LCD_R1{slash}EVENTOUT-PadN3)") (class "Default")
      (node (ref "U2") (pin "N3") (pinfunction "PA2/TIM2_CH3/TIM5_CH3/LPTIM4_OUT/TIM15_CH1/USART2_TX/SAI2_SCK_B/ETH_MDIO/MDIOS_MDIO/LCD_R1/EVENTOUT_N3") (pintype "bidirectional+no_connect"))
    )
    (net (code "262") (name "unconnected-(U2A-PA3{slash}TIM2_CH4{slash}TIM5_CH4{slash}LPTIM5_OUT{slash}TIM15_CH2{slash}USART2_RX{slash}LCD_B2{slash}OTG_HS_ULPI_D0{slash}ETH_MII_COL{slash}LCD_B5{slash}EVENTOUT-PadU2)") (class "Default")
      (node (ref "U2") (pin "U2") (pinfunction "PA3/TIM2_CH4/TIM5_CH4/LPTIM5_OUT/TIM15_CH2/USART2_RX/LCD_B2/OTG_HS_ULPI_D0/ETH_MII_COL/LCD_B5/EVENTOUT_U2") (pintype "bidirectional+no_connect"))
    )
    (net (code "263") (name "unconnected-(U2A-PA5{slash}D2PWREN{slash}TIM2_CH1{slash}TIM2_ETR{slash}TIM8_CH1N{slash}SPI1_SCK{slash}I2S1_CK{slash}SPI6_SCK{slash}OTG_HS_ULPI_CK{slash}LCD_R4{slash}EVENTOUT-PadT3)") (class "Default")
      (node (ref "U2") (pin "T3") (pinfunction "PA5/D2PWREN/TIM2_CH1/TIM2_ETR/TIM8_CH1N/SPI1_SCK/I2S1_CK/SPI6_SCK/OTG_HS_ULPI_CK/LCD_R4/EVENTOUT_T3") (pintype "bidirectional+no_connect"))
    )
    (net (code "264") (name "unconnected-(U2A-PA7{slash}TIM1_CH1N{slash}TIM3_CH2{slash}TIM8_CH1N{slash}SPI1_MOSI{slash}I2S1_SDO{slash}SPI6_MOSI{slash}TIM14_CH1{slash}ETH_MII_RX_DV{slash}ETH_RMII_CRS_DV{slash}FMC_SDNWE{slash}EVENTOUT-PadR5)") (class "Default")
      (node (ref "U2") (pin "R5") (pinfunction "PA7/TIM1_CH1N/TIM3_CH2/TIM8_CH1N/SPI1_MOSI/I2S1_SDO/SPI6_MOSI/TIM14_CH1/ETH_MII_RX_DV/ETH_RMII_CRS_DV/FMC_SDNWE/EVENTOUT_R5") (pintype "bidirectional+no_connect"))
    )
    (net (code "265") (name "unconnected-(U2A-PA8{slash}MCO1{slash}TIM1_CH1{slash}HRTIM_CHB2{slash}TIM8_BKIN2{slash}I2C3_SCL{slash}USART1_CK{slash}OTG_FS_SOF{slash}UART7_RX{slash}TIM8_BKIN2_COMP12{slash}LCD_B3{slash}LCD_R6{slash}EVENTOUT-PadE15)") (class "Default")
      (node (ref "U2") (pin "E15") (pinfunction "PA8/MCO1/TIM1_CH1/HRTIM_CHB2/TIM8_BKIN2/I2C3_SCL/USART1_CK/OTG_FS_SOF/UART7_RX/TIM8_BKIN2_COMP12/LCD_B3/LCD_R6/EVENTOUT_E15") (pintype "bidirectional+no_connect"))
    )
    (net (code "266") (name "unconnected-(U2A-PA15{slash}JTDI{slash}TIM2_CH1{slash}TIM2_ETR{slash}HRTIM_FLT1{slash}CEC{slash}SPI1_NSS{slash}I2S1_WS{slash}SPI3_NSS{slash}I2S3_WS{slash}SPI6_NSS{slash}UART4_RTS{slash}UART4_DE{slash}UART7_TX{slash}EVENTOUT-PadA14)") (class "Default")
      (node (ref "U2") (pin "A14") (pinfunction "PA15/JTDI/TIM2_CH1/TIM2_ETR/HRTIM_FLT1/CEC/SPI1_NSS/I2S1_WS/SPI3_NSS/I2S3_WS/SPI6_NSS/UART4_RTS/UART4_DE/UART7_TX/EVENTOUT_A14") (pintype "bidirectional+no_connect"))
    )
    (net (code "267") (name "unconnected-(U2A-PB0{slash}TIM1_CH2N{slash}TIM3_CH3{slash}TIM8_CH2N{slash}DFSDM1_CKOUT{slash}UART4_CTS{slash}LCD_R3{slash}OTG_HS_ULPI_D1{slash}ETH_MII_RXD2{slash}LCD_G1{slash}EVENTOUT-PadU5)") (class "Default")
      (node (ref "U2") (pin "U5") (pinfunction "PB0/TIM1_CH2N/TIM3_CH3/TIM8_CH2N/DFSDM1_CKOUT/UART4_CTS/LCD_R3/OTG_HS_ULPI_D1/ETH_MII_RXD2/LCD_G1/EVENTOUT_U5") (pintype "bidirectional+no_connect"))
    )
    (net (code "268") (name "unconnected-(U2A-PB1{slash}TIM1_CH3N{slash}TIM3_CH4{slash}TIM8_CH3N{slash}DFSDM1_DATIN1{slash}LCD_R6{slash}OTG_HS_ULPI_D2{slash}ETH_MII_RXD3{slash}LCD_G0{slash}EVENTOUT-PadT5)") (class "Default")
      (node (ref "U2") (pin "T5") (pinfunction "PB1/TIM1_CH3N/TIM3_CH4/TIM8_CH3N/DFSDM1_DATIN1/LCD_R6/OTG_HS_ULPI_D2/ETH_MII_RXD3/LCD_G0/EVENTOUT_T5") (pintype "bidirectional+no_connect"))
    )
    (net (code "269") (name "unconnected-(U2A-PB2{slash}RTC_OUT{slash}SAI1_D1{slash}DFSDM1_CKIN1{slash}SAI1_SD_A{slash}SPI3_MOSI{slash}I2S3_SDO{slash}SAI4_SD_A{slash}QUADSPI_CLK{slash}SAI4_D1{slash}EVENTOUT-PadR6)") (class "Default")
      (node (ref "U2") (pin "R6") (pinfunction "PB2/RTC_OUT/SAI1_D1/DFSDM1_CKIN1/SAI1_SD_A/SPI3_MOSI/I2S3_SDO/SAI4_SD_A/QUADSPI_CLK/SAI4_D1/EVENTOUT_R6") (pintype "bidirectional+no_connect"))
    )
    (net (code "270") (name "unconnected-(U2A-PB3{slash}JTDO{slash}TRACESWO{slash}TIM2_CH2{slash}HRTIM_FLT4{slash}SPI1_SCK{slash}I2S1_CK{slash}SPI3_SCK{slash}I2S3_CK{slash}SPI6_SCK{slash}SDMMC2_D2{slash}CRS_SYNC{slash}UART7_RX{slash}EVENTOUT-PadC6)") (class "Default")
      (node (ref "U2") (pin "C6") (pinfunction "PB3/JTDO/TRACESWO/TIM2_CH2/HRTIM_FLT4/SPI1_SCK/I2S1_CK/SPI3_SCK/I2S3_CK/SPI6_SCK/SDMMC2_D2/CRS_SYNC/UART7_RX/EVENTOUT_C6") (pintype "bidirectional+no_connect"))
    )
    (net (code "271") (name "unconnected-(U2A-PB4{slash}NJTRST{slash}TIM16_BKIN{slash}TIM3_CH1{slash}HRTIM_EEV6{slash}SPI1_MISO{slash}I2S1_SDI{slash}SPI3_MISO{slash}I2S3_SDI{slash}SPI2_NSS{slash}I2S2_WS{slash}SPI6_MISO{slash}SDMMC2_D3{slash}UART7_TX{slash}EVENTOUT-PadB7)") (class "Default")
      (node (ref "U2") (pin "B7") (pinfunction "PB4/NJTRST/TIM16_BKIN/TIM3_CH1/HRTIM_EEV6/SPI1_MISO/I2S1_SDI/SPI3_MISO/I2S3_SDI/SPI2_NSS/I2S2_WS/SPI6_MISO/SDMMC2_D3/UART7_TX/EVENTOUT_B7") (pintype "bidirectional+no_connect"))
    )
    (net (code "272") (name "unconnected-(U2A-PB5{slash}TIM17_BKIN{slash}TIM3_CH2{slash}HRTIM_EEV7{slash}I2C1_SMBA{slash}SPI1_MOSI{slash}I2S1_SDO{slash}I2C4_SMBA{slash}SPI3_MOSI{slash}I2S3_SDO{slash}SPI6_MOSI{slash}FDCAN2_RX{slash}OTG_HS_ULPI_D7{slash}ETH_PPS_OUT{slash}FMC_SDCKE1{slash}DCMI_D10{slash}UART5_RX{slash}EVENTOUT-PadA5)") (class "Default")
      (node (ref "U2") (pin "A5") (pinfunction "PB5/TIM17_BKIN/TIM3_CH2/HRTIM_EEV7/I2C1_SMBA/SPI1_MOSI/I2S1_SDO/I2C4_SMBA/SPI3_MOSI/I2S3_SDO/SPI6_MOSI/FDCAN2_RX/OTG_HS_ULPI_D7/ETH_PPS_OUT/FMC_SDCKE1/DCMI_D10/UART5_RX/EVENTOUT_A5") (pintype "bidirectional+no_connect"))
    )
    (net (code "273") (name "unconnected-(U2A-PB6{slash}TIM16_CH1N{slash}TIM4_CH1{slash}HRTIM_EEV8{slash}I2C1_SCL{slash}CEC{slash}I2C4_SCL{slash}USART1_TX{slash}LPUART1_TX{slash}FDCAN2_TX{slash}QUADSPI_BK1_NCS{slash}DFSDM1_DATIN5{slash}FMC_SDNE1{slash}DCMI_D5{slash}UART5_TX{slash}EVENTOUT-PadB5)") (class "Default")
      (node (ref "U2") (pin "B5") (pinfunction "PB6/TIM16_CH1N/TIM4_CH1/HRTIM_EEV8/I2C1_SCL/CEC/I2C4_SCL/USART1_TX/LPUART1_TX/FDCAN2_TX/QUADSPI_BK1_NCS/DFSDM1_DATIN5/FMC_SDNE1/DCMI_D5/UART5_TX/EVENTOUT_B5") (pintype "bidirectional+no_connect"))
    )
    (net (code "274") (name "unconnected-(U2A-PB7{slash}TIM17_CH1N{slash}TIM4_CH2{slash}HRTIM_EEV9{slash}I2C1_SDA{slash}I2C4_SDA{slash}USART1_RX{slash}LPUART1_RX{slash}FDCAN2_TXFD_MODE{slash}DFSDM1_CKIN5{slash}FMC_NL{slash}DCMI_VSYNC{slash}EVENTOUT-PadC5)") (class "Default")
      (node (ref "U2") (pin "C5") (pinfunction "PB7/TIM17_CH1N/TIM4_CH2/HRTIM_EEV9/I2C1_SDA/I2C4_SDA/USART1_RX/LPUART1_RX/FDCAN2_TXFD_MODE/DFSDM1_CKIN5/FMC_NL/DCMI_VSYNC/EVENTOUT_C5") (pintype "bidirectional+no_connect"))
    )
    (net (code "275") (name "unconnected-(U2A-PB8{slash}TIM16_CH1{slash}TIM4_CH3{slash}DFSDM1_CKIN7{slash}I2C1_SCL{slash}I2C4_SCL{slash}SDMMC1_CKIN{slash}UART4_RX{slash}FDCAN1_RX{slash}SDMMC2_D4{slash}ETH_MII_TXD3{slash}SDMMC1_D4{slash}DCMI_D6{slash}LCD_B6{slash}EVENTOUT-PadD5)") (class "Default")
      (node (ref "U2") (pin "D5") (pinfunction "PB8/TIM16_CH1/TIM4_CH3/DFSDM1_CKIN7/I2C1_SCL/I2C4_SCL/SDMMC1_CKIN/UART4_RX/FDCAN1_RX/SDMMC2_D4/ETH_MII_TXD3/SDMMC1_D4/DCMI_D6/LCD_B6/EVENTOUT_D5") (pintype "bidirectional+no_connect"))
    )
    (net (code "276") (name "unconnected-(U2A-PB9{slash}TIM17_CH1{slash}TIM4_CH4{slash}DFSDM1_DATIN7{slash}I2C1_SDA{slash}SPI2_NSS{slash}I2S2_WS{slash}I2C4_SDA{slash}SDMMC1_CDIR{slash}UART4_TX{slash}FDCAN1_TX{slash}SDMMC2_D5{slash}I2C4_SMBA{slash}SDMMC1_D5{slash}DCMI_D7{slash}LCD_B7{slash}EVENTOUT-PadD4)") (class "Default")
      (node (ref "U2") (pin "D4") (pinfunction "PB9/TIM17_CH1/TIM4_CH4/DFSDM1_DATIN7/I2C1_SDA/SPI2_NSS/I2S2_WS/I2C4_SDA/SDMMC1_CDIR/UART4_TX/FDCAN1_TX/SDMMC2_D5/I2C4_SMBA/SDMMC1_D5/DCMI_D7/LCD_B7/EVENTOUT_D4") (pintype "bidirectional+no_connect"))
    )
    (net (code "277") (name "unconnected-(U2A-PB10{slash}TIM2_CH3{slash}HRTIM_SCOUT{slash}LPTIM2_IN1{slash}I2C2_SCL{slash}SPI2_SCK{slash}I2S2_CK{slash}DFSDM1_DATIN7{slash}USART3_TX{slash}QUADSPI_BK1_NCS{slash}OTG_HS_ULPI_D3{slash}ETH_MII_RX_ER{slash}LCD_G4{slash}EVENTOUT-PadP11)") (class "Default")
      (node (ref "U2") (pin "P11") (pinfunction "PB10/TIM2_CH3/HRTIM_SCOUT/LPTIM2_IN1/I2C2_SCL/SPI2_SCK/I2S2_CK/DFSDM1_DATIN7/USART3_TX/QUADSPI_BK1_NCS/OTG_HS_ULPI_D3/ETH_MII_RX_ER/LCD_G4/EVENTOUT_P11") (pintype "bidirectional+no_connect"))
    )
    (net (code "278") (name "unconnected-(U2A-PB11{slash}TIM2_CH4{slash}HRTIM_SCIN{slash}LPTIM2_ETR{slash}I2C2_SDA{slash}DFSDM1_CKIN7{slash}USART3_RX{slash}OTG_HS_ULPI_D4{slash}ETH_MII_TX_EN{slash}ETH_RMII_TX_EN{slash}LCD_G5{slash}EVENTOUT-PadP12)") (class "Default")
      (node (ref "U2") (pin "P12") (pinfunction "PB11/TIM2_CH4/HRTIM_SCIN/LPTIM2_ETR/I2C2_SDA/DFSDM1_CKIN7/USART3_RX/OTG_HS_ULPI_D4/ETH_MII_TX_EN/ETH_RMII_TX_EN/LCD_G5/EVENTOUT_P12") (pintype "bidirectional+no_connect"))
    )
    (net (code "279") (name "unconnected-(U2A-PB12{slash}TIM1_BKIN{slash}I2C2_SMBA{slash}SPI2_NSS{slash}I2S2_WS{slash}DFSDM1_DATIN1{slash}USART3_CK{slash}FDCAN2_RX{slash}OTG_HS_ULPI_D5{slash}ETH_MII_TXD0{slash}ETH_RMII_TXD0{slash}OTG_HS_ID{slash}TIM1_BKIN_COMP12{slash}UART5_RX{slash}EVENTOUT-PadT14)") (class "Default")
      (node (ref "U2") (pin "T14") (pinfunction "PB12/TIM1_BKIN/I2C2_SMBA/SPI2_NSS/I2S2_WS/DFSDM1_DATIN1/USART3_CK/FDCAN2_RX/OTG_HS_ULPI_D5/ETH_MII_TXD0/ETH_RMII_TXD0/OTG_HS_ID/TIM1_BKIN_COMP12/UART5_RX/EVENTOUT_T14") (pintype "bidirectional+no_connect"))
    )
    (net (code "280") (name "unconnected-(U2A-PB14{slash}TIM1_CH2N{slash}TIM12_CH1{slash}TIM8_CH2N{slash}USART1_TX{slash}SPI2_MISO{slash}I2S2_SDI{slash}DFSDM1_DATIN2{slash}USART3_RTS{slash}USART3_DE{slash}UART4_RTS{slash}UART4_DE{slash}SDMMC2_D0{slash}OTG_HS_DM{slash}EVENTOUT-PadU15)") (class "Default")
      (node (ref "U2") (pin "U15") (pinfunction "PB14/TIM1_CH2N/TIM12_CH1/TIM8_CH2N/USART1_TX/SPI2_MISO/I2S2_SDI/DFSDM1_DATIN2/USART3_RTS/USART3_DE/UART4_RTS/UART4_DE/SDMMC2_D0/OTG_HS_DM/EVENTOUT_U15") (pintype "bidirectional+no_connect"))
    )
    (net (code "281") (name "unconnected-(U2A-PB15{slash}RTC_REFIN{slash}TIM1_CH3N{slash}TIM12_CH2{slash}TIM8_CH3N{slash}USART1_RX{slash}SPI2_MOSI{slash}I2S2_SDO{slash}DFSDM1_CKIN2{slash}UART4_CTS{slash}SDMMC2_D1{slash}OTG_HS_DP{slash}EVENTOUT-PadT15)") (class "Default")
      (node (ref "U2") (pin "T15") (pinfunction "PB15/RTC_REFIN/TIM1_CH3N/TIM12_CH2/TIM8_CH3N/USART1_RX/SPI2_MOSI/I2S2_SDO/DFSDM1_CKIN2/UART4_CTS/SDMMC2_D1/OTG_HS_DP/EVENTOUT_T15") (pintype "bidirectional+no_connect"))
    )
    (net (code "282") (name "unconnected-(U2B-PC1{slash}TRACED0{slash}SAI1_D1{slash}DFSDM1_DATIN0{slash}DFSDM1_CKIN4{slash}SPI2_MOSI{slash}I2S2_SDO{slash}SAI1_SD_A{slash}SAI4_SD_A{slash}SDMMC2_CK{slash}SAI4_D1{slash}ETH_MDC{slash}MDIOS_MDC{slash}EVENTOUT-PadM2)") (class "Default")
      (node (ref "U2") (pin "M2") (pinfunction "PC1/TRACED0/SAI1_D1/DFSDM1_DATIN0/DFSDM1_CKIN4/SPI2_MOSI/I2S2_SDO/SAI1_SD_A/SAI4_SD_A/SDMMC2_CK/SAI4_D1/ETH_MDC/MDIOS_MDC/EVENTOUT_M2") (pintype "bidirectional+no_connect"))
    )
    (net (code "283") (name "unconnected-(U2B-PC2_C{slash}CDSLEEP{slash}DFSDM1_CKIN1{slash}SPI2_MISO{slash}I2S2_SDI{slash}DFSDM1_CKOUT{slash}OTG_HS_ULPI_DIR{slash}ETH_MII_TXD2{slash}FMC_SDNE0{slash}EVENTOUT-PadR1)") (class "Default")
      (node (ref "U2") (pin "R1") (pinfunction "PC2_C/CDSLEEP/DFSDM1_CKIN1/SPI2_MISO/I2S2_SDI/DFSDM1_CKOUT/OTG_HS_ULPI_DIR/ETH_MII_TXD2/FMC_SDNE0/EVENTOUT_R1") (pintype "bidirectional+no_connect"))
    )
    (net (code "284") (name "unconnected-(U2B-PC2{slash}CDSLEEP{slash}DFSDM1_CKIN1{slash}SPI2_MISO{slash}I2S2_SDI{slash}DFSDM1_CKOUT{slash}OTG_HS_ULPI_DIR{slash}ETH_MII_TXD2{slash}FMC_SDNE0{slash}EVENTOUT-PadM3)") (class "Default")
      (node (ref "U2") (pin "M3") (pinfunction "PC2/CDSLEEP/DFSDM1_CKIN1/SPI2_MISO/I2S2_SDI/DFSDM1_CKOUT/OTG_HS_ULPI_DIR/ETH_MII_TXD2/FMC_SDNE0/EVENTOUT_M3") (pintype "bidirectional+no_connect"))
    )
    (net (code "285") (name "unconnected-(U2B-PC3_C{slash}CSLEEP{slash}DFSDM1_DATIN1{slash}SPI2_MOSI{slash}I2S2_SDO{slash}OTG_HS_ULPI_NXT{slash}ETH_MII_TX_CLK{slash}FMC_SDCKE0{slash}EVENTOUT-PadR2)") (class "Default")
      (node (ref "U2") (pin "R2") (pinfunction "PC3_C/CSLEEP/DFSDM1_DATIN1/SPI2_MOSI/I2S2_SDO/OTG_HS_ULPI_NXT/ETH_MII_TX_CLK/FMC_SDCKE0/EVENTOUT_R2") (pintype "bidirectional+no_connect"))
    )
    (net (code "286") (name "unconnected-(U2B-PC3{slash}CSLEEP{slash}DFSDM1_DATIN1{slash}SPI2_MOSI{slash}I2S2_SDO{slash}OTG_HS_ULPI_NXT{slash}ETH_MII_TX_CLK{slash}FMC_SDCKE0{slash}EVENTOUT-PadM4)") (class "Default")
      (node (ref "U2") (pin "M4") (pinfunction "PC3/CSLEEP/DFSDM1_DATIN1/SPI2_MOSI/I2S2_SDO/OTG_HS_ULPI_NXT/ETH_MII_TX_CLK/FMC_SDCKE0/EVENTOUT_M4") (pintype "bidirectional+no_connect"))
    )
    (net (code "287") (name "unconnected-(U2B-PC4{slash}DFSDM1_CKIN2{slash}I2S1_MCK{slash}SPDIFRX1_IN3{slash}ETH_MII_RXD0{slash}ETH_RMII_RXD0{slash}FMC_SDNE0{slash}EVENTOUT-PadT4)") (class "Default")
      (node (ref "U2") (pin "T4") (pinfunction "PC4/DFSDM1_CKIN2/I2S1_MCK/SPDIFRX1_IN3/ETH_MII_RXD0/ETH_RMII_RXD0/FMC_SDNE0/EVENTOUT_T4") (pintype "bidirectional+no_connect"))
    )
    (net (code "288") (name "unconnected-(U2B-PC5{slash}SAI1_D3{slash}DFSDM1_DATIN2{slash}SPDIFRX1_IN4{slash}SAI4_D3{slash}ETH_MII_RXD1{slash}ETH_RMII_RXD1{slash}FMC_SDCKE0{slash}COMP1_OUT{slash}EVENTOUT-PadU4)") (class "Default")
      (node (ref "U2") (pin "U4") (pinfunction "PC5/SAI1_D3/DFSDM1_DATIN2/SPDIFRX1_IN4/SAI4_D3/ETH_MII_RXD1/ETH_RMII_RXD1/FMC_SDCKE0/COMP1_OUT/EVENTOUT_U4") (pintype "bidirectional+no_connect"))
    )
    (net (code "289") (name "unconnected-(U2B-PD4{slash}HRTIM_FLT3{slash}SAI3_FS_A{slash}USART2_RTS{slash}USART2_DE{slash}FDCAN1_RXFD_MODE{slash}FMC_NOE{slash}EVENTOUT-PadA12)") (class "Default")
      (node (ref "U2") (pin "A12") (pinfunction "PD4/HRTIM_FLT3/SAI3_FS_A/USART2_RTS/USART2_DE/FDCAN1_RXFD_MODE/FMC_NOE/EVENTOUT_A12") (pintype "bidirectional+no_connect"))
    )
    (net (code "290") (name "unconnected-(U2B-PD5{slash}HRTIM_EEV3{slash}USART2_TX{slash}FDCAN1_TXFD_MODE{slash}FMC_NWE{slash}EVENTOUT-PadA11)") (class "Default")
      (node (ref "U2") (pin "A11") (pinfunction "PD5/HRTIM_EEV3/USART2_TX/FDCAN1_TXFD_MODE/FMC_NWE/EVENTOUT_A11") (pintype "bidirectional+no_connect"))
    )
    (net (code "291") (name "unconnected-(U2B-PD6{slash}SAI1_D1{slash}DFSDM1_CKIN4{slash}DFSDM1_DATIN1{slash}SPI3_MOSI{slash}I2S3_SDO{slash}SAI1_SD_A{slash}USART2_RX{slash}SAI4_SD_A{slash}FDCAN2_RXFD_MODE{slash}SAI4_D1{slash}SDMMC2_CK{slash}FMC_NWAIT{slash}DCMI_D10{slash}LCD_B2{slash}EVENTOUT-PadB11)") (class "Default")
      (node (ref "U2") (pin "B11") (pinfunction "PD6/SAI1_D1/DFSDM1_CKIN4/DFSDM1_DATIN1/SPI3_MOSI/I2S3_SDO/SAI1_SD_A/USART2_RX/SAI4_SD_A/FDCAN2_RXFD_MODE/SAI4_D1/SDMMC2_CK/FMC_NWAIT/DCMI_D10/LCD_B2/EVENTOUT_B11") (pintype "bidirectional+no_connect"))
    )
    (net (code "292") (name "unconnected-(U2B-PD7{slash}DFSDM1_DATIN4{slash}SPI1_MOSI{slash}I2S1_SDO{slash}DFSDM1_CKIN1{slash}USART2_CK{slash}SPDIFRX1_IN1{slash}SDMMC2_CMD{slash}FMC_NE1{slash}EVENTOUT-PadC11)") (class "Default")
      (node (ref "U2") (pin "C11") (pinfunction "PD7/DFSDM1_DATIN4/SPI1_MOSI/I2S1_SDO/DFSDM1_CKIN1/USART2_CK/SPDIFRX1_IN1/SDMMC2_CMD/FMC_NE1/EVENTOUT_C11") (pintype "bidirectional+no_connect"))
    )
    (net (code "293") (name "unconnected-(U2B-PD11{slash}LPTIM2_IN2{slash}I2C4_SMBA{slash}USART3_CTS{slash}USART3_NSS{slash}QUADSPI_BK1_IO0{slash}SAI2_SD_A{slash}FMC_A16{slash}EVENTOUT-PadR15)") (class "Default")
      (node (ref "U2") (pin "R15") (pinfunction "PD11/LPTIM2_IN2/I2C4_SMBA/USART3_CTS/USART3_NSS/QUADSPI_BK1_IO0/SAI2_SD_A/FMC_A16/EVENTOUT_R15") (pintype "bidirectional+no_connect"))
    )
    (net (code "294") (name "unconnected-(U2B-PD12{slash}LPTIM1_IN1{slash}TIM4_CH1{slash}LPTIM2_IN1{slash}I2C4_SCL{slash}USART3_RTS{slash}USART3_DE{slash}QUADSPI_BK1_IO1{slash}SAI2_FS_A{slash}FMC_A17{slash}EVENTOUT-PadR16)") (class "Default")
      (node (ref "U2") (pin "R16") (pinfunction "PD12/LPTIM1_IN1/TIM4_CH1/LPTIM2_IN1/I2C4_SCL/USART3_RTS/USART3_DE/QUADSPI_BK1_IO1/SAI2_FS_A/FMC_A17/EVENTOUT_R16") (pintype "bidirectional+no_connect"))
    )
    (net (code "295") (name "unconnected-(U2B-PD13{slash}LPTIM1_OUT{slash}TIM4_CH2{slash}I2C4_SDA{slash}QUADSPI_BK1_IO3{slash}SAI2_SCK_A{slash}FMC_A18{slash}EVENTOUT-PadR17)") (class "Default")
      (node (ref "U2") (pin "R17") (pinfunction "PD13/LPTIM1_OUT/TIM4_CH2/I2C4_SDA/QUADSPI_BK1_IO3/SAI2_SCK_A/FMC_A18/EVENTOUT_R17") (pintype "bidirectional+no_connect"))
    )
    (net (code "296") (name "unconnected-(U2C-PE2{slash}TRACECLK{slash}SAI1_CK1{slash}SPI4_SCK{slash}SAI1_MCLK_A{slash}SAI4_MCLK_A{slash}QUADSPI_BK1_IO2{slash}SAI4_CK1{slash}ETH_MII_TXD3{slash}FMC_A23{slash}EVENTOUT-PadC3)") (class "Default")
      (node (ref "U2") (pin "C3") (pinfunction "PE2/TRACECLK/SAI1_CK1/SPI4_SCK/SAI1_MCLK_A/SAI4_MCLK_A/QUADSPI_BK1_IO2/SAI4_CK1/ETH_MII_TXD3/FMC_A23/EVENTOUT_C3") (pintype "bidirectional+no_connect"))
    )
    (net (code "297") (name "unconnected-(U2C-PE3{slash}TRACED0{slash}TIM15_BKIN{slash}SAI1_SD_B{slash}SAI4_SD_B{slash}FMC_A19{slash}EVENTOUT-PadD3)") (class "Default")
      (node (ref "U2") (pin "D3") (pinfunction "PE3/TRACED0/TIM15_BKIN/SAI1_SD_B/SAI4_SD_B/FMC_A19/EVENTOUT_D3") (pintype "bidirectional+no_connect"))
    )
    (net (code "298") (name "unconnected-(U2D-PG12{slash}LPTIM1_IN1{slash}HRTIM_EEV5{slash}SPI6_MISO{slash}USART6_RTS{slash}USART6_DE{slash}SPDIFRX1_IN2{slash}LCD_B4{slash}ETH_MII_TXD1{slash}ETH_RMII_TXD1{slash}FMC_NE4{slash}LCD_B1{slash}EVENTOUT-PadC9)") (class "Default")
      (node (ref "U2") (pin "C9") (pinfunction "PG12/LPTIM1_IN1/HRTIM_EEV5/SPI6_MISO/USART6_RTS/USART6_DE/SPDIFRX1_IN2/LCD_B4/ETH_MII_TXD1/ETH_RMII_TXD1/FMC_NE4/LCD_B1/EVENTOUT_C9") (pintype "bidirectional+no_connect"))
    )
    (net (code "299") (name "unconnected-(U2D-PG13{slash}TRACED0{slash}LPTIM1_OUT{slash}HRTIM_EEV10{slash}SPI6_SCK{slash}USART6_CTS{slash}USART6_NSS{slash}ETH_MII_TXD0{slash}ETH_RMII_TXD0{slash}FMC_A24{slash}LCD_R0{slash}EVENTOUT-PadD9)") (class "Default")
      (node (ref "U2") (pin "D9") (pinfunction "PG13/TRACED0/LPTIM1_OUT/HRTIM_EEV10/SPI6_SCK/USART6_CTS/USART6_NSS/ETH_MII_TXD0/ETH_RMII_TXD0/FMC_A24/LCD_R0/EVENTOUT_D9") (pintype "bidirectional+no_connect"))
    )
    (net (code "300") (name "unconnected-(U2D-PG14{slash}TRACED1{slash}LPTIM1_ETR{slash}SPI6_MOSI{slash}USART6_TX{slash}QUADSPI_BK2_IO3{slash}ETH_MII_TXD1{slash}ETH_RMII_TXD1{slash}FMC_A25{slash}LCD_B0{slash}EVENTOUT-PadD8)") (class "Default")
      (node (ref "U2") (pin "D8") (pinfunction "PG14/TRACED1/LPTIM1_ETR/SPI6_MOSI/USART6_TX/QUADSPI_BK2_IO3/ETH_MII_TXD1/ETH_RMII_TXD1/FMC_A25/LCD_B0/EVENTOUT_D8") (pintype "bidirectional+no_connect"))
    )
    (net (code "301") (name "unconnected-(U2D-PH7{slash}I2C3_SCL{slash}SPI5_MISO{slash}ETH_MII_RXD3{slash}FMC_SDCKE1{slash}DCMI_D9{slash}EVENTOUT-PadU13)") (class "Default")
      (node (ref "U2") (pin "U13") (pinfunction "PH7/I2C3_SCL/SPI5_MISO/ETH_MII_RXD3/FMC_SDCKE1/DCMI_D9/EVENTOUT_U13") (pintype "bidirectional+no_connect"))
    )
    (net (code "302") (name "unconnected-(U2F-NC-PadE1)") (class "Default")
      (node (ref "U2") (pin "E1") (pinfunction "NC_E1") (pintype "passive+no_connect"))
    )
    (net (code "303") (name "unconnected-(U2F-NC-PadK16)") (class "Default")
      (node (ref "U2") (pin "K16") (pinfunction "NC_K16") (pintype "passive+no_connect"))
    )
    (net (code "304") (name "unconnected-(U2F-NC-PadK17)") (class "Default")
      (node (ref "U2") (pin "K17") (pinfunction "NC_K17") (pintype "passive+no_connect"))
    )
    (net (code "305") (name "unconnected-(U2F-NC-PadL16)") (class "Default")
      (node (ref "U2") (pin "L16") (pinfunction "NC_L16") (pintype "passive+no_connect"))
    )
    (net (code "306") (name "unconnected-(U2F-NC-PadL17)") (class "Default")
      (node (ref "U2") (pin "L17") (pinfunction "NC_L17") (pintype "passive+no_connect"))
    )
    (net (code "307") (name "unconnected-(U2F-NC-PadM16)") (class "Default")
      (node (ref "U2") (pin "M16") (pinfunction "NC_M16") (pintype "passive+no_connect"))
    )
    (net (code "308") (name "unconnected-(U2F-NC-PadM17)") (class "Default")
      (node (ref "U2") (pin "M17") (pinfunction "NC_M17") (pintype "passive+no_connect"))
    )
    (net (code "309") (name "unconnected-(U2F-NC-PadN17)") (class "Default")
      (node (ref "U2") (pin "N17") (pinfunction "NC_N17") (pintype "passive+no_connect"))
    )
    (net (code "310") (name "unconnected-(U2F-NC1-PadF1)") (class "Default")
      (node (ref "U2") (pin "F1") (pinfunction "NC1_F1") (pintype "passive+no_connect"))
    )
    (net (code "311") (name "unconnected-(U2F-NC2-PadG2)") (class "Default")
      (node (ref "U2") (pin "G2") (pinfunction "NC2_G2") (pintype "passive+no_connect"))
    )
    (net (code "312") (name "unconnected-(U3-NU-PadK2)") (class "Default")
      (node (ref "U3") (pin "K2") (pinfunction "NU_K2") (pintype "bidirectional+no_connect"))
    )
    (net (code "313") (name "unconnected-(U4-CC1-PadA5)") (class "Default")
      (node (ref "U4") (pin "A5") (pinfunction "CC1_A5") (pintype "passive+no_connect"))
    )
    (net (code "314") (name "unconnected-(U4-CC2-PadB5)") (class "Default")
      (node (ref "U4") (pin "B5") (pinfunction "CC2_B5") (pintype "passive+no_connect"))
    )
    (net (code "315") (name "unconnected-(U4-SBU1-PadA8)") (class "Default")
      (node (ref "U4") (pin "A8") (pinfunction "SBU1_A8") (pintype "passive+no_connect"))
    )
    (net (code "316") (name "unconnected-(U4-SBU2-PadB8)") (class "Default")
      (node (ref "U4") (pin "B8") (pinfunction "SBU2_B8") (pintype "passive+no_connect"))
    )
    (net (code "317") (name "unconnected-(U5-CC1-PadA5)") (class "Default")
      (node (ref "U5") (pin "A5") (pinfunction "CC1_A5") (pintype "passive+no_connect"))
    )
    (net (code "318") (name "unconnected-(U5-CC2-PadB5)") (class "Default")
      (node (ref "U5") (pin "B5") (pinfunction "CC2_B5") (pintype "passive+no_connect"))
    )
    (net (code "319") (name "unconnected-(U5-SBU1-PadA8)") (class "Default")
      (node (ref "U5") (pin "A8") (pinfunction "SBU1_A8") (pintype "passive+no_connect"))
    )
    (net (code "320") (name "unconnected-(U5-SBU2-PadB8)") (class "Default")
      (node (ref "U5") (pin "B8") (pinfunction "SBU2_B8") (pintype "passive+no_connect"))
    )
    (net (code "321") (name "unconnected-(U10-Pad1)") (class "Default")
      (node (ref "U10") (pin "1") (pinfunction "1_1") (pintype "passive+no_connect"))
    )
    (net (code "322") (name "unconnected-(U10-Pad2)") (class "Default")
      (node (ref "U10") (pin "2") (pinfunction "2_2") (pintype "passive+no_connect"))
    )
    (net (code "323") (name "unconnected-(U10-Pad3)") (class "Default")
      (node (ref "U10") (pin "3") (pinfunction "3_3") (pintype "passive+no_connect"))
    )
    (net (code "324") (name "unconnected-(U10-Pad4)") (class "Default")
      (node (ref "U10") (pin "4") (pinfunction "4_4") (pintype "passive+no_connect"))
    )
    (net (code "325") (name "unconnected-(U10-Pad6)") (class "Default")
      (node (ref "U10") (pin "6") (pinfunction "6_6") (pintype "passive+no_connect"))
    )
    (net (code "326") (name "unconnected-(U11-EN1-Pad9)") (class "Default")
      (node (ref "U11") (pin "9") (pinfunction "EN1_9") (pintype "passive+no_connect"))
    )
    (net (code "327") (name "unconnected-(U11-FB1-Pad14)") (class "Default")
      (node (ref "U11") (pin "14") (pinfunction "FB1_14") (pintype "passive+no_connect"))
    )
    (net (code "328") (name "unconnected-(U11-NC-Pad1)") (class "Default")
      (node (ref "U11") (pin "1") (pinfunction "NC_1") (pintype "passive+no_connect"))
    )
    (net (code "329") (name "unconnected-(U11-NC-Pad4)") (class "Default")
      (node (ref "U11") (pin "4") (pinfunction "NC_4") (pintype "passive+no_connect"))
    )
    (net (code "330") (name "unconnected-(U11-NC-Pad5)") (class "Default")
      (node (ref "U11") (pin "5") (pinfunction "NC_5") (pintype "passive+no_connect"))
    )
    (net (code "331") (name "unconnected-(U11-NC-Pad12)") (class "Default")
      (node (ref "U11") (pin "12") (pinfunction "NC_12") (pintype "passive+no_connect"))
    )
    (net (code "332") (name "unconnected-(U11-NC-Pad13)") (class "Default")
      (node (ref "U11") (pin "13") (pinfunction "NC_13") (pintype "passive+no_connect"))
    )
    (net (code "333") (name "unconnected-(U11-NC-Pad15)") (class "Default")
      (node (ref "U11") (pin "15") (pinfunction "NC_15") (pintype "passive+no_connect"))
    )
    (net (code "334") (name "unconnected-(U11-NC-Pad16)") (class "Default")
      (node (ref "U11") (pin "16") (pinfunction "NC_16") (pintype "passive+no_connect"))
    )
    (net (code "335") (name "unconnected-(U11-NC-Pad17)") (class "Default")
      (node (ref "U11") (pin "17") (pinfunction "NC_17") (pintype "passive+no_connect"))
    )
    (net (code "336") (name "unconnected-(U11-SW1-Pad11)") (class "Default")
      (node (ref "U11") (pin "11") (pinfunction "SW1_11") (pintype "passive+no_connect"))
    )
    (net (code "337") (name "unconnected-(U11-VIN1-Pad10)") (class "Default")
      (node (ref "U11") (pin "10") (pinfunction "VIN1_10") (pintype "passive+no_connect"))
    )
  )
)
